# PX4FMUv2_4_5.net
KiCad netlist of a schematic drawn in EAGLE
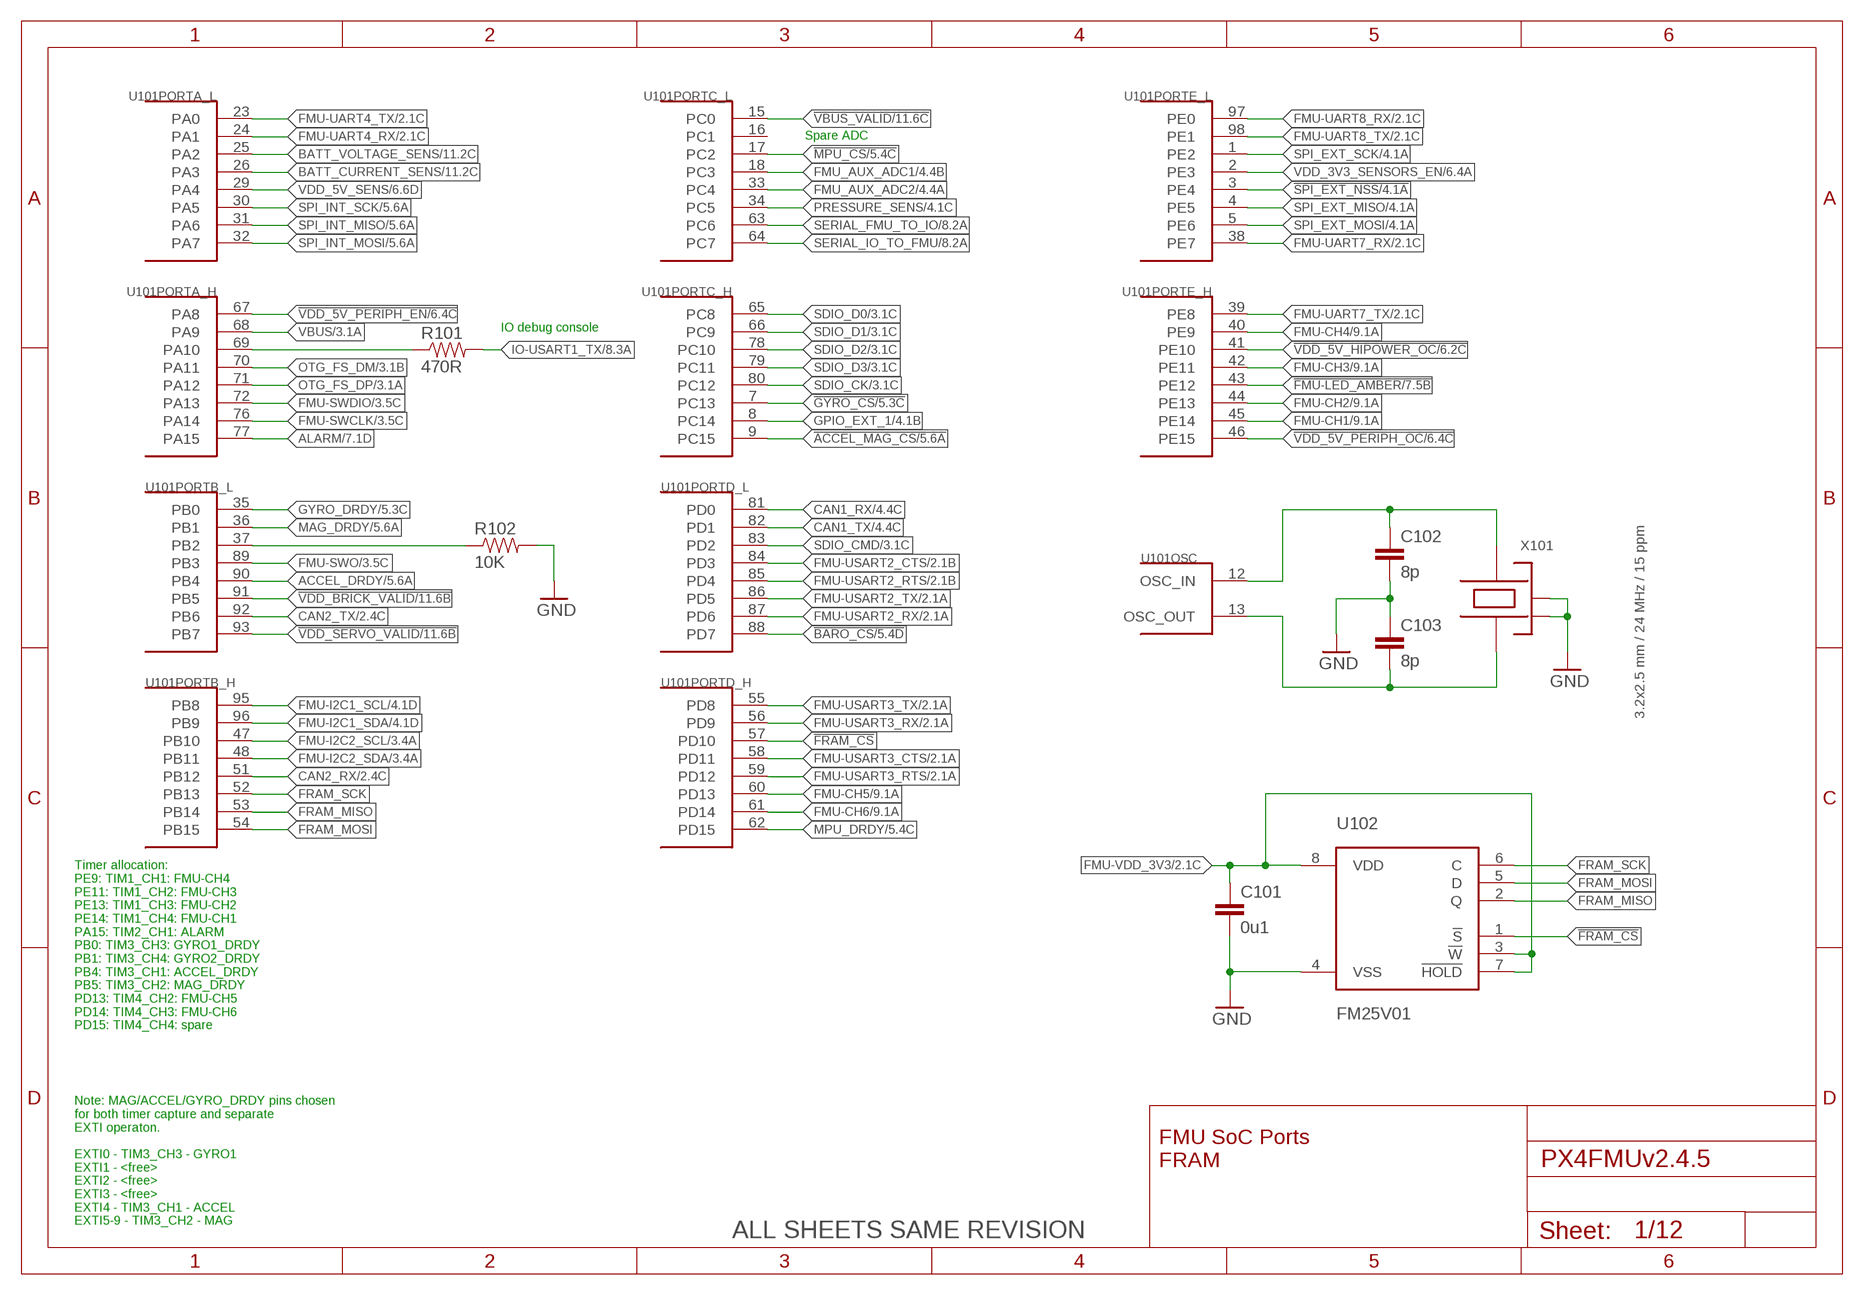
[diagram p0: schematic, sheet 1]
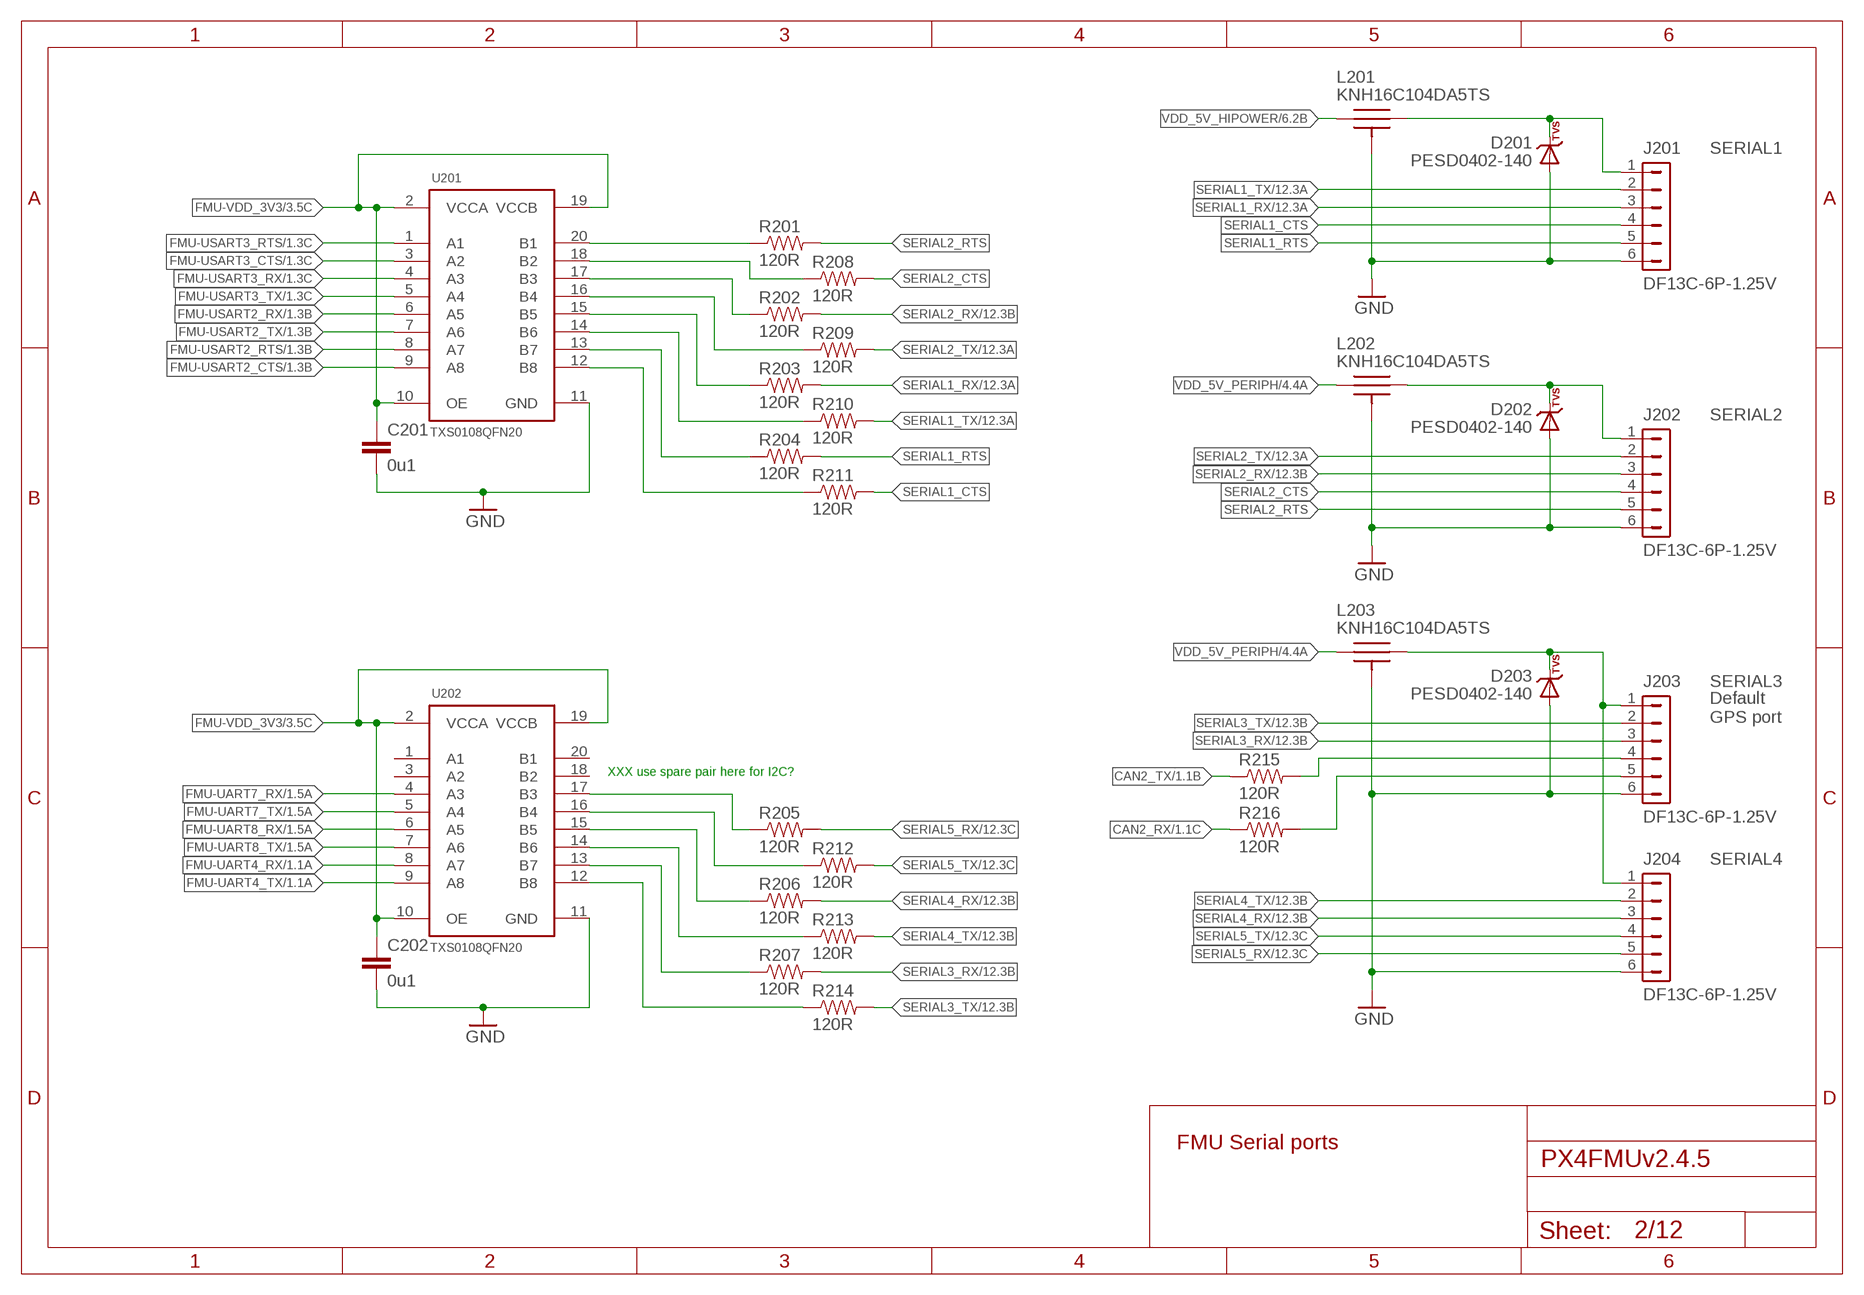
[diagram p1: schematic, sheet 2]
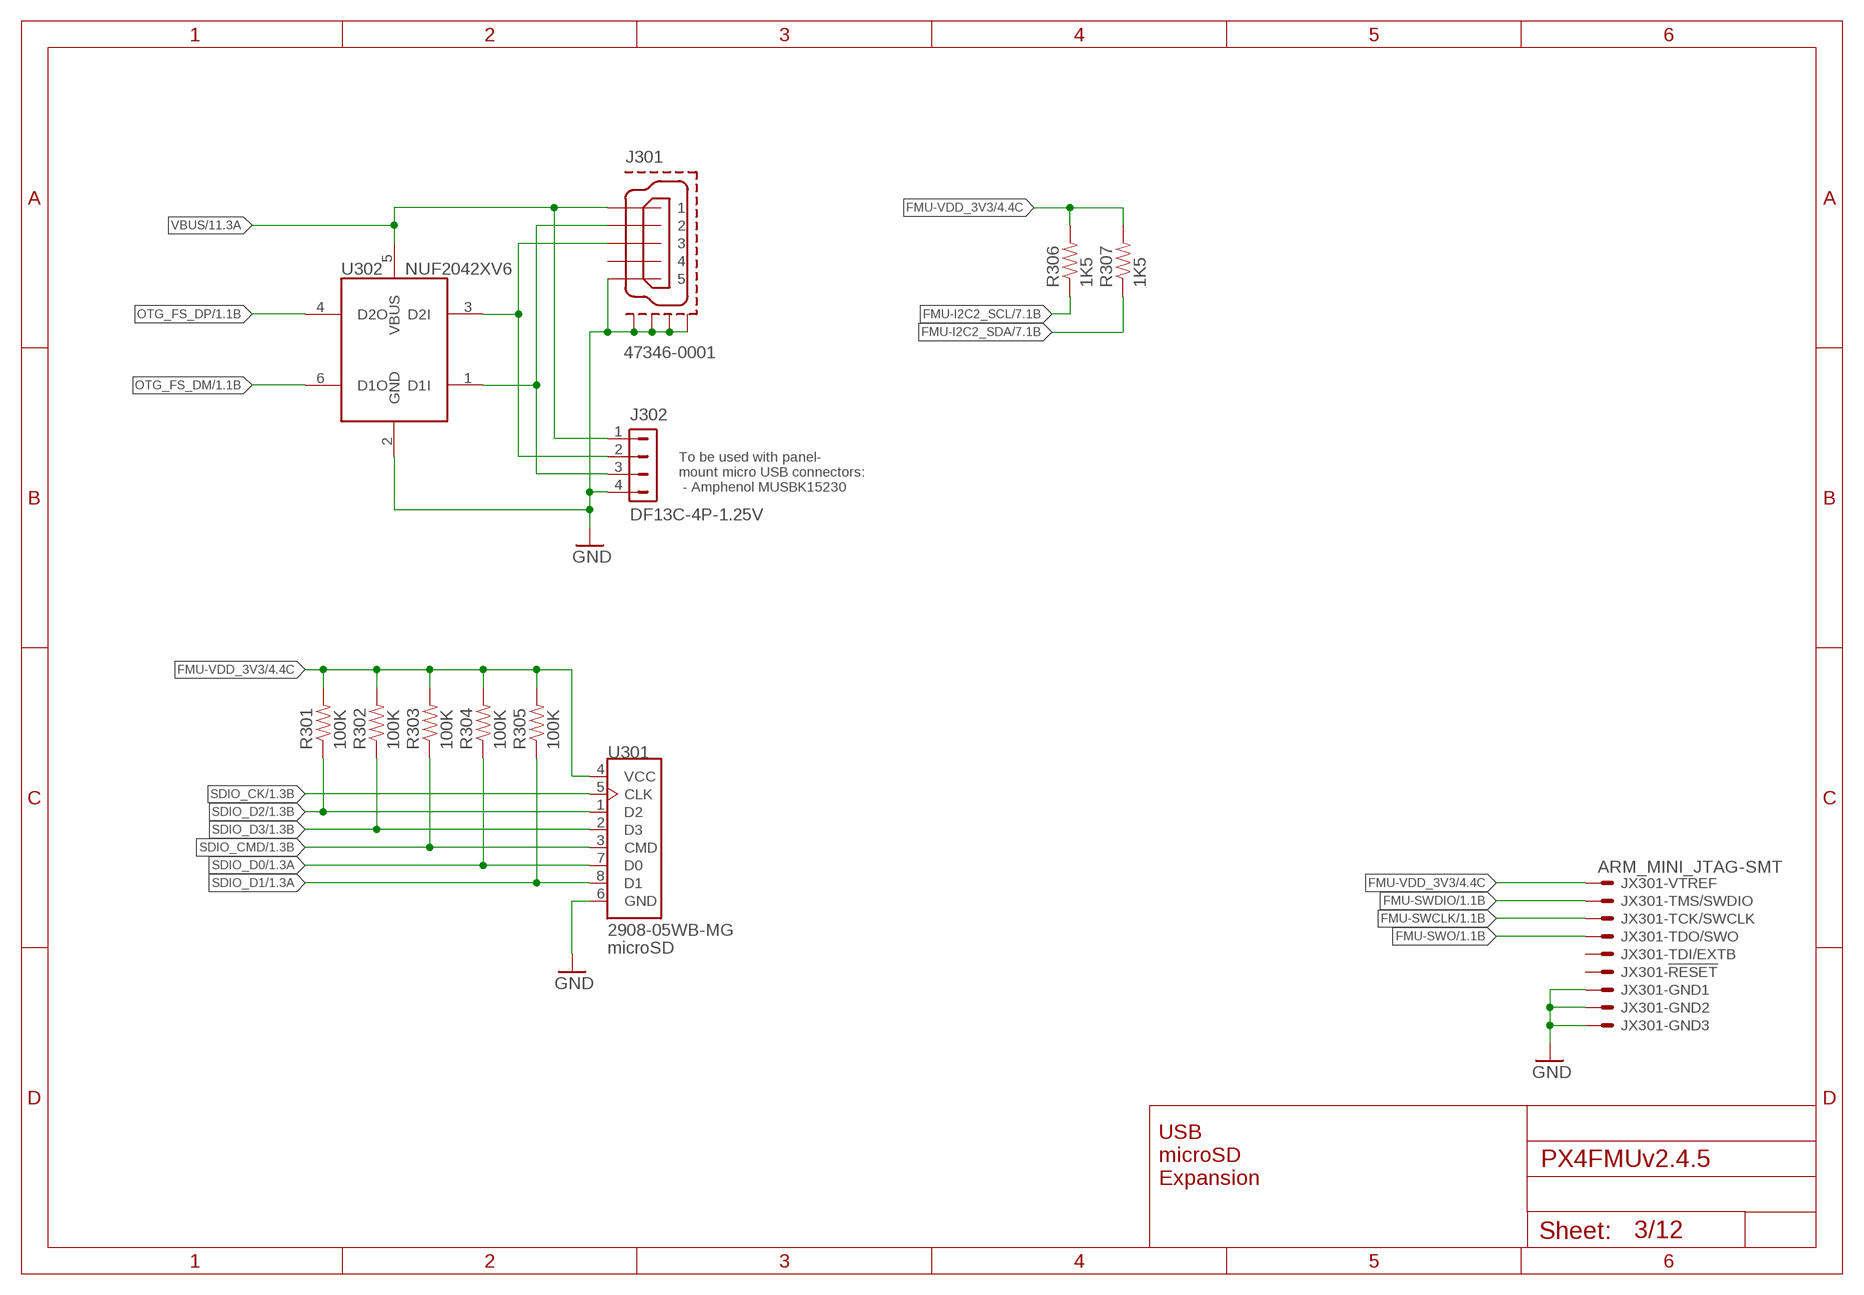
[diagram p2: schematic, sheet 3]
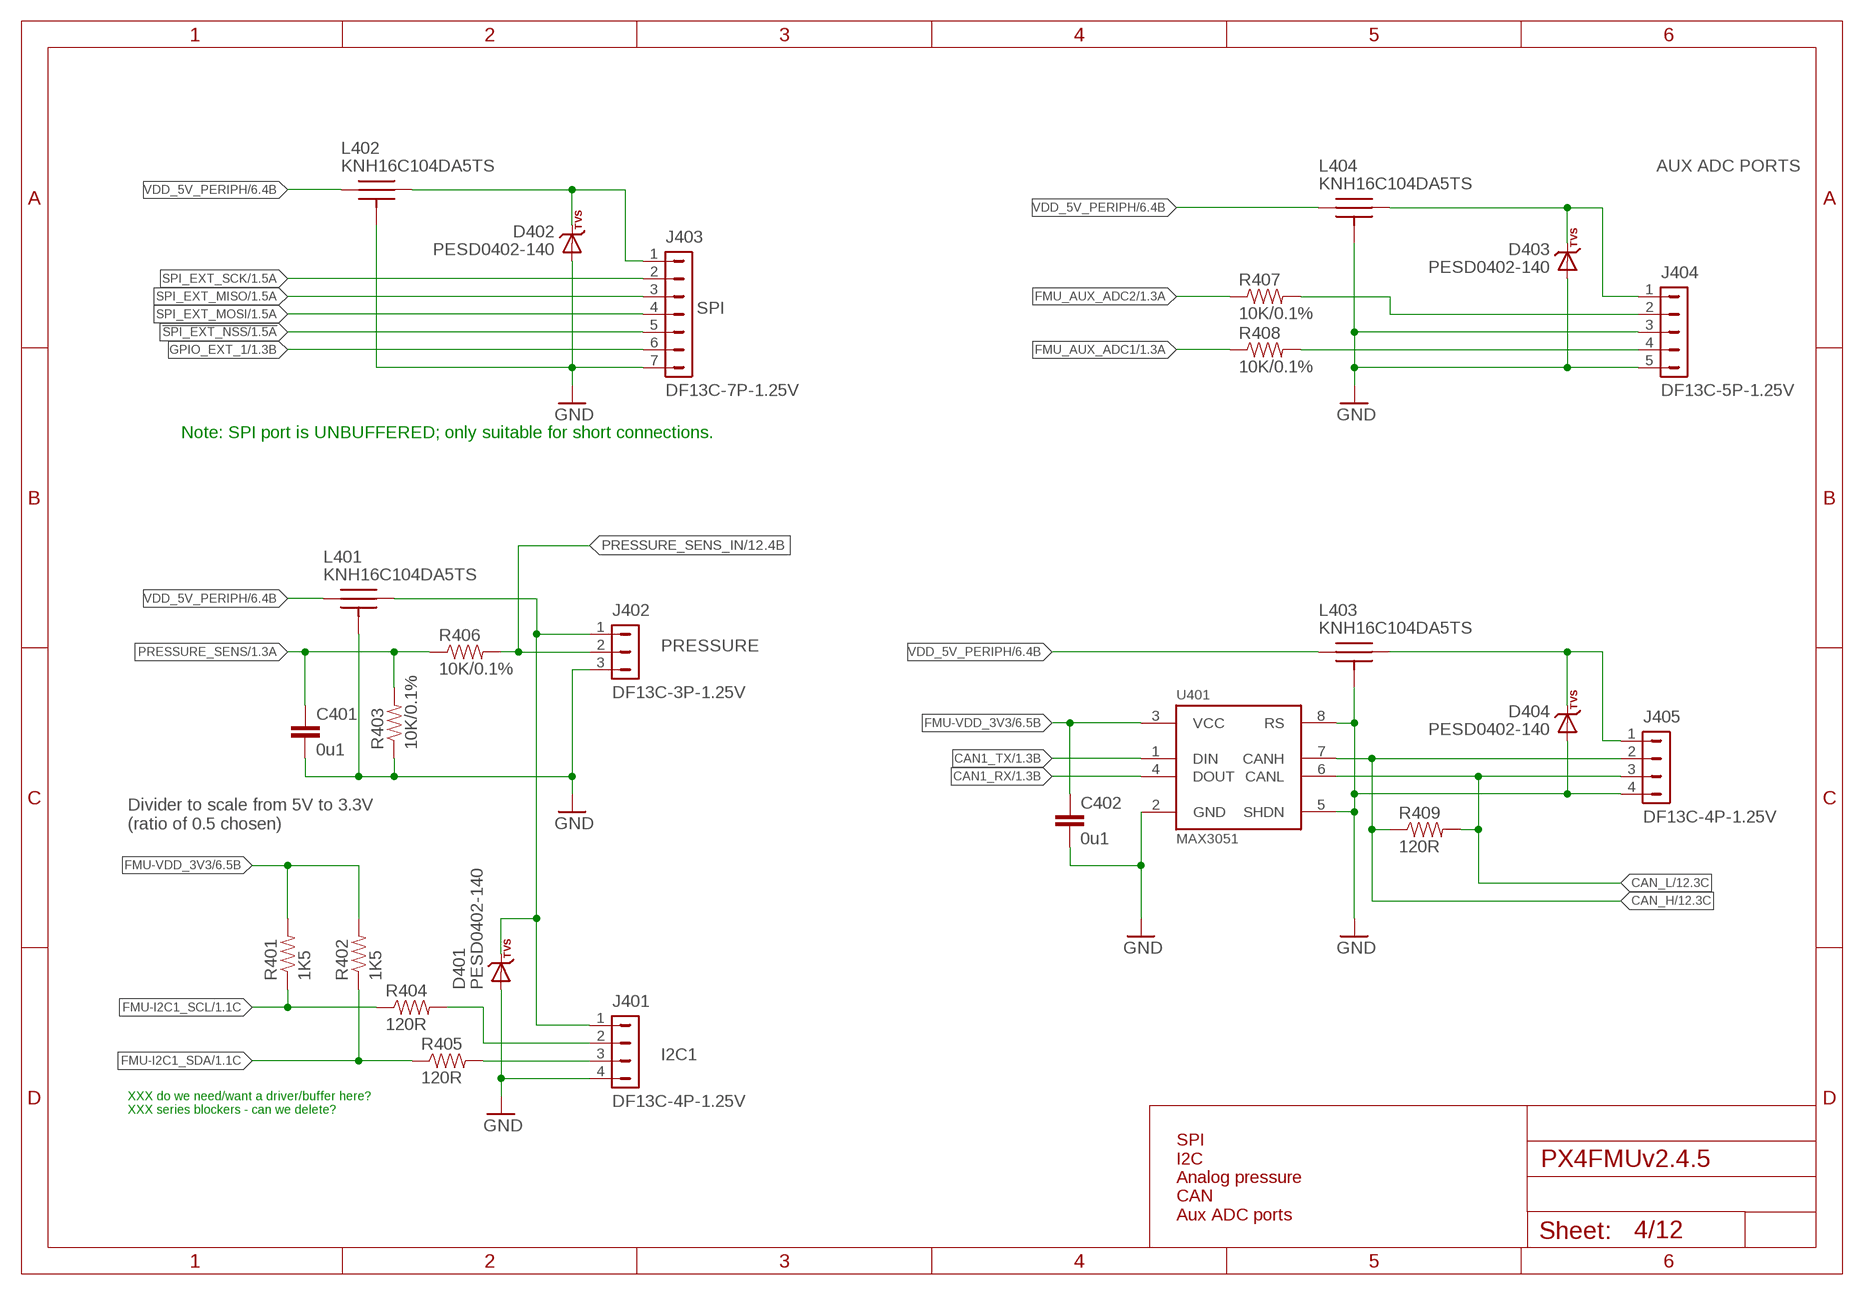
[diagram p3: schematic, sheet 4]
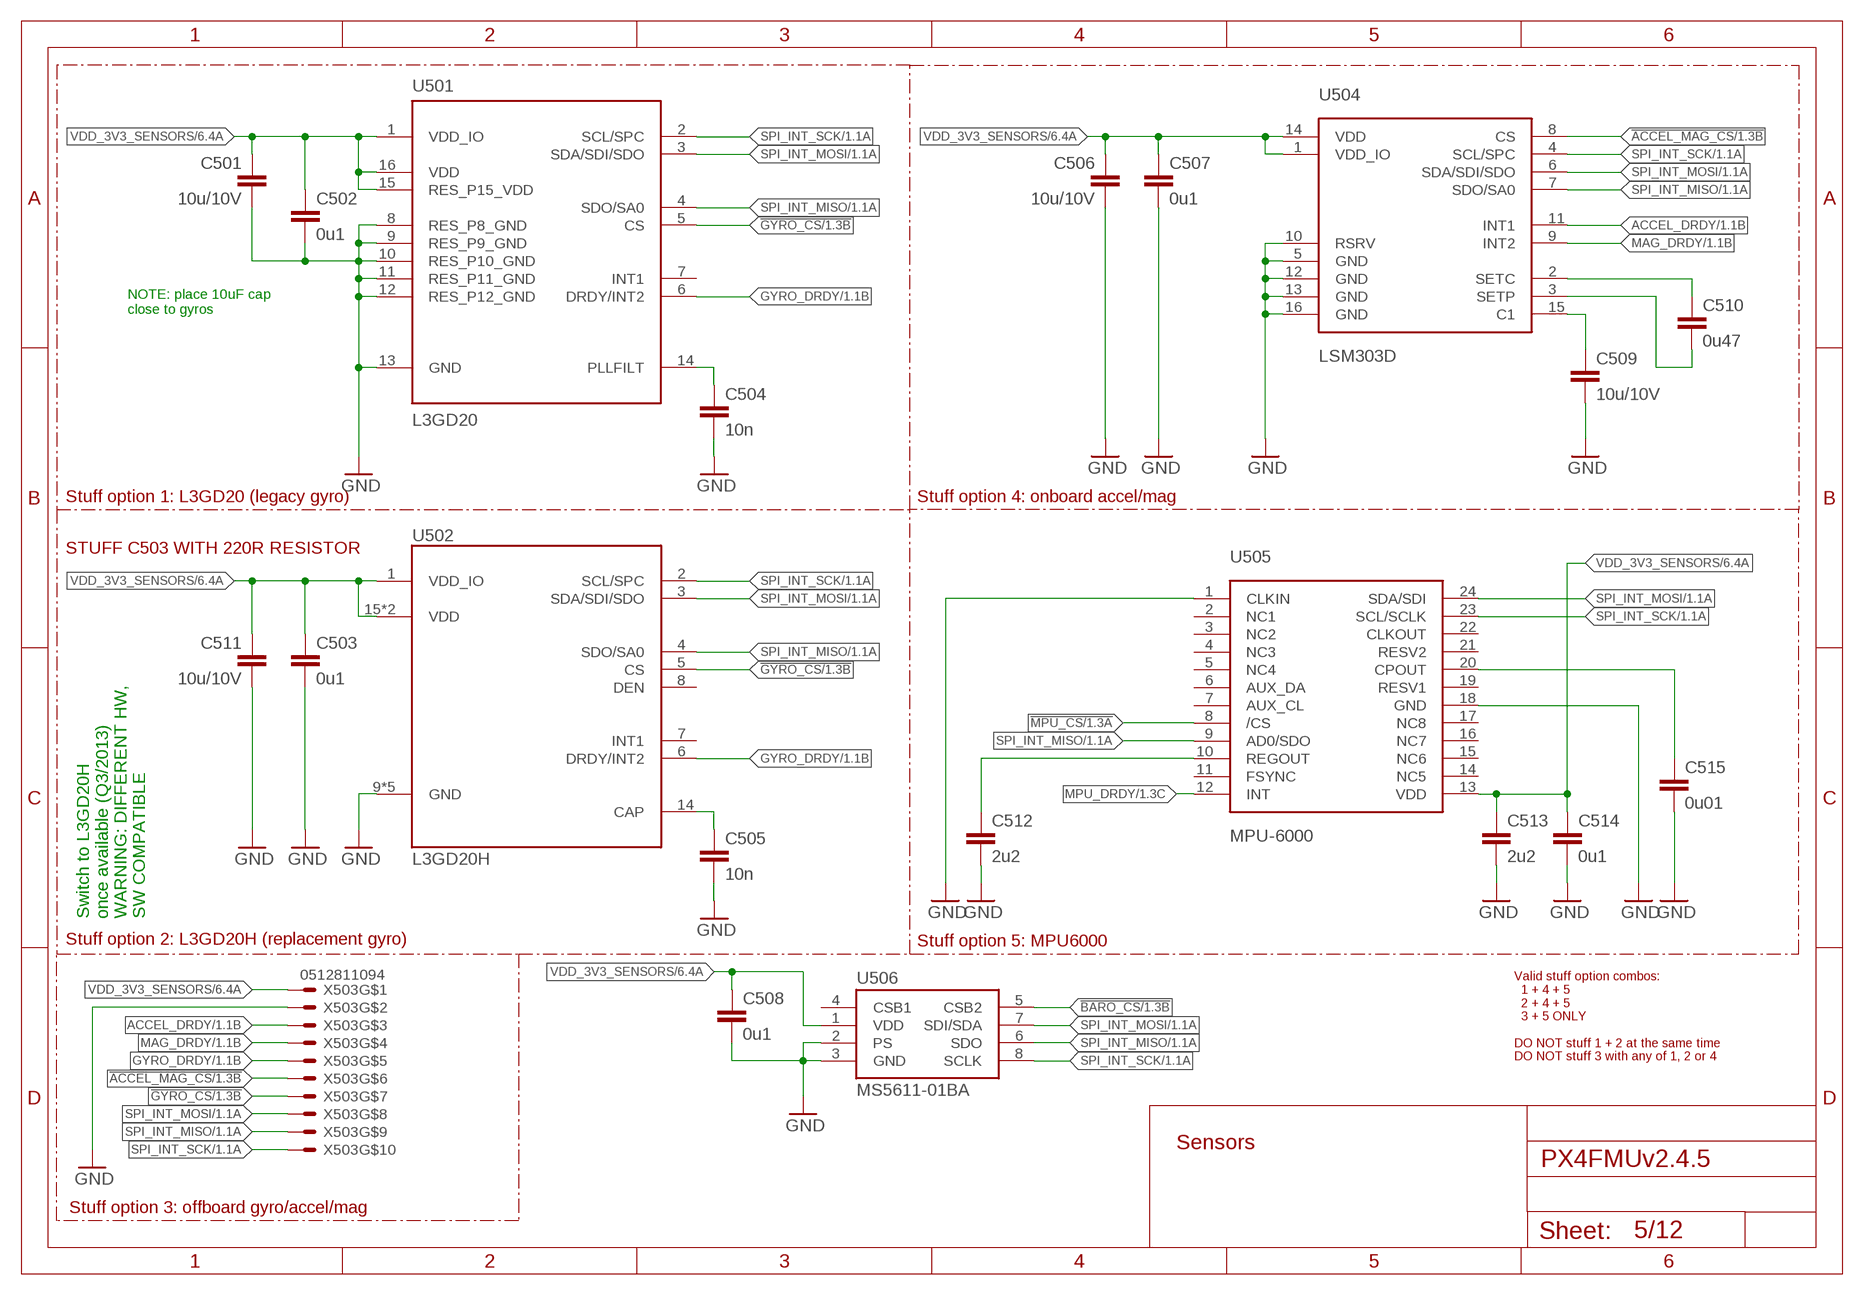
[diagram p4: schematic, sheet 5]
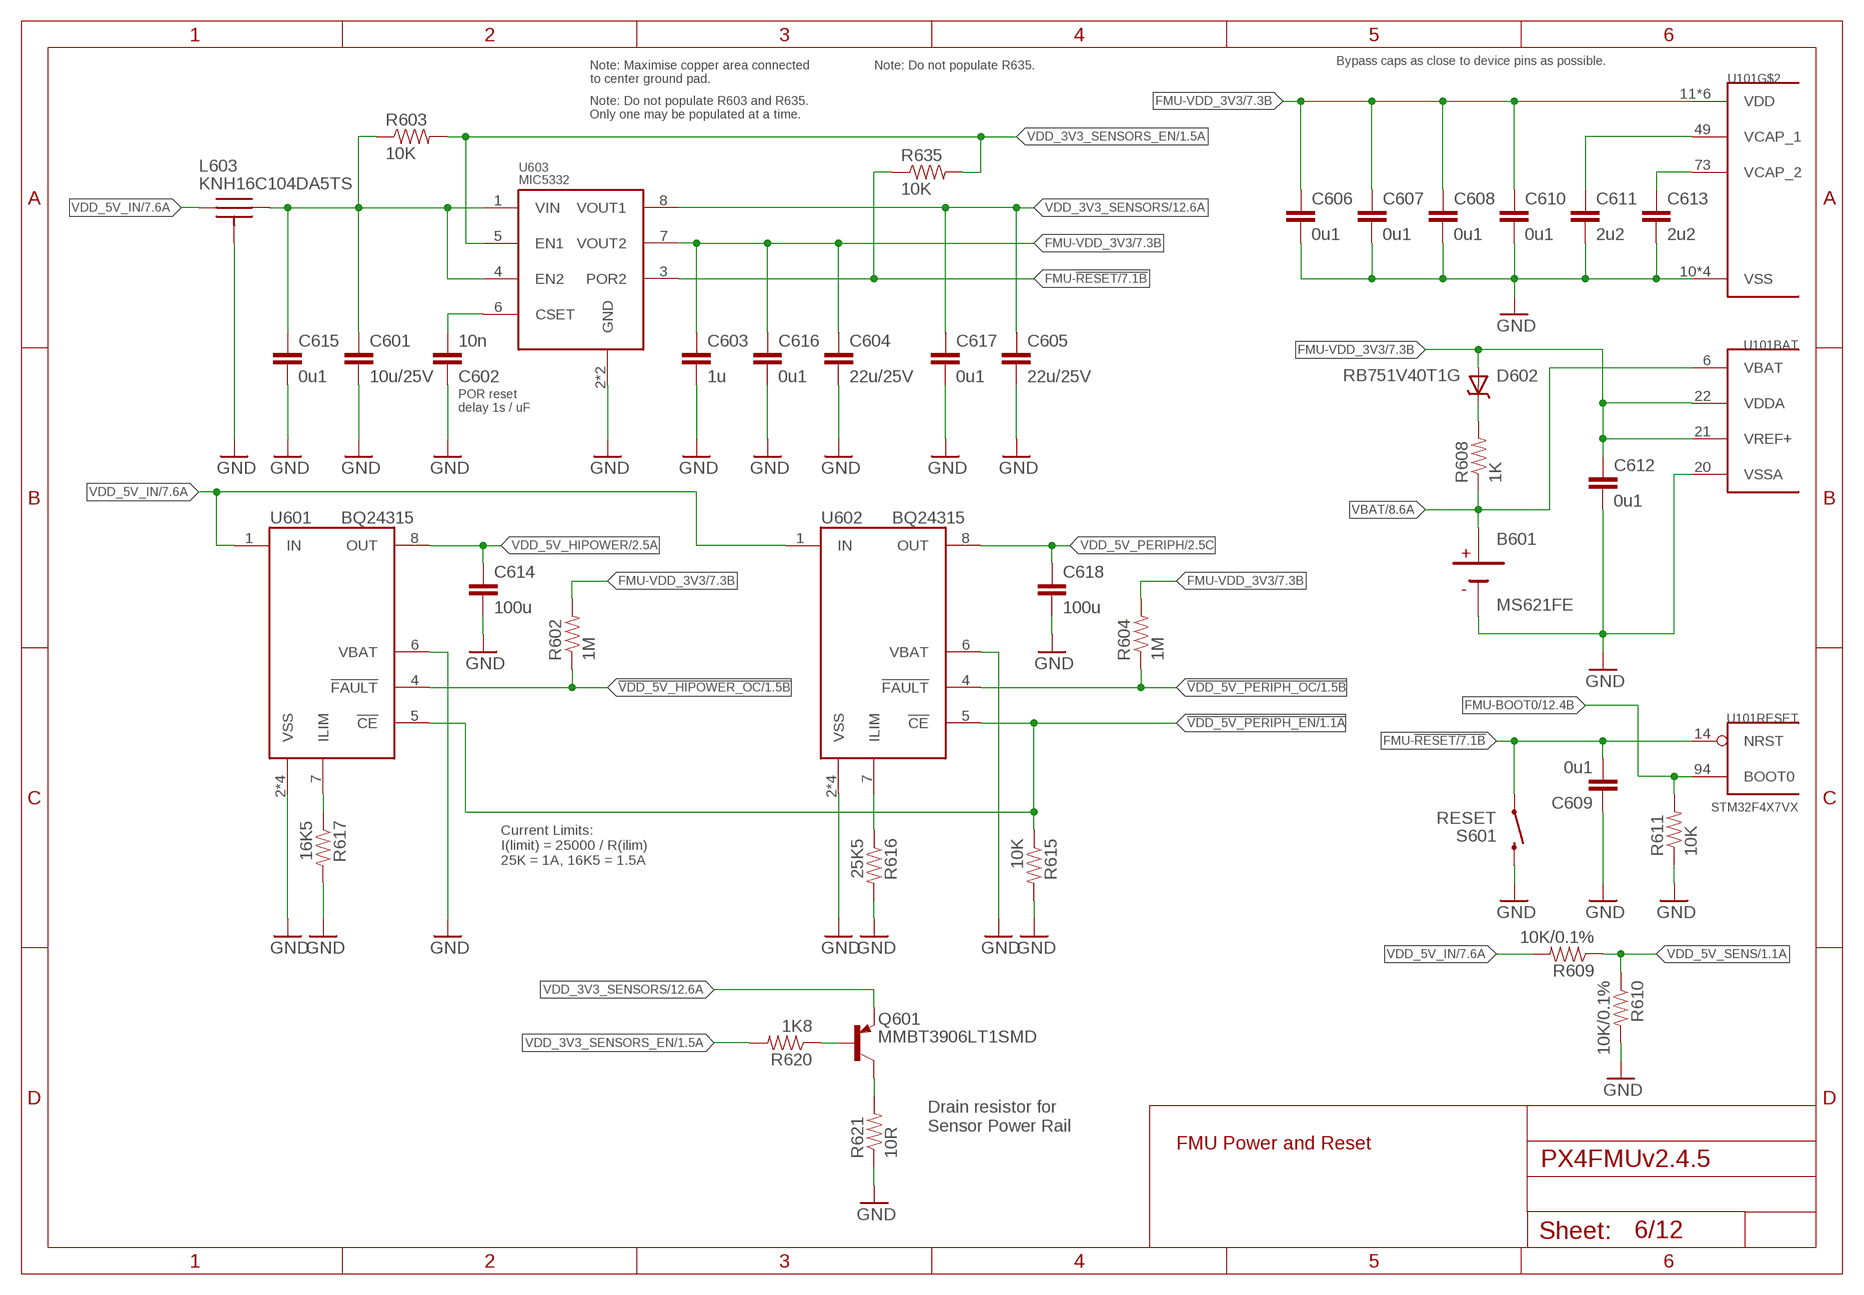
[diagram p5: schematic, sheet 6]
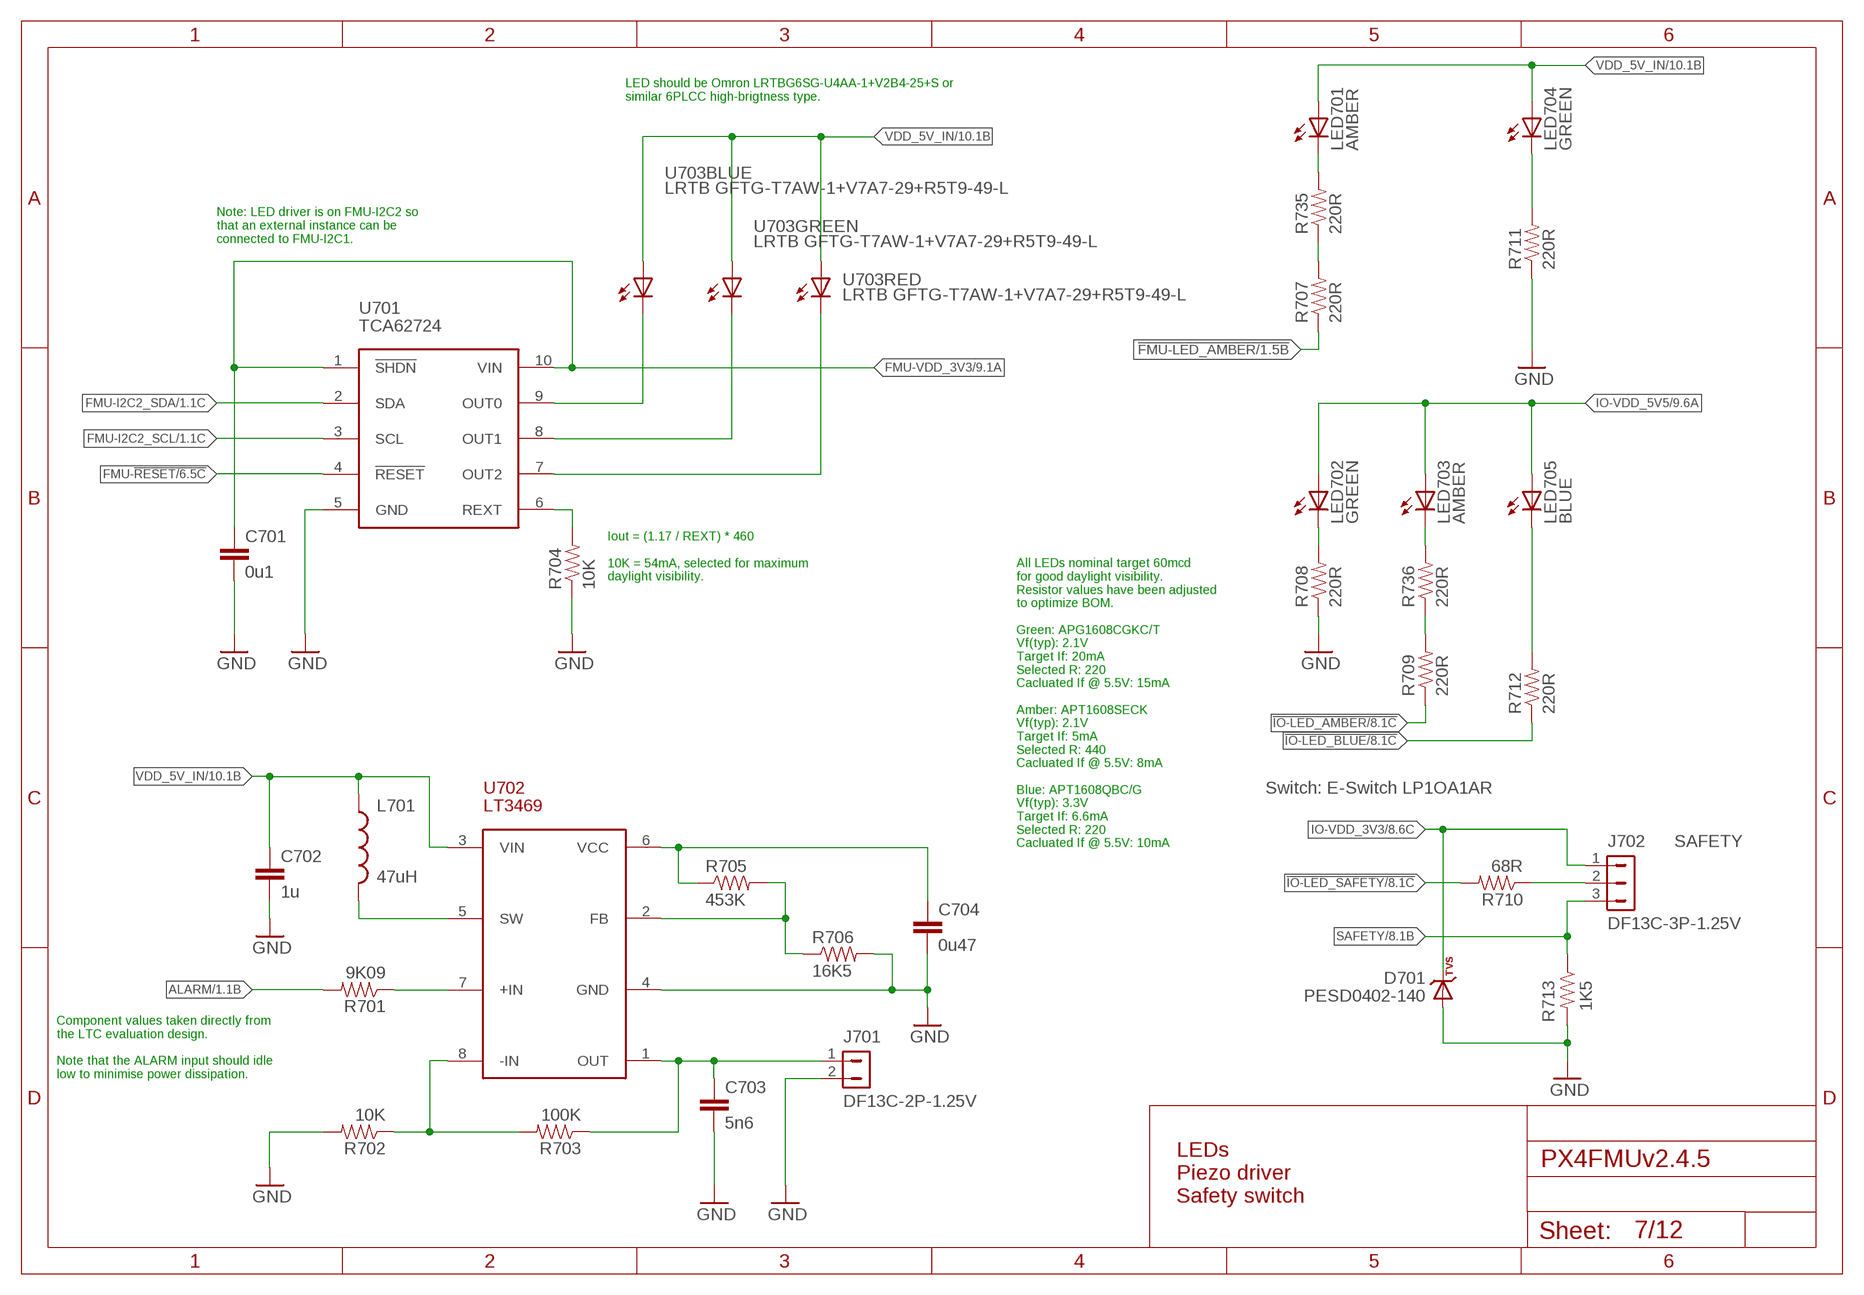
[diagram p6: schematic, sheet 7]
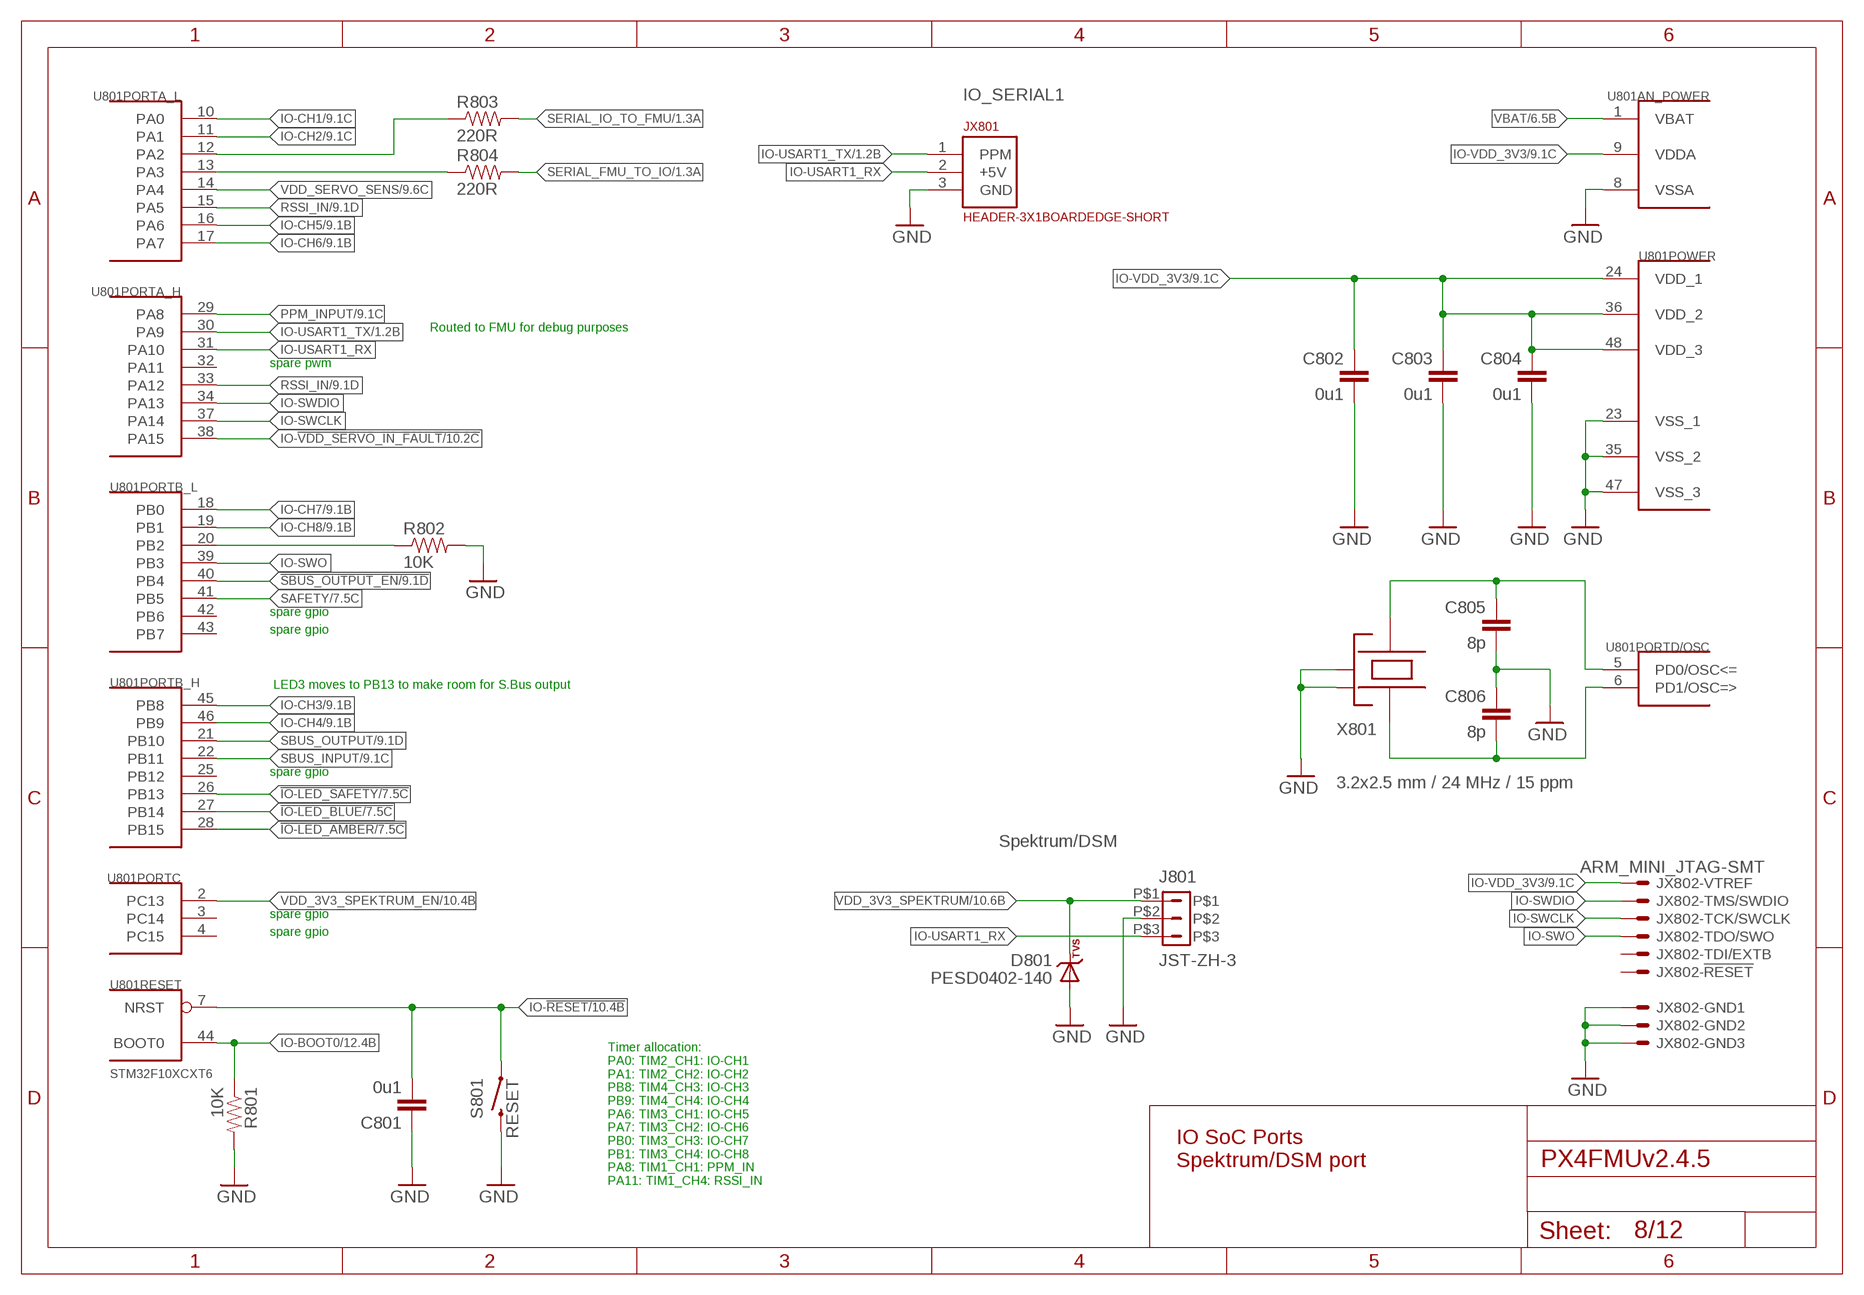
[diagram p7: schematic, sheet 8]
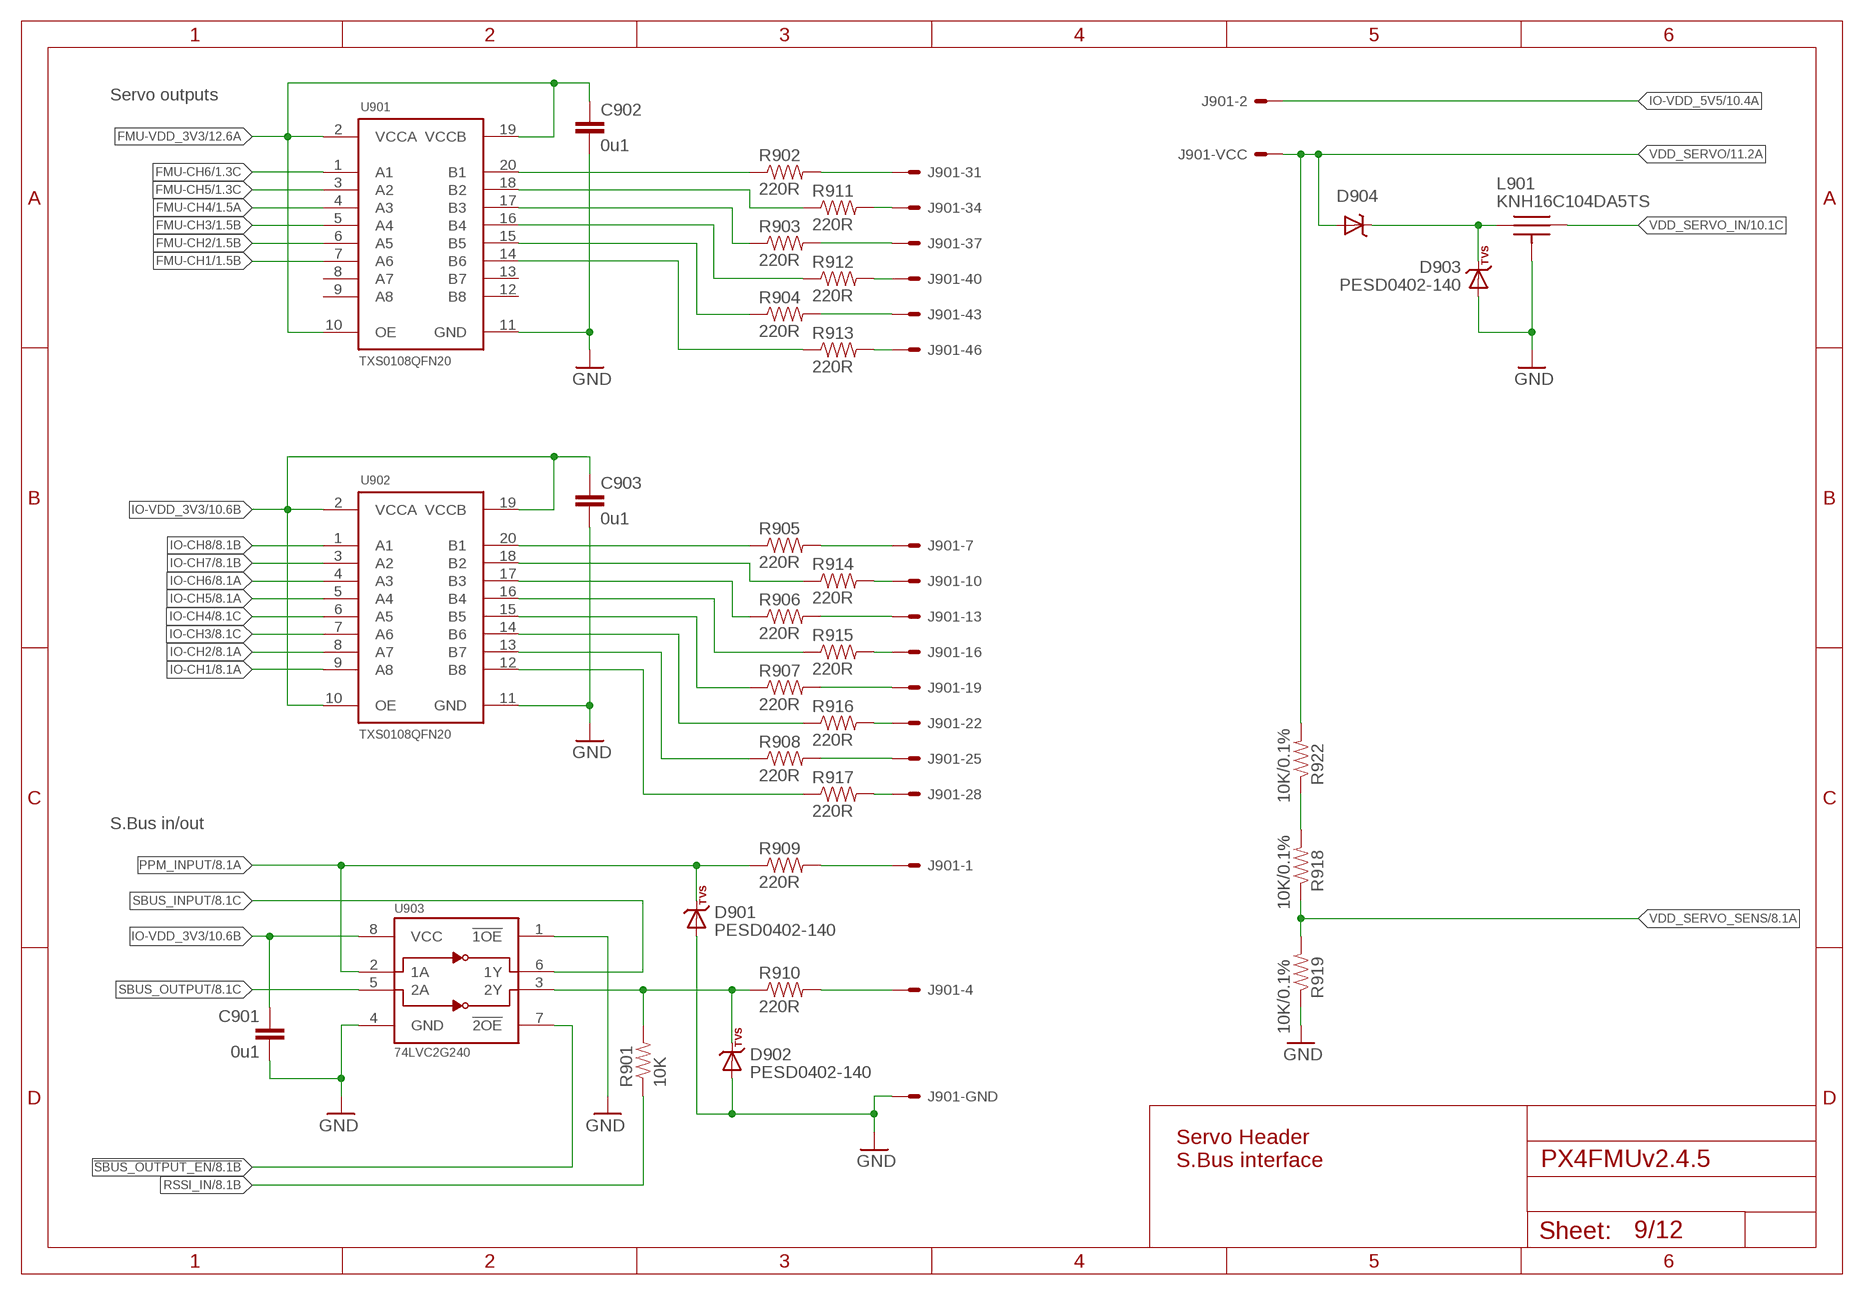
[diagram p8: schematic, sheet 9]
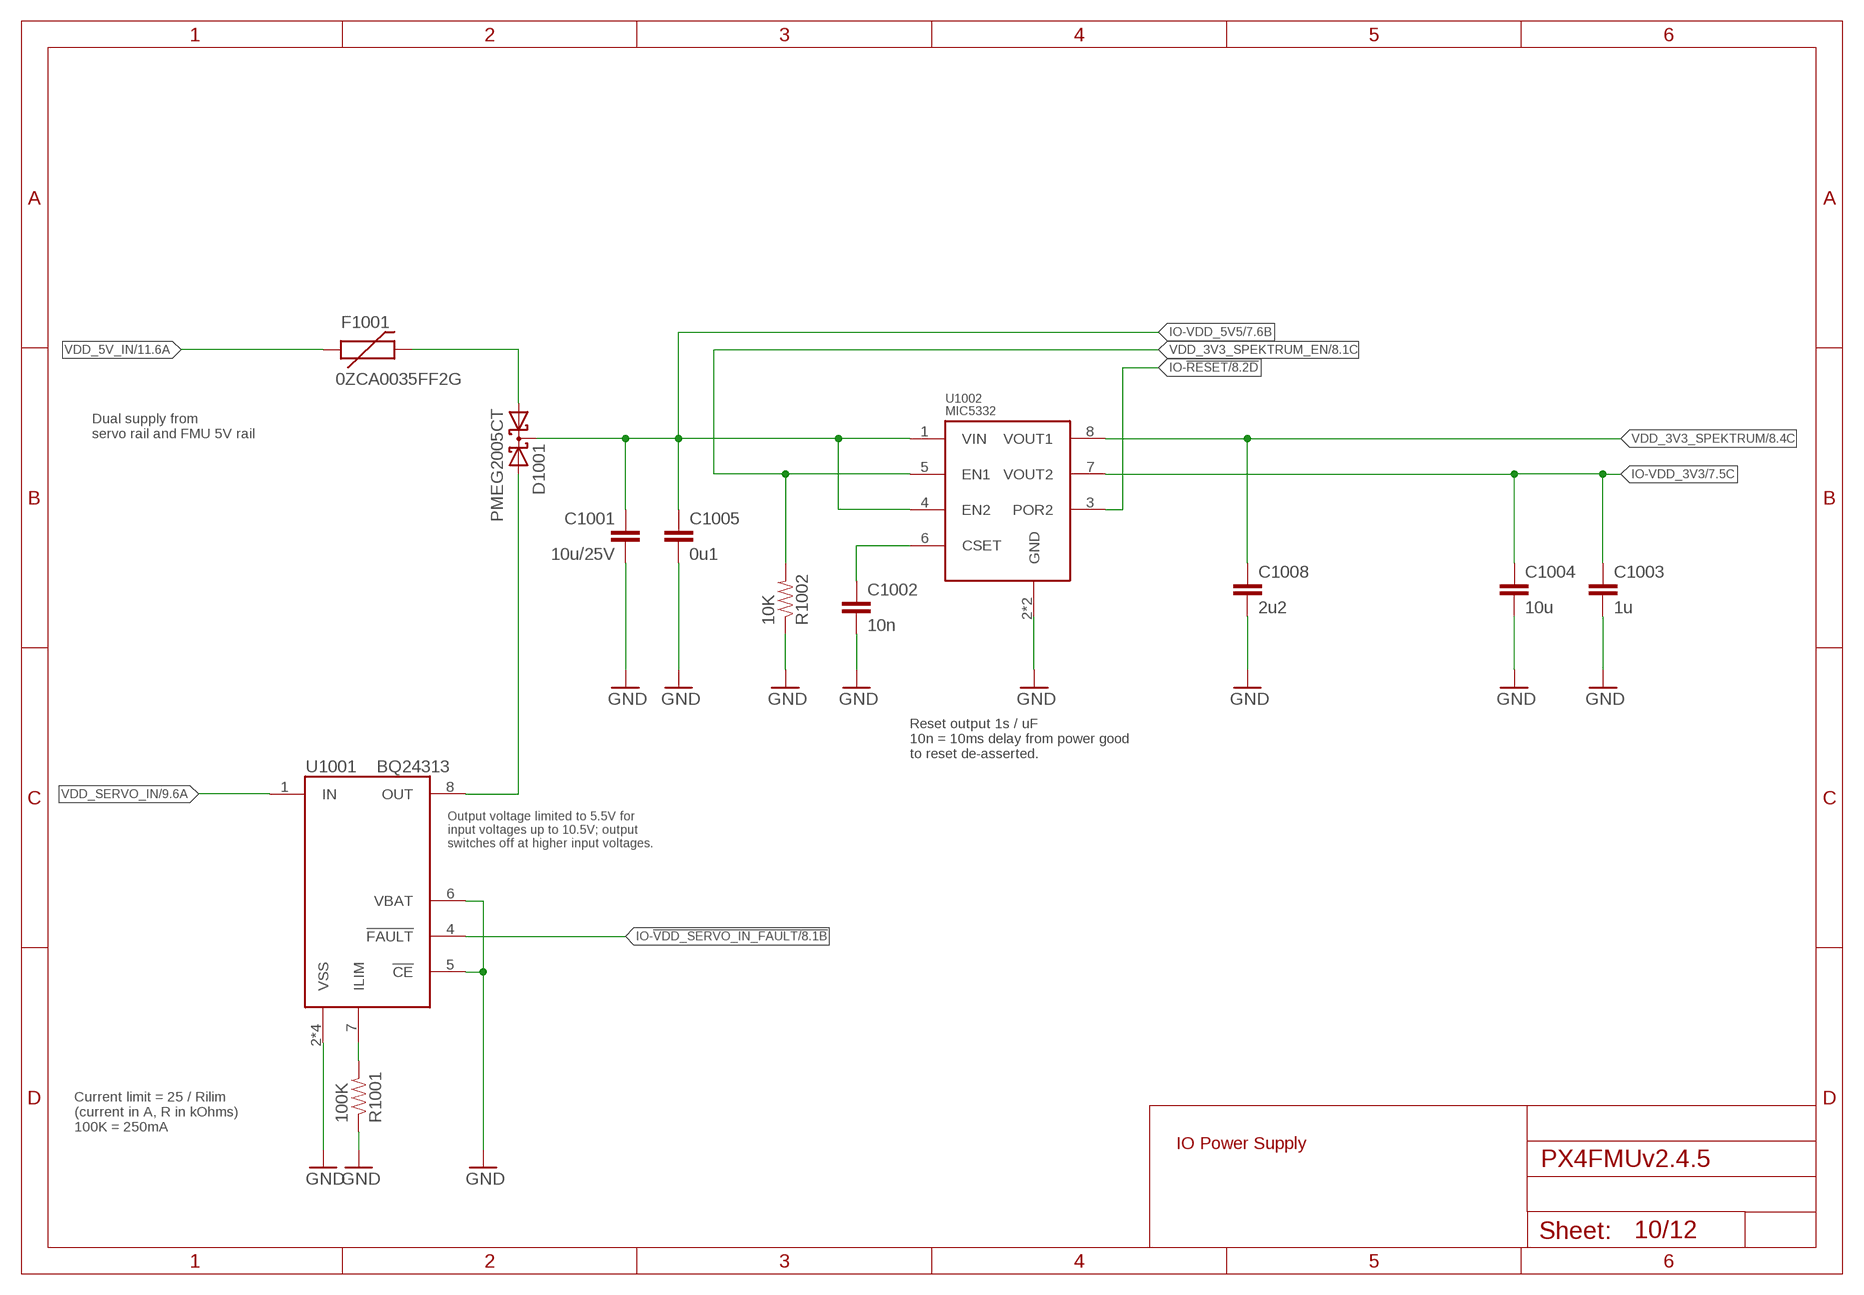
[diagram p9: schematic, sheet 10]
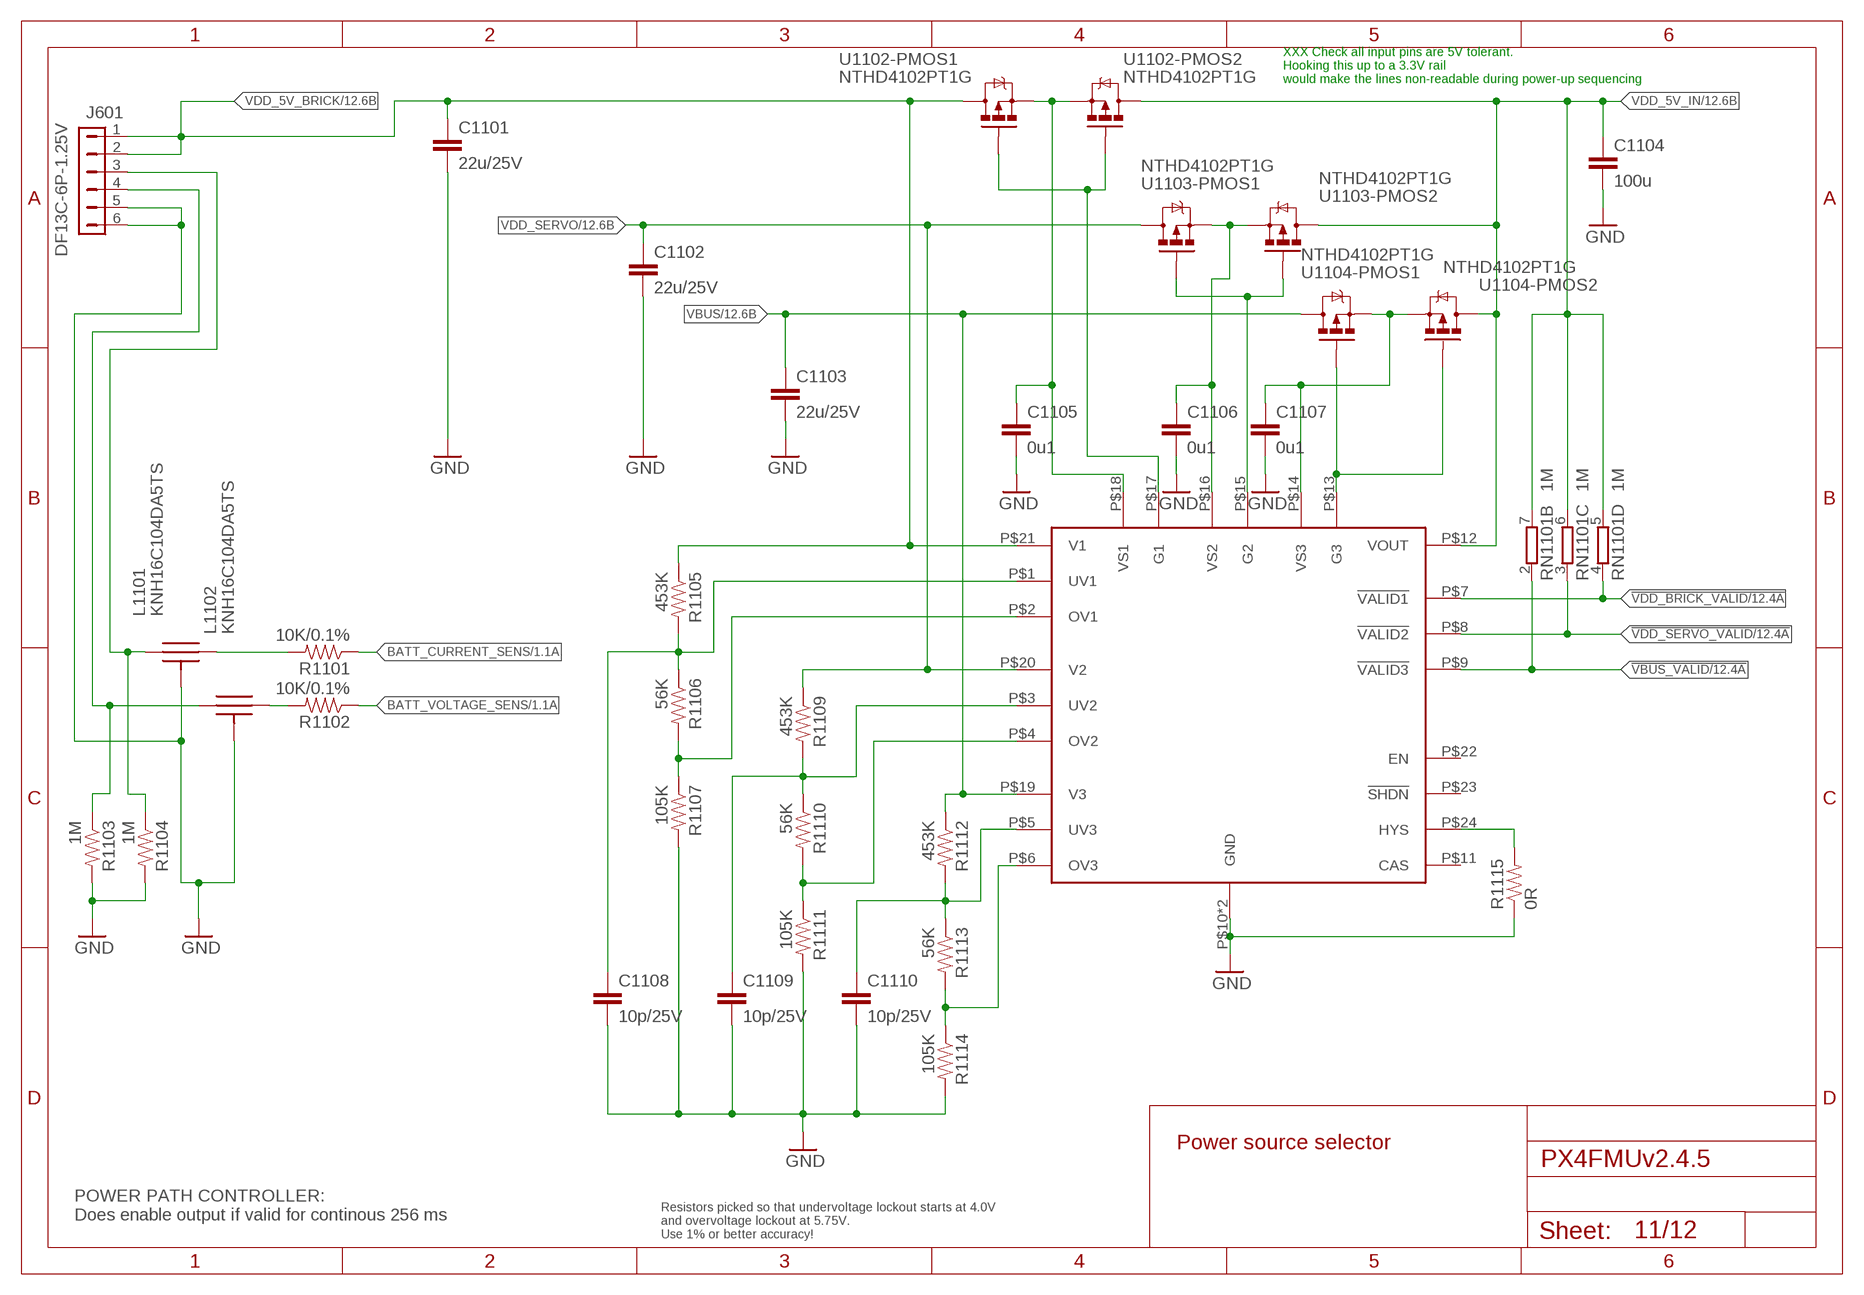
[diagram p10: schematic, sheet 11]
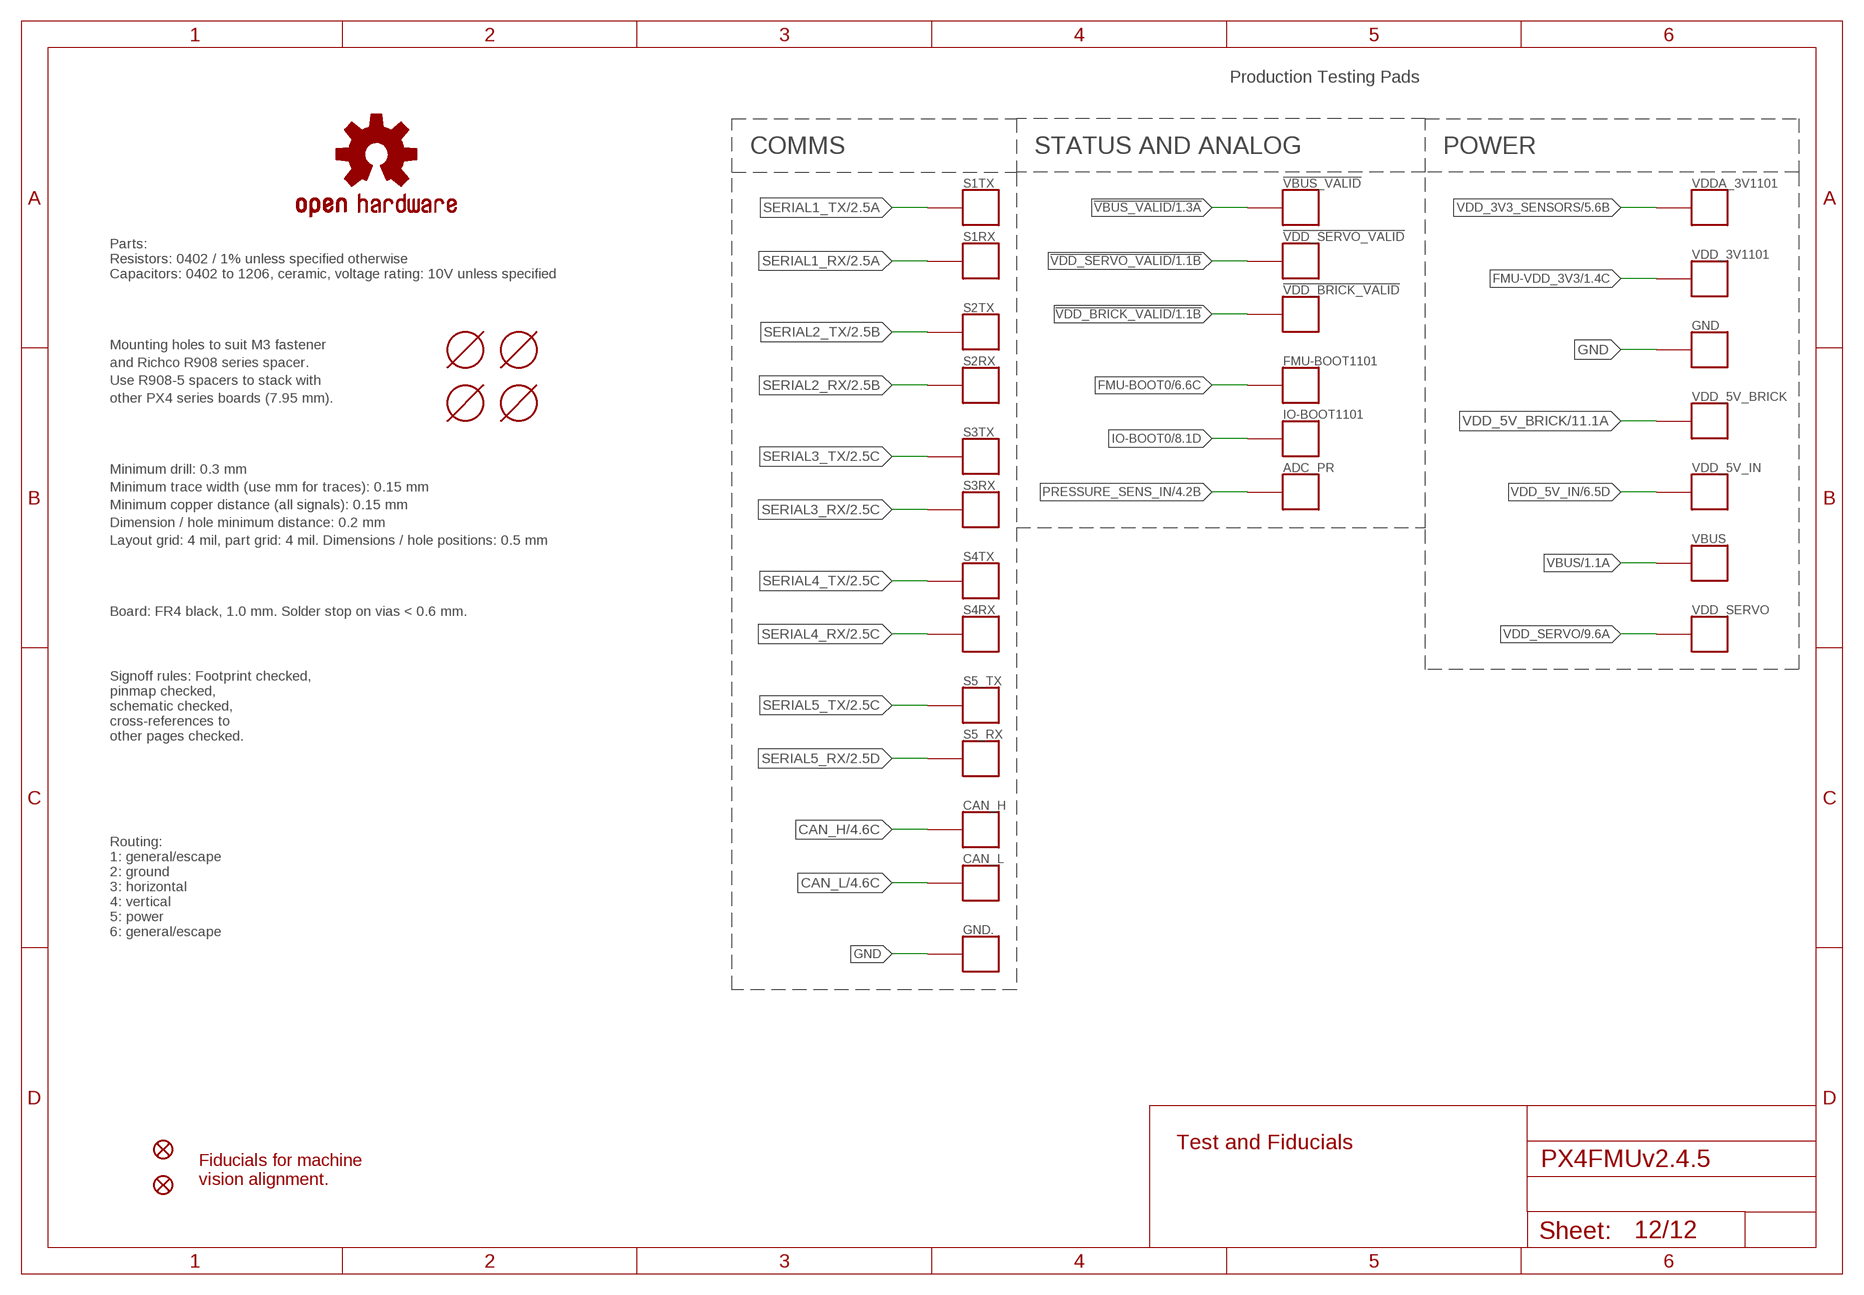
[diagram p11: schematic, sheet 12]

(export (version "E")
  (design (tool "Eeschema 10.0.6"))
  (components
    (comp (ref "C801")
      (value "0u1")
      (footprint "eagle-import:0402-CAP")
      (fields (field (name "PARTNO") "CC0402ZRY5V7BB104"))
      (libsource (lib "eagle-import") (part "CAP0402"))
    )
    (comp (ref "C802")
      (value "0u1")
      (footprint "eagle-import:0402-CAP")
      (fields (field (name "PARTNO") "CC0402ZRY5V7BB104"))
      (libsource (lib "eagle-import") (part "CAP0402"))
    )
    (comp (ref "C803")
      (value "0u1")
      (footprint "eagle-import:0402-CAP")
      (fields (field (name "PARTNO") "CC0402ZRY5V7BB104"))
      (libsource (lib "eagle-import") (part "CAP0402"))
    )
    (comp (ref "C804")
      (value "0u1")
      (footprint "eagle-import:0402-CAP")
      (fields (field (name "PARTNO") "CC0402ZRY5V7BB104"))
      (libsource (lib "eagle-import") (part "CAP0402"))
    )
    (comp (ref "C805")
      (value "8p")
      (footprint "eagle-import:0402-CAP")
      (fields (field (name "PARTNO") "C1005C0G1H080C"))
      (libsource (lib "eagle-import") (part "CAP0402"))
    )
    (comp (ref "C806")
      (value "8p")
      (footprint "eagle-import:0402-CAP")
      (fields (field (name "PARTNO") "C1005C0G1H080C"))
      (libsource (lib "eagle-import") (part "CAP0402"))
    )
    (comp (ref "D801")
      (value "PESD0402-140")
      (footprint "eagle-import:0402-TVS")
      (libsource (lib "eagle-import") (part "DIODE-TVS"))
    )
    (comp (ref "J801")
      (value "JST-ZH-3")
      (footprint "eagle-import:JST-ZH-SMT-VERTICAL")
      (fields (field (name "PARTNO") "B3B-ZR-SM4-TF (LF)(SN)(P)"))
      (libsource (lib "eagle-import") (part "JST-ZH-3"))
    )
    (comp (ref "JX801")
      (value "HEADER-3X1BOARDEDGE-SHORT")
      (footprint "eagle-import:HEADER_3X01_SMD_H_BOARD_EDGE_SHORT")
      (libsource (lib "eagle-import") (part "HEADER-3X1BOARDEDGE-SHORT"))
    )
    (comp (ref "JX802")
      (value "ARM_MINI_JTAG-SMT")
      (footprint "eagle-import:FTSH-105-01-XXX-DV-K")
      (fields (field (name "BOM") "EXCLUDE") (field (name "PARTNO") "M50-3900542"))
      (libsource (lib "eagle-import") (part "ARM_MINI_JTAG-SMT"))
    )
    (comp (ref "R801")
      (value "10K")
      (footprint "eagle-import:0402-RES")
      (fields (field (name "PARTNO") "RC0402FR-0710KL"))
      (libsource (lib "eagle-import") (part "RESISTOR0402-RES"))
    )
    (comp (ref "R802")
      (value "10K")
      (footprint "eagle-import:0402-RES")
      (fields (field (name "PARTNO") "RC0402FR-0710KL"))
      (libsource (lib "eagle-import") (part "RESISTOR0402-RES"))
    )
    (comp (ref "R803")
      (value "220R")
      (footprint "eagle-import:0402-RES")
      (fields (field (name "PARTNO") "RC0402FR-07220RL"))
      (libsource (lib "eagle-import") (part "RESISTOR0402-RES"))
    )
    (comp (ref "R804")
      (value "220R")
      (footprint "eagle-import:0402-RES")
      (fields (field (name "PARTNO") "RC0402FR-07220RL"))
      (libsource (lib "eagle-import") (part "RESISTOR0402-RES"))
    )
    (comp (ref "S801")
      (value "RESET")
      (footprint "eagle-import:EVQP7J01K")
      (fields (field (name "PARTNO") "EVQ-P7J01P"))
      (libsource (lib "eagle-import") (part "SWITCH-MOMENTARY-2"))
    )
    (comp (ref "U801")
      (value "STM32F10XCXT6")
      (footprint "eagle-import:TQFP48")
      (fields (field (name "PARTNO") "STM32F100C8T6B"))
      (libsource (lib "eagle-import") (part "STM32F10XCXT6"))
    )
    (comp (ref "X801")
      (value "3.2x2.5 mm / 24 MHz / 15 ppm")
      (footprint "eagle-import:OSCILLATOR-3.2X2.5")
      (fields (field (name "PARTNO") "NX3225SA-24.000000MHZ"))
      (libsource (lib "eagle-import") (part "OSCILLATOR-3.2X2.5"))
    )
    (comp (ref "C101")
      (value "0u1")
      (footprint "eagle-import:0402-CAP")
      (fields (field (name "PARTNO") "CC0402ZRY5V7BB104"))
      (libsource (lib "eagle-import") (part "CAP0402"))
    )
    (comp (ref "C102")
      (value "8p")
      (footprint "eagle-import:0402-CAP")
      (fields (field (name "PARTNO") "C1005C0G1H080C"))
      (libsource (lib "eagle-import") (part "CAP0402"))
    )
    (comp (ref "C103")
      (value "8p")
      (footprint "eagle-import:0402-CAP")
      (fields (field (name "PARTNO") "C1005C0G1H080C"))
      (libsource (lib "eagle-import") (part "CAP0402"))
    )
    (comp (ref "R101")
      (value "470R")
      (footprint "eagle-import:0402-RES")
      (fields (field (name "PARTNO") "RC0402FR-07470RL"))
      (libsource (lib "eagle-import") (part "RESISTOR0402-RES"))
    )
    (comp (ref "R102")
      (value "10K")
      (footprint "eagle-import:0402-RES")
      (fields (field (name "PARTNO") "RC0402FR-0710KL"))
      (libsource (lib "eagle-import") (part "RESISTOR0402-RES"))
    )
    (comp (ref "U101")
      (value "STM32F4X7VX")
      (footprint "eagle-import:TQFP100")
      (fields (field (name "PARTNO") "STM32F427VI"))
      (libsource (lib "eagle-import") (part "STM32F4X7VX"))
    )
    (comp (ref "U102")
      (value "FM25V01")
      (footprint "eagle-import:SO08")
      (fields (field (name "PARTNO") "FM25V01-G"))
      (libsource (lib "eagle-import") (part "FM25V01"))
    )
    (comp (ref "X101")
      (value "3.2x2.5 mm / 24 MHz / 15 ppm")
      (footprint "eagle-import:OSCILLATOR-3.2X2.5")
      (fields (field (name "PARTNO") "NX3225SA-24.000000MHZ"))
      (libsource (lib "eagle-import") (part "OSCILLATOR-3.2X2.5"))
    )
    (comp (ref "C1001")
      (value "10u/25V")
      (footprint "eagle-import:0805-CAP")
      (fields (field (name "PARTNO") "CL21A106KAYNNNE"))
      (libsource (lib "eagle-import") (part "CAP0805"))
    )
    (comp (ref "C1002")
      (value "10n")
      (footprint "eagle-import:0402-CAP")
      (fields (field (name "PARTNO") "CC0402KRX7R7BB103"))
      (libsource (lib "eagle-import") (part "CAP0402"))
    )
    (comp (ref "C1003")
      (value "1u")
      (footprint "eagle-import:0603-CAP")
      (fields (field (name "PARTNO") "CC0603ZRY5V7BB105"))
      (libsource (lib "eagle-import") (part "CAP0603"))
    )
    (comp (ref "C1004")
      (value "10u")
      (footprint "eagle-import:0603-CAP")
      (fields (field (name "PARTNO") "C1608X5R1A106K080AC"))
      (libsource (lib "eagle-import") (part "CAP0603"))
    )
    (comp (ref "C1005")
      (value "0u1")
      (footprint "eagle-import:0402-CAP")
      (fields (field (name "PARTNO") "CC0402ZRY5V7BB104"))
      (libsource (lib "eagle-import") (part "CAP0402"))
    )
    (comp (ref "C1008")
      (value "2u2")
      (footprint "eagle-import:0402-CAP")
      (fields (field (name "PARTNO") "C1005X6S1C225K050BC"))
      (libsource (lib "eagle-import") (part "CAP0402"))
    )
    (comp (ref "D1001")
      (value "PMEG2005CT")
      (footprint "eagle-import:SOT23-3")
      (libsource (lib "eagle-import") (part "PMEG2005CT"))
    )
    (comp (ref "F1001")
      (value "0ZCA0035FF2G")
      (footprint "eagle-import:PTC-1206")
      (libsource (lib "eagle-import") (part "PTCSMD"))
    )
    (comp (ref "R1001")
      (value "100K")
      (footprint "eagle-import:0402-RES")
      (fields (field (name "PARTNO") "RC0402FR-07100KL"))
      (libsource (lib "eagle-import") (part "RESISTOR0402-RES"))
    )
    (comp (ref "R1002")
      (value "10K")
      (footprint "eagle-import:0402-RES")
      (fields (field (name "PARTNO") "RC0402FR-0710KL"))
      (libsource (lib "eagle-import") (part "RESISTOR0402-RES"))
    )
    (comp (ref "U1001")
      (value "BQ24313")
      (footprint "eagle-import:QFN8-DSG")
      (fields (field (name "PARTNO") "BQ24313DSGT"))
      (libsource (lib "eagle-import") (part "BQ24313"))
    )
    (comp (ref "U1002")
      (value "MIC5332")
      (footprint "eagle-import:MLF-8-EPAD")
      (fields (field (name "PARTNO") "MIC5332-SSYMT"))
      (libsource (lib "eagle-import") (part "MIC5332"))
    )
    (comp (ref "!VBUS_VALID")
      (value "PAD.04")
      (footprint "eagle-import:PAD.04X.04")
      (libsource (lib "eagle-import") (part "PAD.04"))
    )
    (comp (ref "!VDD_BRICK_VALID")
      (value "PAD.04")
      (footprint "eagle-import:PAD.04X.04")
      (libsource (lib "eagle-import") (part "PAD.04"))
    )
    (comp (ref "!VDD_SERVO_VALID")
      (value "PAD.04")
      (footprint "eagle-import:PAD.04X.04")
      (libsource (lib "eagle-import") (part "PAD.04"))
    )
    (comp (ref "ADC_PR")
      (value "PAD.04")
      (footprint "eagle-import:PAD.04X.04")
      (libsource (lib "eagle-import") (part "PAD.04"))
    )
    (comp (ref "CAN_H")
      (value "PAD.04")
      (footprint "eagle-import:PAD.04X.04")
      (libsource (lib "eagle-import") (part "PAD.04"))
    )
    (comp (ref "CAN_L")
      (value "PAD.04")
      (footprint "eagle-import:PAD.04X.04")
      (libsource (lib "eagle-import") (part "PAD.04"))
    )
    (comp (ref "FMU-BOOT1101")
      (value "PAD.04")
      (footprint "eagle-import:PAD.04X.04")
      (libsource (lib "eagle-import") (part "PAD.04"))
    )
    (comp (ref "GND")
      (value "PAD.04")
      (footprint "eagle-import:PAD.04X.04")
      (libsource (lib "eagle-import") (part "PAD.04"))
    )
    (comp (ref "GND.")
      (value "PAD.04")
      (footprint "eagle-import:PAD.04X.04")
      (libsource (lib "eagle-import") (part "PAD.04"))
    )
    (comp (ref "IO-BOOT1101")
      (value "PAD.04")
      (footprint "eagle-import:PAD.04X.04")
      (libsource (lib "eagle-import") (part "PAD.04"))
    )
    (comp (ref "JP1")
      (value "FIDUCIAL1.5X3")
      (footprint "eagle-import:FIDUCIAL-1.5X3")
      (libsource (lib "eagle-import") (part "FIDUCIAL1.5X3"))
    )
    (comp (ref "JP2")
      (value "FIDUCIAL1.5X3")
      (footprint "eagle-import:FIDUCIAL-1.5X3")
      (libsource (lib "eagle-import") (part "FIDUCIAL1.5X3"))
    )
    (comp (ref "M3_MOUNT1101")
      (value "MOUNT-HOLE3.1MM")
      (footprint "eagle-import:MOUNT-HOLE3.1")
      (libsource (lib "eagle-import") (part "MOUNT-HOLE3.1MM"))
    )
    (comp (ref "M3_MOUNT1102")
      (value "MOUNT-HOLE3.1MM")
      (footprint "eagle-import:MOUNT-HOLE3.1")
      (libsource (lib "eagle-import") (part "MOUNT-HOLE3.1MM"))
    )
    (comp (ref "M3_MOUNT1103")
      (value "MOUNT-HOLE3.1MM")
      (footprint "eagle-import:MOUNT-HOLE3.1")
      (libsource (lib "eagle-import") (part "MOUNT-HOLE3.1MM"))
    )
    (comp (ref "M3_MOUNT1104")
      (value "MOUNT-HOLE3.1MM")
      (footprint "eagle-import:MOUNT-HOLE3.1")
      (libsource (lib "eagle-import") (part "MOUNT-HOLE3.1MM"))
    )
    (comp (ref "OSHW_LOGO")
      (value "OSHW-LOGOS")
      (footprint "eagle-import:OSHW-LOGO-S")
      (libsource (lib "eagle-import") (part "OSHW-LOGOS"))
    )
    (comp (ref "S1RX")
      (value "PAD.04")
      (footprint "eagle-import:PAD.04X.04")
      (libsource (lib "eagle-import") (part "PAD.04"))
    )
    (comp (ref "S1TX")
      (value "PAD.04")
      (footprint "eagle-import:PAD.04X.04")
      (libsource (lib "eagle-import") (part "PAD.04"))
    )
    (comp (ref "S2RX")
      (value "PAD.04")
      (footprint "eagle-import:PAD.04X.04")
      (libsource (lib "eagle-import") (part "PAD.04"))
    )
    (comp (ref "S2TX")
      (value "PAD.04")
      (footprint "eagle-import:PAD.04X.04")
      (libsource (lib "eagle-import") (part "PAD.04"))
    )
    (comp (ref "S3RX")
      (value "PAD.04")
      (footprint "eagle-import:PAD.04X.04")
      (libsource (lib "eagle-import") (part "PAD.04"))
    )
    (comp (ref "S3TX")
      (value "PAD.04")
      (footprint "eagle-import:PAD.04X.04")
      (libsource (lib "eagle-import") (part "PAD.04"))
    )
    (comp (ref "S4RX")
      (value "PAD.04")
      (footprint "eagle-import:PAD.04X.04")
      (libsource (lib "eagle-import") (part "PAD.04"))
    )
    (comp (ref "S4TX")
      (value "PAD.04")
      (footprint "eagle-import:PAD.04X.04")
      (libsource (lib "eagle-import") (part "PAD.04"))
    )
    (comp (ref "S5_RX")
      (value "PAD.04")
      (footprint "eagle-import:PAD.04X.04")
      (libsource (lib "eagle-import") (part "PAD.04"))
    )
    (comp (ref "S5_TX")
      (value "PAD.04")
      (footprint "eagle-import:PAD.04X.04")
      (libsource (lib "eagle-import") (part "PAD.04"))
    )
    (comp (ref "VBUS")
      (value "PAD.04")
      (footprint "eagle-import:PAD.04X.04")
      (libsource (lib "eagle-import") (part "PAD.04"))
    )
    (comp (ref "VDDA_3V1101")
      (value "PAD.04")
      (footprint "eagle-import:PAD.04X.04")
      (libsource (lib "eagle-import") (part "PAD.04"))
    )
    (comp (ref "VDD_3V1101")
      (value "PAD.04")
      (footprint "eagle-import:PAD.04X.04")
      (libsource (lib "eagle-import") (part "PAD.04"))
    )
    (comp (ref "VDD_5V_BRICK")
      (value "PAD.04")
      (footprint "eagle-import:PAD.04X.04")
      (libsource (lib "eagle-import") (part "PAD.04"))
    )
    (comp (ref "VDD_5V_IN")
      (value "PAD.04")
      (footprint "eagle-import:PAD.04X.04")
      (libsource (lib "eagle-import") (part "PAD.04"))
    )
    (comp (ref "VDD_SERVO")
      (value "PAD.04")
      (footprint "eagle-import:PAD.04X.04")
      (libsource (lib "eagle-import") (part "PAD.04"))
    )
    (comp (ref "C1101")
      (value "22u/25V")
      (footprint "eagle-import:0805-CAP")
      (fields (field (name "PARTNO") "CL21A226MAQNNNE"))
      (libsource (lib "eagle-import") (part "CAP0805"))
    )
    (comp (ref "C1102")
      (value "22u/25V")
      (footprint "eagle-import:0805-CAP")
      (fields (field (name "PARTNO") "CL21A226MAQNNNE"))
      (libsource (lib "eagle-import") (part "CAP0805"))
    )
    (comp (ref "C1103")
      (value "22u/25V")
      (footprint "eagle-import:0805-CAP")
      (fields (field (name "PARTNO") "CL21A226MAQNNNE"))
      (libsource (lib "eagle-import") (part "CAP0805"))
    )
    (comp (ref "C1104")
      (value "100u")
      (footprint "eagle-import:1206-CAP")
      (fields (field (name "PARTNO") "C3216X5R1A107M160AC"))
      (libsource (lib "eagle-import") (part "CAP1206"))
    )
    (comp (ref "C1105")
      (value "0u1")
      (footprint "eagle-import:0402-CAP")
      (fields (field (name "PARTNO") "C1005X7R1E104K050BB"))
      (libsource (lib "eagle-import") (part "CAP0402"))
    )
    (comp (ref "C1106")
      (value "0u1")
      (footprint "eagle-import:0402-CAP")
      (fields (field (name "PARTNO") "C1005X7R1E104K050BB"))
      (libsource (lib "eagle-import") (part "CAP0402"))
    )
    (comp (ref "C1107")
      (value "0u1")
      (footprint "eagle-import:0402-CAP")
      (fields (field (name "PARTNO") "C1005X7R1E104K050BB"))
      (libsource (lib "eagle-import") (part "CAP0402"))
    )
    (comp (ref "C1108")
      (value "10p/25V")
      (footprint "eagle-import:0402-CAP")
      (fields (field (name "PARTNO") "C0402C100J3GACTU"))
      (libsource (lib "eagle-import") (part "CAP0402"))
    )
    (comp (ref "C1109")
      (value "10p/25V")
      (footprint "eagle-import:0402-CAP")
      (fields (field (name "PARTNO") "C0402C100J3GACTU"))
      (libsource (lib "eagle-import") (part "CAP0402"))
    )
    (comp (ref "C1110")
      (value "10p/25V")
      (footprint "eagle-import:0402-CAP")
      (fields (field (name "PARTNO") "C0402C100J3GACTU"))
      (libsource (lib "eagle-import") (part "CAP0402"))
    )
    (comp (ref "J601")
      (value "DF13C-6P-1.25V")
      (footprint "eagle-import:DF13C-6P-1.25V")
      (fields (field (name "PARTNO") "DF13C-6P-1.25V(20)"))
      (libsource (lib "eagle-import") (part "DF13-6P-1.25V"))
    )
    (comp (ref "L1101")
      (value "KNH16C104DA5TS")
      (footprint "eagle-import:KYOCERA-KNH16-DA")
      (libsource (lib "eagle-import") (part "KNH16C104DA5TS"))
    )
    (comp (ref "L1102")
      (value "KNH16C104DA5TS")
      (footprint "eagle-import:KYOCERA-KNH16-DA")
      (libsource (lib "eagle-import") (part "KNH16C104DA5TS"))
    )
    (comp (ref "R1101")
      (value "10K/0.1%")
      (footprint "eagle-import:0402-RES")
      (fields (field (name "PARTNO") "ERA-2AEB103X"))
      (libsource (lib "eagle-import") (part "RESISTOR0402-RES"))
    )
    (comp (ref "R1102")
      (value "10K/0.1%")
      (footprint "eagle-import:0402-RES")
      (fields (field (name "PARTNO") "ERA-2AEB103X"))
      (libsource (lib "eagle-import") (part "RESISTOR0402-RES"))
    )
    (comp (ref "R1103")
      (value "1M")
      (footprint "eagle-import:0402-RES")
      (fields (field (name "PARTNO") "RC0402FR-071ML"))
      (libsource (lib "eagle-import") (part "RESISTOR0402-RES"))
    )
    (comp (ref "R1104")
      (value "1M")
      (footprint "eagle-import:0402-RES")
      (fields (field (name "PARTNO") "RC0402FR-071ML"))
      (libsource (lib "eagle-import") (part "RESISTOR0402-RES"))
    )
    (comp (ref "R1105")
      (value "453K")
      (footprint "eagle-import:0402-RES")
      (fields (field (name "PARTNO") "RMCF0402FT453K"))
      (libsource (lib "eagle-import") (part "RESISTOR0402-RES"))
    )
    (comp (ref "R1106")
      (value "56K")
      (footprint "eagle-import:0402-RES")
      (fields (field (name "PARTNO") "ERA-2AEB563X"))
      (libsource (lib "eagle-import") (part "RESISTOR0402-RES"))
    )
    (comp (ref "R1107")
      (value "105K")
      (footprint "eagle-import:0402-RES")
      (fields (field (name "PARTNO") "ERJ-2RKF1053X"))
      (libsource (lib "eagle-import") (part "RESISTOR0402-RES"))
    )
    (comp (ref "R1109")
      (value "453K")
      (footprint "eagle-import:0402-RES")
      (fields (field (name "PARTNO") "RMCF0402FT453K"))
      (libsource (lib "eagle-import") (part "RESISTOR0402-RES"))
    )
    (comp (ref "R1110")
      (value "56K")
      (footprint "eagle-import:0402-RES")
      (fields (field (name "PARTNO") "ERA-2AEB563X"))
      (libsource (lib "eagle-import") (part "RESISTOR0402-RES"))
    )
    (comp (ref "R1111")
      (value "105K")
      (footprint "eagle-import:0402-RES")
      (fields (field (name "PARTNO") "ERJ-2RKF1053X"))
      (libsource (lib "eagle-import") (part "RESISTOR0402-RES"))
    )
    (comp (ref "R1112")
      (value "453K")
      (footprint "eagle-import:0402-RES")
      (fields (field (name "PARTNO") "RMCF0402FT453K"))
      (libsource (lib "eagle-import") (part "RESISTOR0402-RES"))
    )
    (comp (ref "R1113")
      (value "56K")
      (footprint "eagle-import:0402-RES")
      (fields (field (name "PARTNO") "ERA-2AEB563X"))
      (libsource (lib "eagle-import") (part "RESISTOR0402-RES"))
    )
    (comp (ref "R1114")
      (value "105K")
      (footprint "eagle-import:0402-RES")
      (fields (field (name "PARTNO") "ERJ-2RKF1053X"))
      (libsource (lib "eagle-import") (part "RESISTOR0402-RES"))
    )
    (comp (ref "R1115")
      (value "0R")
      (footprint "eagle-import:0402-RES")
      (fields (field (name "PARTNO") "ERJ-2GE0R00X"))
      (libsource (lib "eagle-import") (part "RESISTOR0402-RES"))
    )
    (comp (ref "RN1101")
      (value "1M")
      (footprint "eagle-import:EXB28V")
      (fields (field (name "PARTNO") "EXB-28V105JX"))
      (libsource (lib "eagle-import") (part "4R-NEXB28V"))
    )
    (comp (ref "U1101")
      (value "LTC4417")
      (footprint "eagle-import:MO-220")
      (fields (field (name "PARTNO") "LTC4417IUF#PBF"))
      (libsource (lib "eagle-import") (part "LTC4117"))
    )
    (comp (ref "U1102")
      (value "NTHD4102PT1G")
      (footprint "eagle-import:1206-8")
      (fields (field (name "PARTNO") "NTHD4102PT1G"))
      (libsource (lib "eagle-import") (part "MOSFET-DUAL-PCHANNEL-CHIPFET"))
    )
    (comp (ref "U1103")
      (value "NTHD4102PT1G")
      (footprint "eagle-import:1206-8")
      (fields (field (name "PARTNO") "NTHD4102PT1G"))
      (libsource (lib "eagle-import") (part "MOSFET-DUAL-PCHANNEL-CHIPFET"))
    )
    (comp (ref "U1104")
      (value "NTHD4102PT1G")
      (footprint "eagle-import:1206-8")
      (fields (field (name "PARTNO") "NTHD4102PT1G"))
      (libsource (lib "eagle-import") (part "MOSFET-DUAL-PCHANNEL-CHIPFET"))
    )
    (comp (ref "C501")
      (value "10u/10V")
      (footprint "eagle-import:0805-CAP")
      (fields (field (name "PARTNO") "CC0805ZKY5V6BB106"))
      (libsource (lib "eagle-import") (part "CAP0805"))
    )
    (comp (ref "C502")
      (value "0u1")
      (footprint "eagle-import:0402-CAP")
      (fields (field (name "PARTNO") "CC0402ZRY5V7BB104"))
      (libsource (lib "eagle-import") (part "CAP0402"))
    )
    (comp (ref "C503")
      (value "0u1")
      (footprint "eagle-import:0402-CAP")
      (fields (field (name "PARTNO") "CC0402ZRY5V7BB104"))
      (libsource (lib "eagle-import") (part "CAP0402"))
    )
    (comp (ref "C504")
      (value "10n")
      (footprint "eagle-import:0402-CAP")
      (fields (field (name "PARTNO") "CC0402KRX7R7BB103"))
      (libsource (lib "eagle-import") (part "CAP0402"))
    )
    (comp (ref "C505")
      (value "10n")
      (footprint "eagle-import:0402-CAP")
      (fields (field (name "PARTNO") "CC0402KRX7R7BB103"))
      (libsource (lib "eagle-import") (part "CAP0402"))
    )
    (comp (ref "C506")
      (value "10u/10V")
      (footprint "eagle-import:0805-CAP")
      (fields (field (name "PARTNO") "CC0805ZKY5V6BB106"))
      (libsource (lib "eagle-import") (part "CAP0805"))
    )
    (comp (ref "C507")
      (value "0u1")
      (footprint "eagle-import:0402-CAP")
      (fields (field (name "PARTNO") "CC0402ZRY5V7BB104"))
      (libsource (lib "eagle-import") (part "CAP0402"))
    )
    (comp (ref "C508")
      (value "0u1")
      (footprint "eagle-import:0402-CAP")
      (fields (field (name "PARTNO") "CC0402ZRY5V7BB104"))
      (libsource (lib "eagle-import") (part "CAP0402"))
    )
    (comp (ref "C509")
      (value "10u/10V")
      (footprint "eagle-import:0805-CAP")
      (fields (field (name "PARTNO") "CC0805ZKY5V6BB106"))
      (libsource (lib "eagle-import") (part "CAP0805"))
    )
    (comp (ref "C510")
      (value "0u47")
      (footprint "eagle-import:0402-CAP")
      (fields (field (name "PARTNO") "C1005X5R1C474K050BC"))
      (libsource (lib "eagle-import") (part "CAP0402"))
    )
    (comp (ref "C511")
      (value "10u/10V")
      (footprint "eagle-import:0805-CAP")
      (fields (field (name "PARTNO") "CC0805ZKY5V6BB106"))
      (libsource (lib "eagle-import") (part "CAP0805"))
    )
    (comp (ref "C512")
      (value "2u2")
      (footprint "eagle-import:0603-CAP")
      (fields (field (name "PARTNO") "C1608X6S1C225K080AC"))
      (libsource (lib "eagle-import") (part "CAP0603"))
    )
    (comp (ref "C513")
      (value "2u2")
      (footprint "eagle-import:0603-CAP")
      (fields (field (name "PARTNO") "C1608X6S1C225K080AC"))
      (libsource (lib "eagle-import") (part "CAP0603"))
    )
    (comp (ref "C514")
      (value "0u1")
      (footprint "eagle-import:0402-CAP")
      (fields (field (name "PARTNO") "CC0402ZRY5V7BB104"))
      (libsource (lib "eagle-import") (part "CAP0402"))
    )
    (comp (ref "C515")
      (value "0u01")
      (footprint "eagle-import:0603-CAP")
      (fields (field (name "PARTNO") "06033C103JAT2A"))
      (libsource (lib "eagle-import") (part "CAP0603"))
    )
    (comp (ref "U501")
      (value "L3GD20")
      (footprint "eagle-import:L3G4200DH-MAN")
      (libsource (lib "eagle-import") (part "L3G4200DH-LL"))
    )
    (comp (ref "U502")
      (value "L3GD20H")
      (footprint "eagle-import:LGA-16L")
      (libsource (lib "eagle-import") (part "L3GD20H"))
    )
    (comp (ref "U504")
      (value "LSM303D")
      (footprint "eagle-import:LGA-16L")
      (libsource (lib "eagle-import") (part "LSM303D"))
    )
    (comp (ref "U505")
      (value "MPU-6000")
      (footprint "eagle-import:QFN-24")
      (libsource (lib "eagle-import") (part "MPU-6000"))
    )
    (comp (ref "U506")
      (value "MS5611-01BA")
      (footprint "eagle-import:MS5611-01BA")
      (libsource (lib "eagle-import") (part "MS5611-01BA"))
    )
    (comp (ref "X503")
      (value "0512811094")
      (footprint "eagle-import:51281-1094")
      (fields (field (name "PARTNO") "0781191109") (field (name "BOM") "EXCLUDE"))
      (libsource (lib "eagle-import") (part "CONN_FPC_10RA"))
    )
    (comp (ref "C201")
      (value "0u1")
      (footprint "eagle-import:0402-CAP")
      (fields (field (name "PARTNO") "CC0402ZRY5V7BB104"))
      (libsource (lib "eagle-import") (part "CAP0402"))
    )
    (comp (ref "C202")
      (value "0u1")
      (footprint "eagle-import:0402-CAP")
      (fields (field (name "PARTNO") "CC0402ZRY5V7BB104"))
      (libsource (lib "eagle-import") (part "CAP0402"))
    )
    (comp (ref "D201")
      (value "PESD0402-140")
      (footprint "eagle-import:0402-TVS")
      (libsource (lib "eagle-import") (part "DIODE-TVS"))
    )
    (comp (ref "D202")
      (value "PESD0402-140")
      (footprint "eagle-import:0402-TVS")
      (libsource (lib "eagle-import") (part "DIODE-TVS"))
    )
    (comp (ref "D203")
      (value "PESD0402-140")
      (footprint "eagle-import:0402-TVS")
      (libsource (lib "eagle-import") (part "DIODE-TVS"))
    )
    (comp (ref "J201")
      (value "DF13C-6P-1.25V")
      (footprint "eagle-import:DF13C-6P-1.25V")
      (fields (field (name "PARTNO") "DF13C-6P-1.25V(20)"))
      (libsource (lib "eagle-import") (part "DF13-6P-1.25V"))
    )
    (comp (ref "J202")
      (value "DF13C-6P-1.25V")
      (footprint "eagle-import:DF13C-6P-1.25V")
      (fields (field (name "PARTNO") "DF13C-6P-1.25V(20)"))
      (libsource (lib "eagle-import") (part "DF13-6P-1.25V"))
    )
    (comp (ref "J203")
      (value "DF13C-6P-1.25V")
      (footprint "eagle-import:DF13C-6P-1.25V")
      (fields (field (name "PARTNO") "DF13C-6P-1.25V(20)"))
      (libsource (lib "eagle-import") (part "DF13-6P-1.25V"))
    )
    (comp (ref "J204")
      (value "DF13C-6P-1.25V")
      (footprint "eagle-import:DF13C-6P-1.25V")
      (fields (field (name "PARTNO") "DF13C-6P-1.25V(20)"))
      (libsource (lib "eagle-import") (part "DF13-6P-1.25V"))
    )
    (comp (ref "L201")
      (value "KNH16C104DA5TS")
      (footprint "eagle-import:KYOCERA-KNH16-DA")
      (libsource (lib "eagle-import") (part "KNH16C104DA5TS"))
    )
    (comp (ref "L202")
      (value "KNH16C104DA5TS")
      (footprint "eagle-import:KYOCERA-KNH16-DA")
      (libsource (lib "eagle-import") (part "KNH16C104DA5TS"))
    )
    (comp (ref "L203")
      (value "KNH16C104DA5TS")
      (footprint "eagle-import:KYOCERA-KNH16-DA")
      (libsource (lib "eagle-import") (part "KNH16C104DA5TS"))
    )
    (comp (ref "R201")
      (value "120R")
      (footprint "eagle-import:0402-RES")
      (fields (field (name "PARTNO") "RC0402FR-07120RL"))
      (libsource (lib "eagle-import") (part "RESISTOR0402-RES"))
    )
    (comp (ref "R202")
      (value "120R")
      (footprint "eagle-import:0402-RES")
      (fields (field (name "PARTNO") "RC0402FR-07120RL"))
      (libsource (lib "eagle-import") (part "RESISTOR0402-RES"))
    )
    (comp (ref "R203")
      (value "120R")
      (footprint "eagle-import:0402-RES")
      (fields (field (name "PARTNO") "RC0402FR-07120RL"))
      (libsource (lib "eagle-import") (part "RESISTOR0402-RES"))
    )
    (comp (ref "R204")
      (value "120R")
      (footprint "eagle-import:0402-RES")
      (fields (field (name "PARTNO") "RC0402FR-07120RL"))
      (libsource (lib "eagle-import") (part "RESISTOR0402-RES"))
    )
    (comp (ref "R205")
      (value "120R")
      (footprint "eagle-import:0402-RES")
      (fields (field (name "PARTNO") "RC0402FR-07120RL"))
      (libsource (lib "eagle-import") (part "RESISTOR0402-RES"))
    )
    (comp (ref "R206")
      (value "120R")
      (footprint "eagle-import:0402-RES")
      (fields (field (name "PARTNO") "RC0402FR-07120RL"))
      (libsource (lib "eagle-import") (part "RESISTOR0402-RES"))
    )
    (comp (ref "R207")
      (value "120R")
      (footprint "eagle-import:0402-RES")
      (fields (field (name "PARTNO") "RC0402FR-07120RL"))
      (libsource (lib "eagle-import") (part "RESISTOR0402-RES"))
    )
    (comp (ref "R208")
      (value "120R")
      (footprint "eagle-import:0402-RES")
      (fields (field (name "PARTNO") "RC0402FR-07120RL"))
      (libsource (lib "eagle-import") (part "RESISTOR0402-RES"))
    )
    (comp (ref "R209")
      (value "120R")
      (footprint "eagle-import:0402-RES")
      (fields (field (name "PARTNO") "RC0402FR-07120RL"))
      (libsource (lib "eagle-import") (part "RESISTOR0402-RES"))
    )
    (comp (ref "R210")
      (value "120R")
      (footprint "eagle-import:0402-RES")
      (fields (field (name "PARTNO") "RC0402FR-07120RL"))
      (libsource (lib "eagle-import") (part "RESISTOR0402-RES"))
    )
    (comp (ref "R211")
      (value "120R")
      (footprint "eagle-import:0402-RES")
      (fields (field (name "PARTNO") "RC0402FR-07120RL"))
      (libsource (lib "eagle-import") (part "RESISTOR0402-RES"))
    )
    (comp (ref "R212")
      (value "120R")
      (footprint "eagle-import:0402-RES")
      (fields (field (name "PARTNO") "RC0402FR-07120RL"))
      (libsource (lib "eagle-import") (part "RESISTOR0402-RES"))
    )
    (comp (ref "R213")
      (value "120R")
      (footprint "eagle-import:0402-RES")
      (fields (field (name "PARTNO") "RC0402FR-07120RL"))
      (libsource (lib "eagle-import") (part "RESISTOR0402-RES"))
    )
    (comp (ref "R214")
      (value "120R")
      (footprint "eagle-import:0402-RES")
      (fields (field (name "PARTNO") "RC0402FR-07120RL"))
      (libsource (lib "eagle-import") (part "RESISTOR0402-RES"))
    )
    (comp (ref "R215")
      (value "120R")
      (footprint "eagle-import:0402-RES")
      (fields (field (name "PARTNO") "RC0402FR-07120RL"))
      (libsource (lib "eagle-import") (part "RESISTOR0402-RES"))
    )
    (comp (ref "R216")
      (value "120R")
      (footprint "eagle-import:0402-RES")
      (fields (field (name "PARTNO") "RC0402FR-07120RL"))
      (libsource (lib "eagle-import") (part "RESISTOR0402-RES"))
    )
    (comp (ref "U201")
      (value "TXS0108QFN20")
      (footprint "eagle-import:QFN20-RGY")
      (fields (field (name "PARTNO") "TXS0108ERGYR"))
      (libsource (lib "eagle-import") (part "TXS0108QFN20"))
    )
    (comp (ref "U202")
      (value "TXS0108QFN20")
      (footprint "eagle-import:QFN20-RGY")
      (fields (field (name "PARTNO") "TXS0108ERGYR"))
      (libsource (lib "eagle-import") (part "TXS0108QFN20"))
    )
    (comp (ref "C901")
      (value "0u1")
      (footprint "eagle-import:0402-CAP")
      (fields (field (name "PARTNO") "CC0402ZRY5V7BB104"))
      (libsource (lib "eagle-import") (part "CAP0402"))
    )
    (comp (ref "C902")
      (value "0u1")
      (footprint "eagle-import:0402-CAP")
      (fields (field (name "PARTNO") "CC0402ZRY5V7BB104"))
      (libsource (lib "eagle-import") (part "CAP0402"))
    )
    (comp (ref "C903")
      (value "0u1")
      (footprint "eagle-import:0402-CAP")
      (fields (field (name "PARTNO") "CC0402ZRY5V7BB104"))
      (libsource (lib "eagle-import") (part "CAP0402"))
    )
    (comp (ref "D901")
      (value "PESD0402-140")
      (footprint "eagle-import:0402-TVS")
      (libsource (lib "eagle-import") (part "DIODE-TVS"))
    )
    (comp (ref "D902")
      (value "PESD0402-140")
      (footprint "eagle-import:0402-TVS")
      (libsource (lib "eagle-import") (part "DIODE-TVS"))
    )
    (comp (ref "D903")
      (value "PESD0402-140")
      (footprint "eagle-import:0402-TVS")
      (libsource (lib "eagle-import") (part "DIODE-TVS"))
    )
    (comp (ref "D904")
      (value "MSS1P4-M3")
      (footprint "eagle-import:MICROSMP")
      (fields (field (name "PARTNO") "MSS1P4-M3/89A"))
      (libsource (lib "eagle-import") (part "DIODE-SCHOTTKY_MSMP"))
    )
    (comp (ref "J901")
      (value "HEADER-3X163X16RA")
      (footprint "eagle-import:3X16RA")
      (fields (field (name "BOM") "EXCLUDE"))
      (libsource (lib "eagle-import") (part "HEADER-3X163X16RA"))
    )
    (comp (ref "L901")
      (value "KNH16C104DA5TS")
      (footprint "eagle-import:KYOCERA-KNH16-DA")
      (libsource (lib "eagle-import") (part "KNH16C104DA5TS"))
    )
    (comp (ref "R901")
      (value "10K")
      (footprint "eagle-import:0402-RES")
      (fields (field (name "PARTNO") "RC0402FR-0710KL"))
      (libsource (lib "eagle-import") (part "RESISTOR0402-RES"))
    )
    (comp (ref "R902")
      (value "220R")
      (footprint "eagle-import:0402-RES")
      (fields (field (name "PARTNO") "RC0402FR-07220RL"))
      (libsource (lib "eagle-import") (part "RESISTOR0402-RES"))
    )
    (comp (ref "R903")
      (value "220R")
      (footprint "eagle-import:0402-RES")
      (fields (field (name "PARTNO") "RC0402FR-07220RL"))
      (libsource (lib "eagle-import") (part "RESISTOR0402-RES"))
    )
    (comp (ref "R904")
      (value "220R")
      (footprint "eagle-import:0402-RES")
      (fields (field (name "PARTNO") "RC0402FR-07220RL"))
      (libsource (lib "eagle-import") (part "RESISTOR0402-RES"))
    )
    (comp (ref "R905")
      (value "220R")
      (footprint "eagle-import:0402-RES")
      (fields (field (name "PARTNO") "RC0402FR-07220RL"))
      (libsource (lib "eagle-import") (part "RESISTOR0402-RES"))
    )
    (comp (ref "R906")
      (value "220R")
      (footprint "eagle-import:0402-RES")
      (fields (field (name "PARTNO") "RC0402FR-07220RL"))
      (libsource (lib "eagle-import") (part "RESISTOR0402-RES"))
    )
    (comp (ref "R907")
      (value "220R")
      (footprint "eagle-import:0402-RES")
      (fields (field (name "PARTNO") "RC0402FR-07220RL"))
      (libsource (lib "eagle-import") (part "RESISTOR0402-RES"))
    )
    (comp (ref "R908")
      (value "220R")
      (footprint "eagle-import:0402-RES")
      (fields (field (name "PARTNO") "RC0402FR-07220RL"))
      (libsource (lib "eagle-import") (part "RESISTOR0402-RES"))
    )
    (comp (ref "R909")
      (value "220R")
      (footprint "eagle-import:0402-RES")
      (fields (field (name "PARTNO") "RC0402FR-07220RL"))
      (libsource (lib "eagle-import") (part "RESISTOR0402-RES"))
    )
    (comp (ref "R910")
      (value "220R")
      (footprint "eagle-import:0402-RES")
      (fields (field (name "PARTNO") "RC0402FR-07220RL"))
      (libsource (lib "eagle-import") (part "RESISTOR0402-RES"))
    )
    (comp (ref "R911")
      (value "220R")
      (footprint "eagle-import:0402-RES")
      (fields (field (name "PARTNO") "RC0402FR-07220RL"))
      (libsource (lib "eagle-import") (part "RESISTOR0402-RES"))
    )
    (comp (ref "R912")
      (value "220R")
      (footprint "eagle-import:0402-RES")
      (fields (field (name "PARTNO") "RC0402FR-07220RL"))
      (libsource (lib "eagle-import") (part "RESISTOR0402-RES"))
    )
    (comp (ref "R913")
      (value "220R")
      (footprint "eagle-import:0402-RES")
      (fields (field (name "PARTNO") "RC0402FR-07220RL"))
      (libsource (lib "eagle-import") (part "RESISTOR0402-RES"))
    )
    (comp (ref "R914")
      (value "220R")
      (footprint "eagle-import:0402-RES")
      (fields (field (name "PARTNO") "RC0402FR-07220RL"))
      (libsource (lib "eagle-import") (part "RESISTOR0402-RES"))
    )
    (comp (ref "R915")
      (value "220R")
      (footprint "eagle-import:0402-RES")
      (fields (field (name "PARTNO") "RC0402FR-07220RL"))
      (libsource (lib "eagle-import") (part "RESISTOR0402-RES"))
    )
    (comp (ref "R916")
      (value "220R")
      (footprint "eagle-import:0402-RES")
      (fields (field (name "PARTNO") "RC0402FR-07220RL"))
      (libsource (lib "eagle-import") (part "RESISTOR0402-RES"))
    )
    (comp (ref "R917")
      (value "220R")
      (footprint "eagle-import:0402-RES")
      (fields (field (name "PARTNO") "RC0402FR-07220RL"))
      (libsource (lib "eagle-import") (part "RESISTOR0402-RES"))
    )
    (comp (ref "R918")
      (value "10K/0.1%")
      (footprint "eagle-import:0402-RES")
      (fields (field (name "PARTNO") "ERA-2AEB103X"))
      (libsource (lib "eagle-import") (part "RESISTOR0402-RES"))
    )
    (comp (ref "R919")
      (value "10K/0.1%")
      (footprint "eagle-import:0402-RES")
      (fields (field (name "PARTNO") "ERA-2AEB103X"))
      (libsource (lib "eagle-import") (part "RESISTOR0402-RES"))
    )
    (comp (ref "R922")
      (value "10K/0.1%")
      (footprint "eagle-import:0402-RES")
      (fields (field (name "PARTNO") "ERA-2AEB103X"))
      (libsource (lib "eagle-import") (part "RESISTOR0402-RES"))
    )
    (comp (ref "U901")
      (value "TXS0108QFN20")
      (footprint "eagle-import:QFN20-RGY")
      (fields (field (name "PARTNO") "TXS0108ERGYR"))
      (libsource (lib "eagle-import") (part "TXS0108QFN20"))
    )
    (comp (ref "U902")
      (value "TXS0108QFN20")
      (footprint "eagle-import:QFN20-RGY")
      (fields (field (name "PARTNO") "TXS0108ERGYR"))
      (libsource (lib "eagle-import") (part "TXS0108QFN20"))
    )
    (comp (ref "U903")
      (value "74LVC2G240")
      (footprint "eagle-import:TSSOP8_SOT505-2")
      (fields (field (name "PARTNO") "74LVC2G240DP,125"))
      (libsource (lib "eagle-import") (part "74LVC2G240-TSSOP-8"))
    )
    (comp (ref "J301")
      (value "47346-0001")
      (footprint "eagle-import:MOLEX-47346-0001")
      (libsource (lib "eagle-import") (part "MOLEX-47346-0001"))
    )
    (comp (ref "J302")
      (value "DF13C-4P-1.25V")
      (footprint "eagle-import:DF13C-4P-1.25V")
      (fields (field (name "PARTNO") "DF13C-4P-1.25V(20)"))
      (libsource (lib "eagle-import") (part "DF13-4P-1.25V"))
    )
    (comp (ref "JX301")
      (value "ARM_MINI_JTAG-SMT")
      (footprint "eagle-import:FTSH-105-01-XXX-DV-K")
      (fields (field (name "BOM") "EXCLUDE") (field (name "PARTNO") "M50-3900542"))
      (libsource (lib "eagle-import") (part "ARM_MINI_JTAG-SMT"))
    )
    (comp (ref "R301")
      (value "100K")
      (footprint "eagle-import:0402-RES")
      (fields (field (name "PARTNO") "RC0402FR-07100KL"))
      (libsource (lib "eagle-import") (part "RESISTOR0402-RES"))
    )
    (comp (ref "R302")
      (value "100K")
      (footprint "eagle-import:0402-RES")
      (fields (field (name "PARTNO") "RC0402FR-07100KL"))
      (libsource (lib "eagle-import") (part "RESISTOR0402-RES"))
    )
    (comp (ref "R303")
      (value "100K")
      (footprint "eagle-import:0402-RES")
      (fields (field (name "PARTNO") "RC0402FR-07100KL"))
      (libsource (lib "eagle-import") (part "RESISTOR0402-RES"))
    )
    (comp (ref "R304")
      (value "100K")
      (footprint "eagle-import:0402-RES")
      (fields (field (name "PARTNO") "RC0402FR-07100KL"))
      (libsource (lib "eagle-import") (part "RESISTOR0402-RES"))
    )
    (comp (ref "R305")
      (value "100K")
      (footprint "eagle-import:0402-RES")
      (fields (field (name "PARTNO") "RC0402FR-07100KL"))
      (libsource (lib "eagle-import") (part "RESISTOR0402-RES"))
    )
    (comp (ref "R306")
      (value "1K5")
      (footprint "eagle-import:0402-RES")
      (fields (field (name "PARTNO") "RC0402FR-071K5L"))
      (libsource (lib "eagle-import") (part "RESISTOR0402-RES"))
    )
    (comp (ref "R307")
      (value "1K5")
      (footprint "eagle-import:0402-RES")
      (fields (field (name "PARTNO") "RC0402FR-071K5L"))
      (libsource (lib "eagle-import") (part "RESISTOR0402-RES"))
    )
    (comp (ref "U301")
      (value "2908-05WB-MG")
      (footprint "eagle-import:MICROSD")
      (libsource (lib "eagle-import") (part "MICROSDSDI"))
    )
    (comp (ref "U302")
      (value "NUF2042XV6")
      (footprint "eagle-import:SOT563-6")
      (fields (field (name "PARTNO") "NUF2042XV6T1G"))
      (libsource (lib "eagle-import") (part "NUF2042XV6"))
    )
    (comp (ref "C701")
      (value "0u1")
      (footprint "eagle-import:0402-CAP")
      (fields (field (name "PARTNO") "CC0402ZRY5V7BB104"))
      (libsource (lib "eagle-import") (part "CAP0402"))
    )
    (comp (ref "C702")
      (value "1u")
      (footprint "eagle-import:0603-CAP")
      (fields (field (name "PARTNO") "CC0603ZRY5V7BB105"))
      (libsource (lib "eagle-import") (part "CAP0603"))
    )
    (comp (ref "C703")
      (value "5n6")
      (footprint "eagle-import:0402-CAP")
      (fields (field (name "PARTNO") "C0402C562K5RACTU"))
      (libsource (lib "eagle-import") (part "CAP0402"))
    )
    (comp (ref "C704")
      (value "0u47")
      (footprint "eagle-import:0402-CAP")
      (fields (field (name "PARTNO") "C1005X5R1C474K050BC"))
      (libsource (lib "eagle-import") (part "CAP0402"))
    )
    (comp (ref "D701")
      (value "PESD0402-140")
      (footprint "eagle-import:0402-TVS")
      (libsource (lib "eagle-import") (part "DIODE-TVS"))
    )
    (comp (ref "J701")
      (value "DF13C-2P-1.25V")
      (footprint "eagle-import:DF13C-2P-1.25V")
      (fields (field (name "PARTNO") "DF13C-2P-1.25V(20)"))
      (libsource (lib "eagle-import") (part "DF13-2P-1.25V"))
    )
    (comp (ref "J702")
      (value "DF13C-3P-1.25V")
      (footprint "eagle-import:DF13C-3P-1.25V")
      (fields (field (name "PARTNO") "DF13C-3P-1.25V(20)"))
      (libsource (lib "eagle-import") (part "DF13-3P-1.25V"))
    )
    (comp (ref "L701")
      (value "47uH")
      (footprint "eagle-import:0805-IND")
      (fields (field (name "PARTNO") "MLZ2012M470W"))
      (libsource (lib "eagle-import") (part "INDUCTOR0805"))
    )
    (comp (ref "LED701")
      (value "AMBER")
      (footprint "eagle-import:0603-LED")
      (fields (field (name "PARTNO") "APTD1608SECK"))
      (libsource (lib "eagle-import") (part "LED0603"))
    )
    (comp (ref "LED702")
      (value "GREEN")
      (footprint "eagle-import:0603-LED")
      (fields (field (name "PARTNO") "APTD1608CGCK"))
      (libsource (lib "eagle-import") (part "LED0603"))
    )
    (comp (ref "LED703")
      (value "AMBER")
      (footprint "eagle-import:0603-LED")
      (fields (field (name "PARTNO") "APTD1608SECK"))
      (libsource (lib "eagle-import") (part "LED0603"))
    )
    (comp (ref "LED704")
      (value "GREEN")
      (footprint "eagle-import:0603-LED")
      (fields (field (name "PARTNO") "APTD1608CGCK"))
      (libsource (lib "eagle-import") (part "LED0603"))
    )
    (comp (ref "LED705")
      (value "BLUE")
      (footprint "eagle-import:0603-LED")
      (fields (field (name "PARTNO") "APTD1608QBC/D"))
      (libsource (lib "eagle-import") (part "LED0603"))
    )
    (comp (ref "R701")
      (value "9K09")
      (footprint "eagle-import:0402-RES")
      (fields (field (name "PARTNO") "RMCF0402FT9K09"))
      (libsource (lib "eagle-import") (part "RESISTOR0402-RES"))
    )
    (comp (ref "R702")
      (value "10K")
      (footprint "eagle-import:0402-RES")
      (fields (field (name "PARTNO") "RC0402FR-0710KL"))
      (libsource (lib "eagle-import") (part "RESISTOR0402-RES"))
    )
    (comp (ref "R703")
      (value "100K")
      (footprint "eagle-import:0402-RES")
      (fields (field (name "PARTNO") "RC0402FR-07100KL"))
      (libsource (lib "eagle-import") (part "RESISTOR0402-RES"))
    )
    (comp (ref "R704")
      (value "10K")
      (footprint "eagle-import:0402-RES")
      (fields (field (name "PARTNO") "RC0402FR-0710KL"))
      (libsource (lib "eagle-import") (part "RESISTOR0402-RES"))
    )
    (comp (ref "R705")
      (value "453K")
      (footprint "eagle-import:0402-RES")
      (fields (field (name "PARTNO") "RMCF0402FT453K"))
      (libsource (lib "eagle-import") (part "RESISTOR0402-RES"))
    )
    (comp (ref "R706")
      (value "16K5")
      (footprint "eagle-import:0402-RES")
      (fields (field (name "PARTNO") "RMCF0402FT16K5"))
      (libsource (lib "eagle-import") (part "RESISTOR0402-RES"))
    )
    (comp (ref "R707")
      (value "220R")
      (footprint "eagle-import:0402-RES")
      (fields (field (name "PARTNO") "RC0402FR-07220RL"))
      (libsource (lib "eagle-import") (part "RESISTOR0402-RES"))
    )
    (comp (ref "R708")
      (value "220R")
      (footprint "eagle-import:0402-RES")
      (fields (field (name "PARTNO") "RC0402FR-07220RL"))
      (libsource (lib "eagle-import") (part "RESISTOR0402-RES"))
    )
    (comp (ref "R709")
      (value "220R")
      (footprint "eagle-import:0402-RES")
      (fields (field (name "PARTNO") "RC0402FR-07220RL"))
      (libsource (lib "eagle-import") (part "RESISTOR0402-RES"))
    )
    (comp (ref "R710")
      (value "68R")
      (footprint "eagle-import:0402-RES")
      (fields (field (name "PARTNO") "ERJ-2GEJ680X"))
      (libsource (lib "eagle-import") (part "RESISTOR0402-RES"))
    )
    (comp (ref "R711")
      (value "220R")
      (footprint "eagle-import:0402-RES")
      (fields (field (name "PARTNO") "RC0402FR-07220RL"))
      (libsource (lib "eagle-import") (part "RESISTOR0402-RES"))
    )
    (comp (ref "R712")
      (value "220R")
      (footprint "eagle-import:0402-RES")
      (fields (field (name "PARTNO") "RC0402FR-07220RL"))
      (libsource (lib "eagle-import") (part "RESISTOR0402-RES"))
    )
    (comp (ref "R713")
      (value "1K5")
      (footprint "eagle-import:0402-RES")
      (fields (field (name "PARTNO") "RC0402FR-071K5L"))
      (libsource (lib "eagle-import") (part "RESISTOR0402-RES"))
    )
    (comp (ref "R735")
      (value "220R")
      (footprint "eagle-import:0402-RES")
      (fields (field (name "PARTNO") "RC0402FR-07220RL"))
      (libsource (lib "eagle-import") (part "RESISTOR0402-RES"))
    )
    (comp (ref "R736")
      (value "220R")
      (footprint "eagle-import:0402-RES")
      (fields (field (name "PARTNO") "RC0402FR-07220RL"))
      (libsource (lib "eagle-import") (part "RESISTOR0402-RES"))
    )
    (comp (ref "U701")
      (value "TCA62724FMG")
      (footprint "eagle-import:SON10")
      (libsource (lib "eagle-import") (part "TCA62724FMG"))
    )
    (comp (ref "U702")
      (value "LT3469")
      (footprint "eagle-import:SOT23-8")
      (fields (field (name "PARTNO") "LT3469ETS8"))
      (libsource (lib "eagle-import") (part "LT3469"))
    )
    (comp (ref "U703")
      (value "LRTB GFTG-T7AW-1+V7A7-29+R5T9-49-L")
      (footprint "eagle-import:6-PLCC")
      (fields (field (name "PARTNO") "LRTB GFTG-T7AW-1+V7A7-29+R5T9-49-L"))
      (libsource (lib "eagle-import") (part "RGB-LED6-PLCC"))
    )
    (comp (ref "C401")
      (value "0u1")
      (footprint "eagle-import:0402-CAP")
      (fields (field (name "PARTNO") "CC0402ZRY5V7BB104"))
      (libsource (lib "eagle-import") (part "CAP0402"))
    )
    (comp (ref "C402")
      (value "0u1")
      (footprint "eagle-import:0402-CAP")
      (fields (field (name "PARTNO") "CC0402ZRY5V7BB104"))
      (libsource (lib "eagle-import") (part "CAP0402"))
    )
    (comp (ref "D401")
      (value "PESD0402-140")
      (footprint "eagle-import:0402-TVS")
      (libsource (lib "eagle-import") (part "DIODE-TVS"))
    )
    (comp (ref "D402")
      (value "PESD0402-140")
      (footprint "eagle-import:0402-TVS")
      (libsource (lib "eagle-import") (part "DIODE-TVS"))
    )
    (comp (ref "D403")
      (value "PESD0402-140")
      (footprint "eagle-import:0402-TVS")
      (libsource (lib "eagle-import") (part "DIODE-TVS"))
    )
    (comp (ref "D404")
      (value "PESD0402-140")
      (footprint "eagle-import:0402-TVS")
      (libsource (lib "eagle-import") (part "DIODE-TVS"))
    )
    (comp (ref "J401")
      (value "DF13C-4P-1.25V")
      (footprint "eagle-import:DF13C-4P-1.25V")
      (fields (field (name "PARTNO") "DF13C-4P-1.25V(20)"))
      (libsource (lib "eagle-import") (part "DF13-4P-1.25V"))
    )
    (comp (ref "J402")
      (value "DF13C-3P-1.25V")
      (footprint "eagle-import:DF13C-3P-1.25V")
      (fields (field (name "PARTNO") "DF13C-3P-1.25V(20)"))
      (libsource (lib "eagle-import") (part "DF13-3P-1.25V"))
    )
    (comp (ref "J403")
      (value "DF13C-7P-1.25V")
      (footprint "eagle-import:DF13C-7P-1.25V")
      (fields (field (name "PARTNO") "DF13C-7P-1.25V(20)"))
      (libsource (lib "eagle-import") (part "DF13-7P-1.25V"))
    )
    (comp (ref "J404")
      (value "DF13C-5P-1.25V")
      (footprint "eagle-import:DF13C-5P-1.25V")
      (fields (field (name "PARTNO") "DF13C-5P-1.25V(20)"))
      (libsource (lib "eagle-import") (part "DF13-5P-1.25V"))
    )
    (comp (ref "J405")
      (value "DF13C-4P-1.25V")
      (footprint "eagle-import:DF13C-4P-1.25V")
      (fields (field (name "PARTNO") "DF13C-4P-1.25V(20)"))
      (libsource (lib "eagle-import") (part "DF13-4P-1.25V"))
    )
    (comp (ref "L401")
      (value "KNH16C104DA5TS")
      (footprint "eagle-import:KYOCERA-KNH16-DA")
      (libsource (lib "eagle-import") (part "KNH16C104DA5TS"))
    )
    (comp (ref "L402")
      (value "KNH16C104DA5TS")
      (footprint "eagle-import:KYOCERA-KNH16-DA")
      (libsource (lib "eagle-import") (part "KNH16C104DA5TS"))
    )
    (comp (ref "L403")
      (value "KNH16C104DA5TS")
      (footprint "eagle-import:KYOCERA-KNH16-DA")
      (libsource (lib "eagle-import") (part "KNH16C104DA5TS"))
    )
    (comp (ref "L404")
      (value "KNH16C104DA5TS")
      (footprint "eagle-import:KYOCERA-KNH16-DA")
      (libsource (lib "eagle-import") (part "KNH16C104DA5TS"))
    )
    (comp (ref "R401")
      (value "1K5")
      (footprint "eagle-import:0402-RES")
      (fields (field (name "PARTNO") "RC0402FR-071K5L"))
      (libsource (lib "eagle-import") (part "RESISTOR0402-RES"))
    )
    (comp (ref "R402")
      (value "1K5")
      (footprint "eagle-import:0402-RES")
      (fields (field (name "PARTNO") "RC0402FR-071K5L"))
      (libsource (lib "eagle-import") (part "RESISTOR0402-RES"))
    )
    (comp (ref "R403")
      (value "10K/0.1%")
      (footprint "eagle-import:0402-RES")
      (fields (field (name "PARTNO") "ERA-2AEB103X"))
      (libsource (lib "eagle-import") (part "RESISTOR0402-RES"))
    )
    (comp (ref "R404")
      (value "120R")
      (footprint "eagle-import:0402-RES")
      (fields (field (name "PARTNO") "RC0402FR-07120RL"))
      (libsource (lib "eagle-import") (part "RESISTOR0402-RES"))
    )
    (comp (ref "R405")
      (value "120R")
      (footprint "eagle-import:0402-RES")
      (fields (field (name "PARTNO") "RC0402FR-07120RL"))
      (libsource (lib "eagle-import") (part "RESISTOR0402-RES"))
    )
    (comp (ref "R406")
      (value "10K/0.1%")
      (footprint "eagle-import:0402-RES")
      (fields (field (name "PARTNO") "ERA-2AEB103X"))
      (libsource (lib "eagle-import") (part "RESISTOR0402-RES"))
    )
    (comp (ref "R407")
      (value "10K/0.1%")
      (footprint "eagle-import:0402-RES")
      (fields (field (name "PARTNO") "ERA-2AEB103X"))
      (libsource (lib "eagle-import") (part "RESISTOR0402-RES"))
    )
    (comp (ref "R408")
      (value "10K/0.1%")
      (footprint "eagle-import:0402-RES")
      (fields (field (name "PARTNO") "ERA-2AEB103X"))
      (libsource (lib "eagle-import") (part "RESISTOR0402-RES"))
    )
    (comp (ref "R409")
      (value "120R")
      (footprint "eagle-import:0402-RES")
      (fields (field (name "PARTNO") "RC0402FR-07120RL"))
      (libsource (lib "eagle-import") (part "RESISTOR0402-RES"))
    )
    (comp (ref "U401")
      (value "MAX3051")
      (footprint "eagle-import:SOT23-8")
      (fields (field (name "PARTNO") "MAX3051EKA"))
      (libsource (lib "eagle-import") (part "MAX3051MAX3051EKA"))
    )
    (comp (ref "B601")
      (value "MS621FE")
      (footprint "eagle-import:MS621FE")
      (fields (field (name "PARTNO") "MS621FE-FL11E"))
      (libsource (lib "eagle-import") (part "MS621FE"))
    )
    (comp (ref "C601")
      (value "10u/25V")
      (footprint "eagle-import:0805-CAP")
      (fields (field (name "PARTNO") "CL21A106KAYNNNE"))
      (libsource (lib "eagle-import") (part "CAP0805"))
    )
    (comp (ref "C602")
      (value "10n")
      (footprint "eagle-import:0402-CAP")
      (fields (field (name "PARTNO") "CC0402KRX7R7BB103"))
      (libsource (lib "eagle-import") (part "CAP0402"))
    )
    (comp (ref "C603")
      (value "1u")
      (footprint "eagle-import:0603-CAP")
      (fields (field (name "PARTNO") "CC0603ZRY5V7BB105"))
      (libsource (lib "eagle-import") (part "CAP0603"))
    )
    (comp (ref "C604")
      (value "22u/25V")
      (footprint "eagle-import:0805-CAP")
      (fields (field (name "PARTNO") "CL21A226MAQNNNE"))
      (libsource (lib "eagle-import") (part "CAP0805"))
    )
    (comp (ref "C605")
      (value "22u/25V")
      (footprint "eagle-import:0805-CAP")
      (fields (field (name "PARTNO") "CL21A226MAQNNNE"))
      (libsource (lib "eagle-import") (part "CAP0805"))
    )
    (comp (ref "C606")
      (value "0u1")
      (footprint "eagle-import:0402-CAP")
      (fields (field (name "PARTNO") "CC0402ZRY5V7BB104"))
      (libsource (lib "eagle-import") (part "CAP0402"))
    )
    (comp (ref "C607")
      (value "0u1")
      (footprint "eagle-import:0402-CAP")
      (fields (field (name "PARTNO") "CC0402ZRY5V7BB104"))
      (libsource (lib "eagle-import") (part "CAP0402"))
    )
    (comp (ref "C608")
      (value "0u1")
      (footprint "eagle-import:0402-CAP")
      (fields (field (name "PARTNO") "CC0402ZRY5V7BB104"))
      (libsource (lib "eagle-import") (part "CAP0402"))
    )
    (comp (ref "C609")
      (value "0u1")
      (footprint "eagle-import:0402-CAP")
      (fields (field (name "PARTNO") "CC0402ZRY5V7BB104"))
      (libsource (lib "eagle-import") (part "CAP0402"))
    )
    (comp (ref "C610")
      (value "0u1")
      (footprint "eagle-import:0402-CAP")
      (fields (field (name "PARTNO") "CC0402ZRY5V7BB104"))
      (libsource (lib "eagle-import") (part "CAP0402"))
    )
    (comp (ref "C611")
      (value "2u2")
      (footprint "eagle-import:0603-CAP")
      (fields (field (name "PARTNO") "C1608X6S1C225K080AC"))
      (libsource (lib "eagle-import") (part "CAP0603"))
    )
    (comp (ref "C612")
      (value "0u1")
      (footprint "eagle-import:0402-CAP")
      (fields (field (name "PARTNO") "CC0402ZRY5V7BB104"))
      (libsource (lib "eagle-import") (part "CAP0402"))
    )
    (comp (ref "C613")
      (value "2u2")
      (footprint "eagle-import:0603-CAP")
      (fields (field (name "PARTNO") "C1608X6S1C225K080AC"))
      (libsource (lib "eagle-import") (part "CAP0603"))
    )
    (comp (ref "C614")
      (value "100u")
      (footprint "eagle-import:1206-CAP")
      (fields (field (name "PARTNO") "C3216X5R1A107M160AC"))
      (libsource (lib "eagle-import") (part "CAP1206"))
    )
    (comp (ref "C615")
      (value "0u1")
      (footprint "eagle-import:0402-CAP")
      (fields (field (name "PARTNO") "CC0402ZRY5V7BB104"))
      (libsource (lib "eagle-import") (part "CAP0402"))
    )
    (comp (ref "C616")
      (value "0u1")
      (footprint "eagle-import:0402-CAP")
      (fields (field (name "PARTNO") "CC0402ZRY5V7BB104"))
      (libsource (lib "eagle-import") (part "CAP0402"))
    )
    (comp (ref "C617")
      (value "0u1")
      (footprint "eagle-import:0402-CAP")
      (fields (field (name "PARTNO") "CC0402ZRY5V7BB104"))
      (libsource (lib "eagle-import") (part "CAP0402"))
    )
    (comp (ref "C618")
      (value "100u")
      (footprint "eagle-import:1206-CAP")
      (fields (field (name "PARTNO") "C3216X5R1A107M160AC"))
      (libsource (lib "eagle-import") (part "CAP1206"))
    )
    (comp (ref "D602")
      (value "RB751V40T1G")
      (footprint "eagle-import:SOD323")
      (libsource (lib "eagle-import") (part "DIODE-SCHOTTKY_SOD323"))
    )
    (comp (ref "L603")
      (value "KNH16C104DA5TS")
      (footprint "eagle-import:KYOCERA-KNH16-DA")
      (libsource (lib "eagle-import") (part "KNH16C104DA5TS"))
    )
    (comp (ref "Q601")
      (value "MMBT3906LT1SMD")
      (footprint "eagle-import:SOT23-BEC")
      (fields (field (name "PARTNO") "MMBT 3906 LT1"))
      (libsource (lib "eagle-import") (part "MMBT3906SMDLT1"))
    )
    (comp (ref "R602")
      (value "1M")
      (footprint "eagle-import:0402-RES")
      (fields (field (name "PARTNO") "RC0402FR-071ML"))
      (libsource (lib "eagle-import") (part "RESISTOR0402-RES"))
    )
    (comp (ref "R603")
      (value "10K")
      (footprint "eagle-import:0402-RES")
      (fields (field (name "PARTNO") "RC0402FR-0710KL"))
      (libsource (lib "eagle-import") (part "RESISTOR0402-RES"))
    )
    (comp (ref "R604")
      (value "1M")
      (footprint "eagle-import:0402-RES")
      (fields (field (name "PARTNO") "RC0402FR-071ML"))
      (libsource (lib "eagle-import") (part "RESISTOR0402-RES"))
    )
    (comp (ref "R608")
      (value "1K")
      (footprint "eagle-import:0402-RES")
      (fields (field (name "PARTNO") "RC0402FR-071KL"))
      (libsource (lib "eagle-import") (part "RESISTOR0402-RES"))
    )
    (comp (ref "R609")
      (value "10K/0.1%")
      (footprint "eagle-import:0402-RES")
      (fields (field (name "PARTNO") "ERA-2AEB103X"))
      (libsource (lib "eagle-import") (part "RESISTOR0402-RES"))
    )
    (comp (ref "R610")
      (value "10K/0.1%")
      (footprint "eagle-import:0402-RES")
      (fields (field (name "PARTNO") "ERA-2AEB103X"))
      (libsource (lib "eagle-import") (part "RESISTOR0402-RES"))
    )
    (comp (ref "R611")
      (value "10K")
      (footprint "eagle-import:0402-RES")
      (fields (field (name "PARTNO") "RC0402FR-0710KL"))
      (libsource (lib "eagle-import") (part "RESISTOR0402-RES"))
    )
    (comp (ref "R615")
      (value "10K")
      (footprint "eagle-import:0402-RES")
      (fields (field (name "PARTNO") "RC0402FR-0710KL"))
      (libsource (lib "eagle-import") (part "RESISTOR0402-RES"))
    )
    (comp (ref "R616")
      (value "25K5")
      (footprint "eagle-import:0402-RES")
      (fields (field (name "PARTNO") "RMCF0402FT25K5"))
      (libsource (lib "eagle-import") (part "RESISTOR0402-RES"))
    )
    (comp (ref "R617")
      (value "16K5")
      (footprint "eagle-import:0402-RES")
      (fields (field (name "PARTNO") "RMCF0402FT16K5"))
      (libsource (lib "eagle-import") (part "RESISTOR0402-RES"))
    )
    (comp (ref "R620")
      (value "1K8")
      (footprint "eagle-import:0402-RES")
      (fields (field (name "PARTNO") "RC1005F182CS"))
      (libsource (lib "eagle-import") (part "RESISTOR0402-RES"))
    )
    (comp (ref "R621")
      (value "10R")
      (footprint "eagle-import:0603-RES")
      (fields (field (name "PARTNO") "RC1608J100CS"))
      (libsource (lib "eagle-import") (part "RESISTOR0603-RES"))
    )
    (comp (ref "R635")
      (value "10K")
      (footprint "eagle-import:0402-RES")
      (fields (field (name "PARTNO") "RC0402FR-0710KL"))
      (libsource (lib "eagle-import") (part "RESISTOR0402-RES"))
    )
    (comp (ref "S601")
      (value "RESET")
      (footprint "eagle-import:EVQP7J01K")
      (fields (field (name "PARTNO") "EVQ-P7J01P"))
      (libsource (lib "eagle-import") (part "SWITCH-MOMENTARY-2"))
    )
    (comp (ref "U601")
      (value "BQ24315")
      (footprint "eagle-import:QFN8-DSG")
      (fields (field (name "PARTNO") "BQ24315DSGR"))
      (libsource (lib "eagle-import") (part "BQ24315"))
    )
    (comp (ref "U602")
      (value "BQ24315")
      (footprint "eagle-import:QFN8-DSG")
      (fields (field (name "PARTNO") "BQ24315DSGR"))
      (libsource (lib "eagle-import") (part "BQ24315"))
    )
    (comp (ref "U603")
      (value "MIC5332")
      (footprint "eagle-import:MLF-8-EPAD")
      (fields (field (name "PARTNO") "MIC5332-SSYMT"))
      (libsource (lib "eagle-import") (part "MIC5332"))
    )
  )
  (nets
    (net (code "1") (name "ACCEL_DRDY") (class "Default")
      (node (ref "U101") (pin "90") (pinfunction "PB4_90") (pintype "bidirectional"))
      (node (ref "U504") (pin "11") (pinfunction "INT1_11") (pintype "bidirectional"))
      (node (ref "X503") (pin "3") (pinfunction "S_3") (pintype "passive"))
    )
    (net (code "2") (name "ALARM") (class "Default")
      (node (ref "R701") (pin "P$2") (pinfunction "2_P$2") (pintype "passive"))
      (node (ref "U101") (pin "77") (pinfunction "PA15_77") (pintype "bidirectional"))
    )
    (net (code "3") (name "BATT_CURRENT_SENS") (class "Default")
      (node (ref "R1101") (pin "P$1") (pinfunction "1_P$1") (pintype "passive"))
      (node (ref "U101") (pin "26") (pinfunction "PA3_26") (pintype "bidirectional"))
    )
    (net (code "4") (name "BATT_VOLTAGE_SENS") (class "Default")
      (node (ref "R1102") (pin "P$1") (pinfunction "1_P$1") (pintype "passive"))
      (node (ref "U101") (pin "25") (pinfunction "PA2_25") (pintype "bidirectional"))
    )
    (net (code "5") (name "CAN1_RX") (class "Default")
      (node (ref "U101") (pin "81") (pinfunction "PD0_81") (pintype "bidirectional"))
      (node (ref "U401") (pin "4") (pinfunction "DOUT_4") (pintype "output"))
    )
    (net (code "6") (name "CAN1_TX") (class "Default")
      (node (ref "U101") (pin "82") (pinfunction "PD1_82") (pintype "bidirectional"))
      (node (ref "U401") (pin "1") (pinfunction "DIN_1") (pintype "input"))
    )
    (net (code "7") (name "CAN2_RX") (class "Default")
      (node (ref "R216") (pin "P$1") (pinfunction "1_P$1") (pintype "passive"))
      (node (ref "U101") (pin "51") (pinfunction "PB12_51") (pintype "bidirectional"))
    )
    (net (code "8") (name "CAN2_TX") (class "Default")
      (node (ref "R215") (pin "P$1") (pinfunction "1_P$1") (pintype "passive"))
      (node (ref "U101") (pin "92") (pinfunction "PB6_92") (pintype "bidirectional"))
    )
    (net (code "9") (name "CAN_H") (class "Default")
      (node (ref "CAN_H") (pin "P$1") (pinfunction "P$1_P$1") (pintype "passive"))
      (node (ref "J405") (pin "2") (pinfunction "2_2") (pintype "passive"))
      (node (ref "R409") (pin "P$1") (pinfunction "1_P$1") (pintype "passive"))
      (node (ref "U401") (pin "7") (pinfunction "CANH_7") (pintype "bidirectional"))
    )
    (net (code "10") (name "CAN_L") (class "Default")
      (node (ref "CAN_L") (pin "P$1") (pinfunction "P$1_P$1") (pintype "passive"))
      (node (ref "J405") (pin "3") (pinfunction "3_3") (pintype "passive"))
      (node (ref "R409") (pin "P$2") (pinfunction "2_P$2") (pintype "passive"))
      (node (ref "U401") (pin "6") (pinfunction "CANL_6") (pintype "bidirectional"))
    )
    (net (code "11") (name "FMU-BOOT0") (class "Default")
      (node (ref "FMU-BOOT1101") (pin "P$1") (pinfunction "P$1_P$1") (pintype "passive"))
      (node (ref "R611") (pin "P$2") (pinfunction "2_P$2") (pintype "passive"))
      (node (ref "U101") (pin "94") (pinfunction "BOOT0_94") (pintype "input"))
    )
    (net (code "12") (name "FMU-CH1") (class "Default")
      (node (ref "U101") (pin "45") (pinfunction "PE14_45") (pintype "bidirectional"))
      (node (ref "U901") (pin "7") (pinfunction "A6_7") (pintype "bidirectional"))
    )
    (net (code "13") (name "FMU-CH2") (class "Default")
      (node (ref "U101") (pin "44") (pinfunction "PE13_44") (pintype "bidirectional"))
      (node (ref "U901") (pin "6") (pinfunction "A5_6") (pintype "bidirectional"))
    )
    (net (code "14") (name "FMU-CH3") (class "Default")
      (node (ref "U101") (pin "42") (pinfunction "PE11_42") (pintype "bidirectional"))
      (node (ref "U901") (pin "5") (pinfunction "A4_5") (pintype "bidirectional"))
    )
    (net (code "15") (name "FMU-CH4") (class "Default")
      (node (ref "U101") (pin "40") (pinfunction "PE9_40") (pintype "bidirectional"))
      (node (ref "U901") (pin "4") (pinfunction "A3_4") (pintype "bidirectional"))
    )
    (net (code "16") (name "FMU-CH5") (class "Default")
      (node (ref "U101") (pin "60") (pinfunction "PD13_60") (pintype "bidirectional"))
      (node (ref "U901") (pin "3") (pinfunction "A2_3") (pintype "bidirectional"))
    )
    (net (code "17") (name "FMU-CH6") (class "Default")
      (node (ref "U101") (pin "61") (pinfunction "PD14_61") (pintype "bidirectional"))
      (node (ref "U901") (pin "1") (pinfunction "A1_1") (pintype "bidirectional"))
    )
    (net (code "18") (name "FMU-I2C1_SCL") (class "Default")
      (node (ref "R401") (pin "P$1") (pinfunction "1_P$1") (pintype "passive"))
      (node (ref "R404") (pin "P$1") (pinfunction "1_P$1") (pintype "passive"))
      (node (ref "U101") (pin "95") (pinfunction "PB8_95") (pintype "bidirectional"))
    )
    (net (code "19") (name "FMU-I2C1_SDA") (class "Default")
      (node (ref "R402") (pin "P$1") (pinfunction "1_P$1") (pintype "passive"))
      (node (ref "R405") (pin "P$1") (pinfunction "1_P$1") (pintype "passive"))
      (node (ref "U101") (pin "96") (pinfunction "PB9_96") (pintype "bidirectional"))
    )
    (net (code "20") (name "FMU-I2C2_SCL") (class "Default")
      (node (ref "R306") (pin "P$1") (pinfunction "1_P$1") (pintype "passive"))
      (node (ref "U101") (pin "47") (pinfunction "PB10_47") (pintype "bidirectional"))
      (node (ref "U701") (pin "3") (pinfunction "SCL_3") (pintype "bidirectional"))
    )
    (net (code "21") (name "FMU-I2C2_SDA") (class "Default")
      (node (ref "R307") (pin "P$1") (pinfunction "1_P$1") (pintype "passive"))
      (node (ref "U101") (pin "48") (pinfunction "PB11_48") (pintype "bidirectional"))
      (node (ref "U701") (pin "2") (pinfunction "SDA_2") (pintype "bidirectional"))
    )
    (net (code "22") (name "FMU-SWCLK") (class "Default")
      (node (ref "JX301") (pin "4") (pinfunction "S_4") (pintype "passive"))
      (node (ref "U101") (pin "76") (pinfunction "PA14_76") (pintype "bidirectional"))
    )
    (net (code "23") (name "FMU-SWDIO") (class "Default")
      (node (ref "JX301") (pin "2") (pinfunction "S_2") (pintype "passive"))
      (node (ref "U101") (pin "72") (pinfunction "PA13_72") (pintype "bidirectional"))
    )
    (net (code "24") (name "FMU-SWO") (class "Default")
      (node (ref "JX301") (pin "6") (pinfunction "S_6") (pintype "passive"))
      (node (ref "U101") (pin "89") (pinfunction "PB3_89") (pintype "bidirectional"))
    )
    (net (code "25") (name "FMU-UART4_RX") (class "Default")
      (node (ref "U101") (pin "24") (pinfunction "PA1_24") (pintype "bidirectional"))
      (node (ref "U202") (pin "8") (pinfunction "A7_8") (pintype "bidirectional"))
    )
    (net (code "26") (name "FMU-UART4_TX") (class "Default")
      (node (ref "U101") (pin "23") (pinfunction "PA0_23") (pintype "bidirectional"))
      (node (ref "U202") (pin "9") (pinfunction "A8_9") (pintype "bidirectional"))
    )
    (net (code "27") (name "FMU-UART7_RX") (class "Default")
      (node (ref "U101") (pin "38") (pinfunction "PE7_38") (pintype "bidirectional"))
      (node (ref "U202") (pin "4") (pinfunction "A3_4") (pintype "bidirectional"))
    )
    (net (code "28") (name "FMU-UART7_TX") (class "Default")
      (node (ref "U101") (pin "39") (pinfunction "PE8_39") (pintype "bidirectional"))
      (node (ref "U202") (pin "5") (pinfunction "A4_5") (pintype "bidirectional"))
    )
    (net (code "29") (name "FMU-UART8_RX") (class "Default")
      (node (ref "U101") (pin "97") (pinfunction "PE0_97") (pintype "bidirectional"))
      (node (ref "U202") (pin "6") (pinfunction "A5_6") (pintype "bidirectional"))
    )
    (net (code "30") (name "FMU-UART8_TX") (class "Default")
      (node (ref "U101") (pin "98") (pinfunction "PE1_98") (pintype "bidirectional"))
      (node (ref "U202") (pin "7") (pinfunction "A6_7") (pintype "bidirectional"))
    )
    (net (code "31") (name "FMU-USART2_CTS") (class "Default")
      (node (ref "U101") (pin "84") (pinfunction "PD3_84") (pintype "bidirectional"))
      (node (ref "U201") (pin "9") (pinfunction "A8_9") (pintype "bidirectional"))
    )
    (net (code "32") (name "FMU-USART2_RTS") (class "Default")
      (node (ref "U101") (pin "85") (pinfunction "PD4_85") (pintype "bidirectional"))
      (node (ref "U201") (pin "8") (pinfunction "A7_8") (pintype "bidirectional"))
    )
    (net (code "33") (name "FMU-USART2_RX") (class "Default")
      (node (ref "U101") (pin "87") (pinfunction "PD6_87") (pintype "bidirectional"))
      (node (ref "U201") (pin "6") (pinfunction "A5_6") (pintype "bidirectional"))
    )
    (net (code "34") (name "FMU-USART2_TX") (class "Default")
      (node (ref "U101") (pin "86") (pinfunction "PD5_86") (pintype "bidirectional"))
      (node (ref "U201") (pin "7") (pinfunction "A6_7") (pintype "bidirectional"))
    )
    (net (code "35") (name "FMU-USART3_CTS") (class "Default")
      (node (ref "U101") (pin "58") (pinfunction "PD11_58") (pintype "bidirectional"))
      (node (ref "U201") (pin "3") (pinfunction "A2_3") (pintype "bidirectional"))
    )
    (net (code "36") (name "FMU-USART3_RTS") (class "Default")
      (node (ref "U101") (pin "59") (pinfunction "PD12_59") (pintype "bidirectional"))
      (node (ref "U201") (pin "1") (pinfunction "A1_1") (pintype "bidirectional"))
    )
    (net (code "37") (name "FMU-USART3_RX") (class "Default")
      (node (ref "U101") (pin "56") (pinfunction "PD9_56") (pintype "bidirectional"))
      (node (ref "U201") (pin "4") (pinfunction "A3_4") (pintype "bidirectional"))
    )
    (net (code "38") (name "FMU-USART3_TX") (class "Default")
      (node (ref "U101") (pin "55") (pinfunction "PD8_55") (pintype "bidirectional"))
      (node (ref "U201") (pin "5") (pinfunction "A4_5") (pintype "bidirectional"))
    )
    (net (code "39") (name "FMU-VDD_3V3") (class "Default")
      (node (ref "C101") (pin "P$1") (pinfunction "1_P$1") (pintype "passive"))
      (node (ref "C201") (pin "P$1") (pinfunction "1_P$1") (pintype "passive"))
      (node (ref "C202") (pin "P$1") (pinfunction "1_P$1") (pintype "passive"))
      (node (ref "C402") (pin "P$1") (pinfunction "1_P$1") (pintype "passive"))
      (node (ref "C603") (pin "P$1") (pinfunction "1_P$1") (pintype "passive"))
      (node (ref "C604") (pin "P$1") (pinfunction "1_P$1") (pintype "passive"))
      (node (ref "C606") (pin "P$1") (pinfunction "1_P$1") (pintype "passive"))
      (node (ref "C607") (pin "P$1") (pinfunction "1_P$1") (pintype "passive"))
      (node (ref "C608") (pin "P$1") (pinfunction "1_P$1") (pintype "passive"))
      (node (ref "C610") (pin "P$1") (pinfunction "1_P$1") (pintype "passive"))
      (node (ref "C612") (pin "P$1") (pinfunction "1_P$1") (pintype "passive"))
      (node (ref "C616") (pin "P$1") (pinfunction "1_P$1") (pintype "passive"))
      (node (ref "C701") (pin "P$1") (pinfunction "1_P$1") (pintype "passive"))
      (node (ref "C902") (pin "P$1") (pinfunction "1_P$1") (pintype "passive"))
      (node (ref "D602") (pin "A") (pinfunction "A_A") (pintype "passive"))
      (node (ref "JX301") (pin "1") (pinfunction "S_1") (pintype "passive"))
      (node (ref "R301") (pin "P$2") (pinfunction "2_P$2") (pintype "passive"))
      (node (ref "R302") (pin "P$2") (pinfunction "2_P$2") (pintype "passive"))
      (node (ref "R303") (pin "P$2") (pinfunction "2_P$2") (pintype "passive"))
      (node (ref "R304") (pin "P$2") (pinfunction "2_P$2") (pintype "passive"))
      (node (ref "R305") (pin "P$2") (pinfunction "2_P$2") (pintype "passive"))
      (node (ref "R306") (pin "P$2") (pinfunction "2_P$2") (pintype "passive"))
      (node (ref "R307") (pin "P$2") (pinfunction "2_P$2") (pintype "passive"))
      (node (ref "R401") (pin "P$2") (pinfunction "2_P$2") (pintype "passive"))
      (node (ref "R402") (pin "P$2") (pinfunction "2_P$2") (pintype "passive"))
      (node (ref "R602") (pin "P$2") (pinfunction "2_P$2") (pintype "passive"))
      (node (ref "R604") (pin "P$2") (pinfunction "2_P$2") (pintype "passive"))
      (node (ref "U101") (pin "100") (pinfunction "VDD_100") (pintype "power_in"))
      (node (ref "U101") (pin "11") (pinfunction "VDD_11") (pintype "power_in"))
      (node (ref "U101") (pin "19") (pinfunction "VDD_19") (pintype "power_in"))
      (node (ref "U101") (pin "21") (pinfunction "VREF+_21") (pintype "input"))
      (node (ref "U101") (pin "22") (pinfunction "VDDA_22") (pintype "power_in"))
      (node (ref "U101") (pin "28") (pinfunction "VDD_28") (pintype "power_in"))
      (node (ref "U101") (pin "50") (pinfunction "VDD_50") (pintype "power_in"))
      (node (ref "U101") (pin "75") (pinfunction "VDD_75") (pintype "power_in"))
      (node (ref "U102") (pin "3") (pinfunction "~{W}_3") (pintype "bidirectional"))
      (node (ref "U102") (pin "7") (pinfunction "~{HOLD}_7") (pintype "bidirectional"))
      (node (ref "U102") (pin "8") (pinfunction "VDD_8") (pintype "bidirectional"))
      (node (ref "U201") (pin "10") (pinfunction "OE_10") (pintype "input"))
      (node (ref "U201") (pin "19") (pinfunction "VCCB_19") (pintype "input"))
      (node (ref "U201") (pin "2") (pinfunction "VCCA_2") (pintype "input"))
      (node (ref "U202") (pin "10") (pinfunction "OE_10") (pintype "input"))
      (node (ref "U202") (pin "19") (pinfunction "VCCB_19") (pintype "input"))
      (node (ref "U202") (pin "2") (pinfunction "VCCA_2") (pintype "input"))
      (node (ref "U301") (pin "4") (pinfunction "VCC_4") (pintype "passive"))
      (node (ref "U401") (pin "3") (pinfunction "VCC_3") (pintype "input"))
      (node (ref "U603") (pin "7") (pinfunction "VOUT2_7") (pintype "bidirectional"))
      (node (ref "U701") (pin "1") (pinfunction "~{SHDN}_1") (pintype "input"))
      (node (ref "U701") (pin "10") (pinfunction "VIN_10") (pintype "power_in"))
      (node (ref "U901") (pin "10") (pinfunction "OE_10") (pintype "input"))
      (node (ref "U901") (pin "19") (pinfunction "VCCB_19") (pintype "input"))
      (node (ref "U901") (pin "2") (pinfunction "VCCA_2") (pintype "input"))
      (node (ref "VDD_3V1101") (pin "P$1") (pinfunction "P$1_P$1") (pintype "passive"))
    )
    (net (code "40") (name "FMU-~{RESET}") (class "Default")
      (node (ref "C609") (pin "P$2") (pinfunction "2_P$2") (pintype "passive"))
      (node (ref "R635") (pin "P$1") (pinfunction "1_P$1") (pintype "passive"))
      (node (ref "S601") (pin "A1") (pinfunction "1_A1") (pintype "passive"))
      (node (ref "U101") (pin "14") (pinfunction "NRST_14") (pintype "input"))
      (node (ref "U603") (pin "3") (pinfunction "POR2_3") (pintype "bidirectional"))
      (node (ref "U701") (pin "4") (pinfunction "~{RESET}_4") (pintype "input"))
    )
    (net (code "41") (name "FMU_AUX_ADC1") (class "Default")
      (node (ref "R408") (pin "P$1") (pinfunction "1_P$1") (pintype "passive"))
      (node (ref "U101") (pin "18") (pinfunction "PC3_18") (pintype "bidirectional"))
    )
    (net (code "42") (name "FMU_AUX_ADC2") (class "Default")
      (node (ref "R407") (pin "P$1") (pinfunction "1_P$1") (pintype "passive"))
      (node (ref "U101") (pin "33") (pinfunction "PC4_33") (pintype "bidirectional"))
    )
    (net (code "43") (name "FRAM_MISO") (class "Default")
      (node (ref "U101") (pin "53") (pinfunction "PB14_53") (pintype "bidirectional"))
      (node (ref "U102") (pin "2") (pinfunction "Q_2") (pintype "bidirectional"))
    )
    (net (code "44") (name "FRAM_MOSI") (class "Default")
      (node (ref "U101") (pin "54") (pinfunction "PB15_54") (pintype "bidirectional"))
      (node (ref "U102") (pin "5") (pinfunction "D_5") (pintype "bidirectional"))
    )
    (net (code "45") (name "FRAM_SCK") (class "Default")
      (node (ref "U101") (pin "52") (pinfunction "PB13_52") (pintype "bidirectional"))
      (node (ref "U102") (pin "6") (pinfunction "C_6") (pintype "bidirectional"))
    )
    (net (code "46") (name "GND") (class "Default")
      (node (ref "B601") (pin "2") (pinfunction "NEG_2") (pintype "bidirectional"))
      (node (ref "C1001") (pin "P$2") (pinfunction "2_P$2") (pintype "passive"))
      (node (ref "C1002") (pin "P$2") (pinfunction "2_P$2") (pintype "passive"))
      (node (ref "C1003") (pin "P$2") (pinfunction "2_P$2") (pintype "passive"))
      (node (ref "C1004") (pin "P$2") (pinfunction "2_P$2") (pintype "passive"))
      (node (ref "C1005") (pin "P$2") (pinfunction "2_P$2") (pintype "passive"))
      (node (ref "C1008") (pin "P$2") (pinfunction "2_P$2") (pintype "passive"))
      (node (ref "C101") (pin "P$2") (pinfunction "2_P$2") (pintype "passive"))
      (node (ref "C102") (pin "P$2") (pinfunction "2_P$2") (pintype "passive"))
      (node (ref "C103") (pin "P$1") (pinfunction "1_P$1") (pintype "passive"))
      (node (ref "C1101") (pin "P$2") (pinfunction "2_P$2") (pintype "passive"))
      (node (ref "C1102") (pin "P$2") (pinfunction "2_P$2") (pintype "passive"))
      (node (ref "C1103") (pin "P$2") (pinfunction "2_P$2") (pintype "passive"))
      (node (ref "C1104") (pin "P$2") (pinfunction "2_P$2") (pintype "passive"))
      (node (ref "C1105") (pin "P$2") (pinfunction "2_P$2") (pintype "passive"))
      (node (ref "C1106") (pin "P$2") (pinfunction "2_P$2") (pintype "passive"))
      (node (ref "C1107") (pin "P$2") (pinfunction "2_P$2") (pintype "passive"))
      (node (ref "C1108") (pin "P$2") (pinfunction "2_P$2") (pintype "passive"))
      (node (ref "C1109") (pin "P$2") (pinfunction "2_P$2") (pintype "passive"))
      (node (ref "C1110") (pin "P$2") (pinfunction "2_P$2") (pintype "passive"))
      (node (ref "C201") (pin "P$2") (pinfunction "2_P$2") (pintype "passive"))
      (node (ref "C202") (pin "P$2") (pinfunction "2_P$2") (pintype "passive"))
      (node (ref "C401") (pin "P$2") (pinfunction "2_P$2") (pintype "passive"))
      (node (ref "C402") (pin "P$2") (pinfunction "2_P$2") (pintype "passive"))
      (node (ref "C501") (pin "P$2") (pinfunction "2_P$2") (pintype "passive"))
      (node (ref "C502") (pin "P$2") (pinfunction "2_P$2") (pintype "passive"))
      (node (ref "C503") (pin "P$2") (pinfunction "2_P$2") (pintype "passive"))
      (node (ref "C504") (pin "P$2") (pinfunction "2_P$2") (pintype "passive"))
      (node (ref "C505") (pin "P$2") (pinfunction "2_P$2") (pintype "passive"))
      (node (ref "C506") (pin "P$2") (pinfunction "2_P$2") (pintype "passive"))
      (node (ref "C507") (pin "P$2") (pinfunction "2_P$2") (pintype "passive"))
      (node (ref "C508") (pin "P$2") (pinfunction "2_P$2") (pintype "passive"))
      (node (ref "C509") (pin "P$2") (pinfunction "2_P$2") (pintype "passive"))
      (node (ref "C511") (pin "P$2") (pinfunction "2_P$2") (pintype "passive"))
      (node (ref "C512") (pin "P$2") (pinfunction "2_P$2") (pintype "passive"))
      (node (ref "C513") (pin "P$2") (pinfunction "2_P$2") (pintype "passive"))
      (node (ref "C514") (pin "P$2") (pinfunction "2_P$2") (pintype "passive"))
      (node (ref "C515") (pin "P$2") (pinfunction "2_P$2") (pintype "passive"))
      (node (ref "C601") (pin "P$2") (pinfunction "2_P$2") (pintype "passive"))
      (node (ref "C602") (pin "P$1") (pinfunction "1_P$1") (pintype "passive"))
      (node (ref "C603") (pin "P$2") (pinfunction "2_P$2") (pintype "passive"))
      (node (ref "C604") (pin "P$2") (pinfunction "2_P$2") (pintype "passive"))
      (node (ref "C605") (pin "P$2") (pinfunction "2_P$2") (pintype "passive"))
      (node (ref "C606") (pin "P$2") (pinfunction "2_P$2") (pintype "passive"))
      (node (ref "C607") (pin "P$2") (pinfunction "2_P$2") (pintype "passive"))
      (node (ref "C608") (pin "P$2") (pinfunction "2_P$2") (pintype "passive"))
      (node (ref "C609") (pin "P$1") (pinfunction "1_P$1") (pintype "passive"))
      (node (ref "C610") (pin "P$2") (pinfunction "2_P$2") (pintype "passive"))
      (node (ref "C611") (pin "P$2") (pinfunction "2_P$2") (pintype "passive"))
      (node (ref "C612") (pin "P$2") (pinfunction "2_P$2") (pintype "passive"))
      (node (ref "C613") (pin "P$2") (pinfunction "2_P$2") (pintype "passive"))
      (node (ref "C614") (pin "P$2") (pinfunction "2_P$2") (pintype "passive"))
      (node (ref "C615") (pin "P$2") (pinfunction "2_P$2") (pintype "passive"))
      (node (ref "C616") (pin "P$2") (pinfunction "2_P$2") (pintype "passive"))
      (node (ref "C617") (pin "P$2") (pinfunction "2_P$2") (pintype "passive"))
      (node (ref "C618") (pin "P$2") (pinfunction "2_P$2") (pintype "passive"))
      (node (ref "C701") (pin "P$2") (pinfunction "2_P$2") (pintype "passive"))
      (node (ref "C702") (pin "P$2") (pinfunction "2_P$2") (pintype "passive"))
      (node (ref "C703") (pin "P$2") (pinfunction "2_P$2") (pintype "passive"))
      (node (ref "C704") (pin "P$2") (pinfunction "2_P$2") (pintype "passive"))
      (node (ref "C801") (pin "P$1") (pinfunction "1_P$1") (pintype "passive"))
      (node (ref "C802") (pin "P$2") (pinfunction "2_P$2") (pintype "passive"))
      (node (ref "C803") (pin "P$2") (pinfunction "2_P$2") (pintype "passive"))
      (node (ref "C804") (pin "P$2") (pinfunction "2_P$2") (pintype "passive"))
      (node (ref "C805") (pin "P$2") (pinfunction "2_P$2") (pintype "passive"))
      (node (ref "C806") (pin "P$1") (pinfunction "1_P$1") (pintype "passive"))
      (node (ref "C901") (pin "P$2") (pinfunction "2_P$2") (pintype "passive"))
      (node (ref "C902") (pin "P$2") (pinfunction "2_P$2") (pintype "passive"))
      (node (ref "C903") (pin "P$2") (pinfunction "2_P$2") (pintype "passive"))
      (node (ref "D201") (pin "A") (pinfunction "A_A") (pintype "passive"))
      (node (ref "D202") (pin "A") (pinfunction "A_A") (pintype "passive"))
      (node (ref "D203") (pin "A") (pinfunction "A_A") (pintype "passive"))
      (node (ref "D401") (pin "A") (pinfunction "A_A") (pintype "passive"))
      (node (ref "D402") (pin "A") (pinfunction "A_A") (pintype "passive"))
      (node (ref "D403") (pin "A") (pinfunction "A_A") (pintype "passive"))
      (node (ref "D404") (pin "A") (pinfunction "A_A") (pintype "passive"))
      (node (ref "D701") (pin "A") (pinfunction "A_A") (pintype "passive"))
      (node (ref "D801") (pin "A") (pinfunction "A_A") (pintype "passive"))
      (node (ref "D901") (pin "A") (pinfunction "A_A") (pintype "passive"))
      (node (ref "D902") (pin "A") (pinfunction "A_A") (pintype "passive"))
      (node (ref "D903") (pin "A") (pinfunction "A_A") (pintype "passive"))
      (node (ref "GND") (pin "P$1") (pinfunction "P$1_P$1") (pintype "passive"))
      (node (ref "GND.") (pin "P$1") (pinfunction "P$1_P$1") (pintype "passive"))
      (node (ref "J201") (pin "6") (pinfunction "6_6") (pintype "passive"))
      (node (ref "J202") (pin "6") (pinfunction "6_6") (pintype "passive"))
      (node (ref "J203") (pin "6") (pinfunction "6_6") (pintype "passive"))
      (node (ref "J204") (pin "6") (pinfunction "6_6") (pintype "passive"))
      (node (ref "J301") (pin "GND") (pinfunction "5_GND") (pintype "power_in"))
      (node (ref "J301") (pin "GND1") (pinfunction "GND1_GND1") (pintype "bidirectional"))
      (node (ref "J301") (pin "GND2") (pinfunction "GND2_GND2") (pintype "bidirectional"))
      (node (ref "J301") (pin "GND3") (pinfunction "GND3_GND3") (pintype "bidirectional"))
      (node (ref "J301") (pin "GND4") (pinfunction "GND4_GND4") (pintype "bidirectional"))
      (node (ref "J302") (pin "4") (pinfunction "4_4") (pintype "passive"))
      (node (ref "J401") (pin "4") (pinfunction "4_4") (pintype "passive"))
      (node (ref "J402") (pin "3") (pinfunction "3_3") (pintype "passive"))
      (node (ref "J403") (pin "7") (pinfunction "7_7") (pintype "passive"))
      (node (ref "J404") (pin "3") (pinfunction "3_3") (pintype "passive"))
      (node (ref "J404") (pin "5") (pinfunction "5_5") (pintype "passive"))
      (node (ref "J405") (pin "4") (pinfunction "4_4") (pintype "passive"))
      (node (ref "J601") (pin "5") (pinfunction "5_5") (pintype "passive"))
      (node (ref "J601") (pin "6") (pinfunction "6_6") (pintype "passive"))
      (node (ref "J701") (pin "2") (pinfunction "2_2") (pintype "passive"))
      (node (ref "J801") (pin "P$2") (pinfunction "P$2_P$2") (pintype "bidirectional"))
      (node (ref "J901") (pin "12") (pinfunction "S_12") (pintype "passive"))
      (node (ref "J901") (pin "15") (pinfunction "S_15") (pintype "passive"))
      (node (ref "J901") (pin "18") (pinfunction "S_18") (pintype "passive"))
      (node (ref "J901") (pin "21") (pinfunction "S_21") (pintype "passive"))
      (node (ref "J901") (pin "24") (pinfunction "S_24") (pintype "passive"))
      (node (ref "J901") (pin "27") (pinfunction "S_27") (pintype "passive"))
      (node (ref "J901") (pin "3") (pinfunction "S_3") (pintype "passive"))
      (node (ref "J901") (pin "30") (pinfunction "S_30") (pintype "passive"))
      (node (ref "J901") (pin "33") (pinfunction "S_33") (pintype "passive"))
      (node (ref "J901") (pin "36") (pinfunction "S_36") (pintype "passive"))
      (node (ref "J901") (pin "39") (pinfunction "S_39") (pintype "passive"))
      (node (ref "J901") (pin "42") (pinfunction "S_42") (pintype "passive"))
      (node (ref "J901") (pin "45") (pinfunction "S_45") (pintype "passive"))
      (node (ref "J901") (pin "48") (pinfunction "S_48") (pintype "passive"))
      (node (ref "J901") (pin "6") (pinfunction "S_6") (pintype "passive"))
      (node (ref "J901") (pin "9") (pinfunction "S_9") (pintype "passive"))
      (node (ref "JX301") (pin "3") (pinfunction "S_3") (pintype "passive"))
      (node (ref "JX301") (pin "5") (pinfunction "S_5") (pintype "passive"))
      (node (ref "JX301") (pin "9") (pinfunction "S_9") (pintype "passive"))
      (node (ref "JX801") (pin "3") (pinfunction "GND_3") (pintype "bidirectional"))
      (node (ref "JX802") (pin "3") (pinfunction "S_3") (pintype "passive"))
      (node (ref "JX802") (pin "5") (pinfunction "S_5") (pintype "passive"))
      (node (ref "JX802") (pin "9") (pinfunction "S_9") (pintype "passive"))
      (node (ref "L1101") (pin "P$3") (pinfunction "P$3_P$3") (pintype "bidirectional"))
      (node (ref "L1101") (pin "P$4") (pinfunction "P$3_P$4") (pintype "bidirectional"))
      (node (ref "L1101") (pin "P$5") (pinfunction "P$3_P$5") (pintype "bidirectional"))
      (node (ref "L1102") (pin "P$3") (pinfunction "P$3_P$3") (pintype "bidirectional"))
      (node (ref "L1102") (pin "P$4") (pinfunction "P$3_P$4") (pintype "bidirectional"))
      (node (ref "L1102") (pin "P$5") (pinfunction "P$3_P$5") (pintype "bidirectional"))
      (node (ref "L201") (pin "P$3") (pinfunction "P$3_P$3") (pintype "bidirectional"))
      (node (ref "L201") (pin "P$4") (pinfunction "P$3_P$4") (pintype "bidirectional"))
      (node (ref "L201") (pin "P$5") (pinfunction "P$3_P$5") (pintype "bidirectional"))
      (node (ref "L202") (pin "P$3") (pinfunction "P$3_P$3") (pintype "bidirectional"))
      (node (ref "L202") (pin "P$4") (pinfunction "P$3_P$4") (pintype "bidirectional"))
      (node (ref "L202") (pin "P$5") (pinfunction "P$3_P$5") (pintype "bidirectional"))
      (node (ref "L203") (pin "P$3") (pinfunction "P$3_P$3") (pintype "bidirectional"))
      (node (ref "L203") (pin "P$4") (pinfunction "P$3_P$4") (pintype "bidirectional"))
      (node (ref "L203") (pin "P$5") (pinfunction "P$3_P$5") (pintype "bidirectional"))
      (node (ref "L401") (pin "P$3") (pinfunction "P$3_P$3") (pintype "bidirectional"))
      (node (ref "L401") (pin "P$4") (pinfunction "P$3_P$4") (pintype "bidirectional"))
      (node (ref "L401") (pin "P$5") (pinfunction "P$3_P$5") (pintype "bidirectional"))
      (node (ref "L402") (pin "P$3") (pinfunction "P$3_P$3") (pintype "bidirectional"))
      (node (ref "L402") (pin "P$4") (pinfunction "P$3_P$4") (pintype "bidirectional"))
      (node (ref "L402") (pin "P$5") (pinfunction "P$3_P$5") (pintype "bidirectional"))
      (node (ref "L403") (pin "P$3") (pinfunction "P$3_P$3") (pintype "bidirectional"))
      (node (ref "L403") (pin "P$4") (pinfunction "P$3_P$4") (pintype "bidirectional"))
      (node (ref "L403") (pin "P$5") (pinfunction "P$3_P$5") (pintype "bidirectional"))
      (node (ref "L404") (pin "P$3") (pinfunction "P$3_P$3") (pintype "bidirectional"))
      (node (ref "L404") (pin "P$4") (pinfunction "P$3_P$4") (pintype "bidirectional"))
      (node (ref "L404") (pin "P$5") (pinfunction "P$3_P$5") (pintype "bidirectional"))
      (node (ref "L603") (pin "P$3") (pinfunction "P$3_P$3") (pintype "bidirectional"))
      (node (ref "L603") (pin "P$4") (pinfunction "P$3_P$4") (pintype "bidirectional"))
      (node (ref "L603") (pin "P$5") (pinfunction "P$3_P$5") (pintype "bidirectional"))
      (node (ref "L901") (pin "P$3") (pinfunction "P$3_P$3") (pintype "bidirectional"))
      (node (ref "L901") (pin "P$4") (pinfunction "P$3_P$4") (pintype "bidirectional"))
      (node (ref "L901") (pin "P$5") (pinfunction "P$3_P$5") (pintype "bidirectional"))
      (node (ref "R1001") (pin "P$1") (pinfunction "1_P$1") (pintype "passive"))
      (node (ref "R1002") (pin "P$1") (pinfunction "1_P$1") (pintype "passive"))
      (node (ref "R102") (pin "P$2") (pinfunction "2_P$2") (pintype "passive"))
      (node (ref "R1103") (pin "P$2") (pinfunction "2_P$2") (pintype "passive"))
      (node (ref "R1104") (pin "P$2") (pinfunction "2_P$2") (pintype "passive"))
      (node (ref "R1107") (pin "P$2") (pinfunction "2_P$2") (pintype "passive"))
      (node (ref "R1111") (pin "P$2") (pinfunction "2_P$2") (pintype "passive"))
      (node (ref "R1114") (pin "P$2") (pinfunction "2_P$2") (pintype "passive"))
      (node (ref "R1115") (pin "P$1") (pinfunction "1_P$1") (pintype "passive"))
      (node (ref "R403") (pin "P$1") (pinfunction "1_P$1") (pintype "passive"))
      (node (ref "R610") (pin "P$2") (pinfunction "2_P$2") (pintype "passive"))
      (node (ref "R611") (pin "P$1") (pinfunction "1_P$1") (pintype "passive"))
      (node (ref "R615") (pin "P$2") (pinfunction "2_P$2") (pintype "passive"))
      (node (ref "R616") (pin "P$2") (pinfunction "2_P$2") (pintype "passive"))
      (node (ref "R617") (pin "P$2") (pinfunction "2_P$2") (pintype "passive"))
      (node (ref "R621") (pin "1") (pinfunction "1_1") (pintype "passive"))
      (node (ref "R702") (pin "P$2") (pinfunction "2_P$2") (pintype "passive"))
      (node (ref "R704") (pin "P$1") (pinfunction "1_P$1") (pintype "passive"))
      (node (ref "R706") (pin "P$2") (pinfunction "2_P$2") (pintype "passive"))
      (node (ref "R708") (pin "P$1") (pinfunction "1_P$1") (pintype "passive"))
      (node (ref "R711") (pin "P$1") (pinfunction "1_P$1") (pintype "passive"))
      (node (ref "R713") (pin "P$2") (pinfunction "2_P$2") (pintype "passive"))
      (node (ref "R801") (pin "P$2") (pinfunction "2_P$2") (pintype "passive"))
      (node (ref "R802") (pin "P$2") (pinfunction "2_P$2") (pintype "passive"))
      (node (ref "R919") (pin "P$1") (pinfunction "1_P$1") (pintype "passive"))
      (node (ref "S601") (pin "B3") (pinfunction "2_B3") (pintype "passive"))
      (node (ref "S801") (pin "B3") (pinfunction "2_B3") (pintype "passive"))
      (node (ref "U1001") (pin "2") (pinfunction "VSS_2") (pintype "bidirectional"))
      (node (ref "U1001") (pin "5") (pinfunction "~{CE}_5") (pintype "bidirectional"))
      (node (ref "U1001") (pin "6") (pinfunction "VBAT_6") (pintype "bidirectional"))
      (node (ref "U1001") (pin "GND") (pinfunction "VSS_GND") (pintype "bidirectional"))
      (node (ref "U1001") (pin "P$2") (pinfunction "VSS_P$2") (pintype "bidirectional"))
      (node (ref "U1001") (pin "P$3") (pinfunction "VSS_P$3") (pintype "bidirectional"))
      (node (ref "U1002") (pin "2") (pinfunction "GND_2") (pintype "bidirectional"))
      (node (ref "U1002") (pin "GND") (pinfunction "GND_GND") (pintype "bidirectional"))
      (node (ref "U101") (pin "10") (pinfunction "VSS_10") (pintype "power_in"))
      (node (ref "U101") (pin "20") (pinfunction "VSSA_20") (pintype "power_in"))
      (node (ref "U101") (pin "27") (pinfunction "VSS_27") (pintype "power_in"))
      (node (ref "U101") (pin "74") (pinfunction "VSS_74") (pintype "power_in"))
      (node (ref "U101") (pin "99") (pinfunction "VSS_99") (pintype "power_in"))
      (node (ref "U102") (pin "4") (pinfunction "VSS_4") (pintype "bidirectional"))
      (node (ref "U1101") (pin "P$10") (pinfunction "GND_P$10") (pintype "bidirectional"))
      (node (ref "U1101") (pin "P$25") (pinfunction "GND_P$25") (pintype "bidirectional"))
      (node (ref "U201") (pin "11") (pinfunction "GND_11") (pintype "power_in"))
      (node (ref "U202") (pin "11") (pinfunction "GND_11") (pintype "power_in"))
      (node (ref "U301") (pin "6") (pinfunction "GND_6") (pintype "power_in"))
      (node (ref "U302") (pin "2") (pinfunction "GND_2") (pintype "bidirectional"))
      (node (ref "U401") (pin "2") (pinfunction "GND_2") (pintype "power_in"))
      (node (ref "U401") (pin "5") (pinfunction "SHDN_5") (pintype "input"))
      (node (ref "U401") (pin "8") (pinfunction "RS_8") (pintype "input"))
      (node (ref "U501") (pin "10") (pinfunction "RES_P10_GND_10") (pintype "bidirectional"))
      (node (ref "U501") (pin "11") (pinfunction "RES_P11_GND_11") (pintype "bidirectional"))
      (node (ref "U501") (pin "12") (pinfunction "RES_P12_GND_12") (pintype "bidirectional"))
      (node (ref "U501") (pin "13") (pinfunction "GND_13") (pintype "bidirectional"))
      (node (ref "U501") (pin "8") (pinfunction "RES_P8_GND_8") (pintype "bidirectional"))
      (node (ref "U501") (pin "9") (pinfunction "RES_P9_GND_9") (pintype "bidirectional"))
      (node (ref "U502") (pin "10") (pinfunction "GND_10") (pintype "bidirectional"))
      (node (ref "U502") (pin "11") (pinfunction "GND_11") (pintype "bidirectional"))
      (node (ref "U502") (pin "12") (pinfunction "GND_12") (pintype "bidirectional"))
      (node (ref "U502") (pin "13") (pinfunction "GND_13") (pintype "bidirectional"))
      (node (ref "U502") (pin "9") (pinfunction "GND_9") (pintype "bidirectional"))
      (node (ref "U504") (pin "10") (pinfunction "RSRV_10") (pintype "bidirectional"))
      (node (ref "U504") (pin "12") (pinfunction "GND_12") (pintype "bidirectional"))
      (node (ref "U504") (pin "13") (pinfunction "GND_13") (pintype "bidirectional"))
      (node (ref "U504") (pin "16") (pinfunction "GND_16") (pintype "bidirectional"))
      (node (ref "U504") (pin "5") (pinfunction "GND_5") (pintype "bidirectional"))
      (node (ref "U505") (pin "1") (pinfunction "CLKIN_1") (pintype "bidirectional"))
      (node (ref "U505") (pin "18") (pinfunction "GND_18") (pintype "bidirectional"))
      (node (ref "U506") (pin "2") (pinfunction "PS_2") (pintype "bidirectional"))
      (node (ref "U506") (pin "3") (pinfunction "GND_3") (pintype "bidirectional"))
      (node (ref "U601") (pin "2") (pinfunction "VSS_2") (pintype "bidirectional"))
      (node (ref "U601") (pin "6") (pinfunction "VBAT_6") (pintype "bidirectional"))
      (node (ref "U601") (pin "GND") (pinfunction "VSS_GND") (pintype "bidirectional"))
      (node (ref "U601") (pin "P$2") (pinfunction "VSS_P$2") (pintype "bidirectional"))
      (node (ref "U601") (pin "P$3") (pinfunction "VSS_P$3") (pintype "bidirectional"))
      (node (ref "U602") (pin "2") (pinfunction "VSS_2") (pintype "bidirectional"))
      (node (ref "U602") (pin "6") (pinfunction "VBAT_6") (pintype "bidirectional"))
      (node (ref "U602") (pin "GND") (pinfunction "VSS_GND") (pintype "bidirectional"))
      (node (ref "U602") (pin "P$2") (pinfunction "VSS_P$2") (pintype "bidirectional"))
      (node (ref "U602") (pin "P$3") (pinfunction "VSS_P$3") (pintype "bidirectional"))
      (node (ref "U603") (pin "2") (pinfunction "GND_2") (pintype "bidirectional"))
      (node (ref "U603") (pin "GND") (pinfunction "GND_GND") (pintype "bidirectional"))
      (node (ref "U701") (pin "5") (pinfunction "GND_5") (pintype "power_in"))
      (node (ref "U702") (pin "4") (pinfunction "GND_4") (pintype "power_in"))
      (node (ref "U801") (pin "23") (pinfunction "VSS_1_23") (pintype "power_in"))
      (node (ref "U801") (pin "35") (pinfunction "VSS_2_35") (pintype "power_in"))
      (node (ref "U801") (pin "47") (pinfunction "VSS_3_47") (pintype "power_in"))
      (node (ref "U801") (pin "8") (pinfunction "VSSA_8") (pintype "power_in"))
      (node (ref "U901") (pin "11") (pinfunction "GND_11") (pintype "power_in"))
      (node (ref "U902") (pin "11") (pinfunction "GND_11") (pintype "power_in"))
      (node (ref "U903") (pin "1") (pinfunction "~{1OE}_1") (pintype "input"))
      (node (ref "U903") (pin "4") (pinfunction "GND_4") (pintype "power_in"))
      (node (ref "X101") (pin "2") (pinfunction "NC_2_2") (pintype "power_in"))
      (node (ref "X101") (pin "4") (pinfunction "NC_4_4") (pintype "power_in"))
      (node (ref "X503") (pin "2") (pinfunction "S_2") (pintype "passive"))
      (node (ref "X801") (pin "2") (pinfunction "NC_2_2") (pintype "power_in"))
      (node (ref "X801") (pin "4") (pinfunction "NC_4_4") (pintype "power_in"))
    )
    (net (code "47") (name "GPIO_EXT_1") (class "Default")
      (node (ref "J403") (pin "6") (pinfunction "6_6") (pintype "passive"))
      (node (ref "U101") (pin "8") (pinfunction "PC14_8") (pintype "bidirectional"))
    )
    (net (code "48") (name "GYRO_DRDY") (class "Default")
      (node (ref "U101") (pin "35") (pinfunction "PB0_35") (pintype "bidirectional"))
      (node (ref "U501") (pin "6") (pinfunction "DRDY/INT2_6") (pintype "output"))
      (node (ref "U502") (pin "6") (pinfunction "DRDY/INT2_6") (pintype "bidirectional"))
      (node (ref "X503") (pin "5") (pinfunction "S_5") (pintype "passive"))
    )
    (net (code "49") (name "IO-BOOT0") (class "Default")
      (node (ref "IO-BOOT1101") (pin "P$1") (pinfunction "P$1_P$1") (pintype "passive"))
      (node (ref "R801") (pin "P$1") (pinfunction "1_P$1") (pintype "passive"))
      (node (ref "U801") (pin "44") (pinfunction "BOOT0_44") (pintype "input"))
    )
    (net (code "50") (name "IO-CH1") (class "Default")
      (node (ref "U801") (pin "10") (pinfunction "PA0_10") (pintype "bidirectional"))
      (node (ref "U902") (pin "9") (pinfunction "A8_9") (pintype "bidirectional"))
    )
    (net (code "51") (name "IO-CH2") (class "Default")
      (node (ref "U801") (pin "11") (pinfunction "PA1_11") (pintype "bidirectional"))
      (node (ref "U902") (pin "8") (pinfunction "A7_8") (pintype "bidirectional"))
    )
    (net (code "52") (name "IO-CH3") (class "Default")
      (node (ref "U801") (pin "45") (pinfunction "PB8_45") (pintype "bidirectional"))
      (node (ref "U902") (pin "7") (pinfunction "A6_7") (pintype "bidirectional"))
    )
    (net (code "53") (name "IO-CH4") (class "Default")
      (node (ref "U801") (pin "46") (pinfunction "PB9_46") (pintype "bidirectional"))
      (node (ref "U902") (pin "6") (pinfunction "A5_6") (pintype "bidirectional"))
    )
    (net (code "54") (name "IO-CH5") (class "Default")
      (node (ref "U801") (pin "16") (pinfunction "PA6_16") (pintype "bidirectional"))
      (node (ref "U902") (pin "5") (pinfunction "A4_5") (pintype "bidirectional"))
    )
    (net (code "55") (name "IO-CH6") (class "Default")
      (node (ref "U801") (pin "17") (pinfunction "PA7_17") (pintype "bidirectional"))
      (node (ref "U902") (pin "4") (pinfunction "A3_4") (pintype "bidirectional"))
    )
    (net (code "56") (name "IO-CH7") (class "Default")
      (node (ref "U801") (pin "18") (pinfunction "PB0_18") (pintype "bidirectional"))
      (node (ref "U902") (pin "3") (pinfunction "A2_3") (pintype "bidirectional"))
    )
    (net (code "57") (name "IO-CH8") (class "Default")
      (node (ref "U801") (pin "19") (pinfunction "PB1_19") (pintype "bidirectional"))
      (node (ref "U902") (pin "1") (pinfunction "A1_1") (pintype "bidirectional"))
    )
    (net (code "58") (name "IO-SWCLK") (class "Default")
      (node (ref "JX802") (pin "4") (pinfunction "S_4") (pintype "passive"))
      (node (ref "U801") (pin "37") (pinfunction "PA14_37") (pintype "bidirectional"))
    )
    (net (code "59") (name "IO-SWDIO") (class "Default")
      (node (ref "JX802") (pin "2") (pinfunction "S_2") (pintype "passive"))
      (node (ref "U801") (pin "34") (pinfunction "PA13_34") (pintype "bidirectional"))
    )
    (net (code "60") (name "IO-SWO") (class "Default")
      (node (ref "JX802") (pin "6") (pinfunction "S_6") (pintype "passive"))
      (node (ref "U801") (pin "39") (pinfunction "PB3_39") (pintype "bidirectional"))
    )
    (net (code "61") (name "IO-USART1_RX") (class "Default")
      (node (ref "J801") (pin "P$3") (pinfunction "P$3_P$3") (pintype "bidirectional"))
      (node (ref "JX801") (pin "2") (pinfunction "+5V_2") (pintype "bidirectional"))
      (node (ref "U801") (pin "31") (pinfunction "PA10_31") (pintype "bidirectional"))
    )
    (net (code "62") (name "IO-USART1_TX") (class "Default")
      (node (ref "JX801") (pin "1") (pinfunction "PPM_1") (pintype "bidirectional"))
      (node (ref "R101") (pin "P$2") (pinfunction "2_P$2") (pintype "passive"))
      (node (ref "U801") (pin "30") (pinfunction "PA9_30") (pintype "bidirectional"))
    )
    (net (code "63") (name "IO-VDD_3V3") (class "Default")
      (node (ref "C1003") (pin "P$1") (pinfunction "1_P$1") (pintype "passive"))
      (node (ref "C1004") (pin "P$1") (pinfunction "1_P$1") (pintype "passive"))
      (node (ref "C802") (pin "P$1") (pinfunction "1_P$1") (pintype "passive"))
      (node (ref "C803") (pin "P$1") (pinfunction "1_P$1") (pintype "passive"))
      (node (ref "C804") (pin "P$1") (pinfunction "1_P$1") (pintype "passive"))
      (node (ref "C901") (pin "P$1") (pinfunction "1_P$1") (pintype "passive"))
      (node (ref "C903") (pin "P$1") (pinfunction "1_P$1") (pintype "passive"))
      (node (ref "D701") (pin "C") (pinfunction "C_C") (pintype "passive"))
      (node (ref "J702") (pin "1") (pinfunction "1_1") (pintype "passive"))
      (node (ref "JX802") (pin "1") (pinfunction "S_1") (pintype "passive"))
      (node (ref "U1002") (pin "7") (pinfunction "VOUT2_7") (pintype "bidirectional"))
      (node (ref "U801") (pin "24") (pinfunction "VDD_1_24") (pintype "power_in"))
      (node (ref "U801") (pin "36") (pinfunction "VDD_2_36") (pintype "power_in"))
      (node (ref "U801") (pin "48") (pinfunction "VDD_3_48") (pintype "power_in"))
      (node (ref "U801") (pin "9") (pinfunction "VDDA_9") (pintype "power_in"))
      (node (ref "U902") (pin "10") (pinfunction "OE_10") (pintype "input"))
      (node (ref "U902") (pin "19") (pinfunction "VCCB_19") (pintype "input"))
      (node (ref "U902") (pin "2") (pinfunction "VCCA_2") (pintype "input"))
      (node (ref "U903") (pin "8") (pinfunction "VCC_8") (pintype "power_in"))
    )
    (net (code "64") (name "IO-VDD_5V5") (class "Default")
      (node (ref "C1001") (pin "P$1") (pinfunction "1_P$1") (pintype "passive"))
      (node (ref "C1005") (pin "P$1") (pinfunction "1_P$1") (pintype "passive"))
      (node (ref "D1001") (pin "3") (pinfunction "CC_3") (pintype "passive"))
      (node (ref "J901") (pin "2") (pinfunction "S_2") (pintype "passive"))
      (node (ref "LED702") (pin "A") (pinfunction "A_A") (pintype "passive"))
      (node (ref "LED703") (pin "A") (pinfunction "A_A") (pintype "passive"))
      (node (ref "LED705") (pin "A") (pinfunction "A_A") (pintype "passive"))
      (node (ref "U1002") (pin "1") (pinfunction "VIN_1") (pintype "bidirectional"))
      (node (ref "U1002") (pin "4") (pinfunction "EN2_4") (pintype "bidirectional"))
    )
    (net (code "65") (name "IO-~{RESET}") (class "Default")
      (node (ref "C801") (pin "P$2") (pinfunction "2_P$2") (pintype "passive"))
      (node (ref "S801") (pin "A1") (pinfunction "1_A1") (pintype "passive"))
      (node (ref "U1002") (pin "3") (pinfunction "POR2_3") (pintype "bidirectional"))
      (node (ref "U801") (pin "7") (pinfunction "NRST_7") (pintype "input"))
    )
    (net (code "66") (name "IO-~{VDD_SERVO_IN_FAULT}") (class "Default")
      (node (ref "U1001") (pin "4") (pinfunction "~{FAULT}_4") (pintype "bidirectional"))
      (node (ref "U801") (pin "38") (pinfunction "PA15_38") (pintype "bidirectional"))
    )
    (net (code "67") (name "MAG_DRDY") (class "Default")
      (node (ref "U101") (pin "36") (pinfunction "PB1_36") (pintype "bidirectional"))
      (node (ref "U504") (pin "9") (pinfunction "INT2_9") (pintype "bidirectional"))
      (node (ref "X503") (pin "4") (pinfunction "S_4") (pintype "passive"))
    )
    (net (code "68") (name "MPU_DRDY") (class "Default")
      (node (ref "U101") (pin "62") (pinfunction "PD15_62") (pintype "bidirectional"))
      (node (ref "U505") (pin "12") (pinfunction "INT_12") (pintype "bidirectional"))
    )
    (net (code "69") (name "Net-(C102-1)") (class "Default")
      (node (ref "C102") (pin "P$1") (pinfunction "1_P$1") (pintype "passive"))
      (node (ref "U101") (pin "12") (pinfunction "OSC_IN_12") (pintype "input"))
      (node (ref "X101") (pin "3") (pinfunction "3_3") (pintype "bidirectional"))
    )
    (net (code "70") (name "Net-(C103-2)") (class "Default")
      (node (ref "C103") (pin "P$2") (pinfunction "2_P$2") (pintype "passive"))
      (node (ref "U101") (pin "13") (pinfunction "OSC_OUT_13") (pintype "output"))
      (node (ref "X101") (pin "1") (pinfunction "1_1") (pintype "bidirectional"))
    )
    (net (code "71") (name "Net-(C504-1)") (class "Default")
      (node (ref "C504") (pin "P$1") (pinfunction "1_P$1") (pintype "passive"))
      (node (ref "U501") (pin "14") (pinfunction "PLLFILT_14") (pintype "bidirectional"))
    )
    (net (code "72") (name "Net-(C505-1)") (class "Default")
      (node (ref "C505") (pin "P$1") (pinfunction "1_P$1") (pintype "passive"))
      (node (ref "U502") (pin "14") (pinfunction "CAP_14") (pintype "bidirectional"))
    )
    (net (code "73") (name "Net-(C509-1)") (class "Default")
      (node (ref "C509") (pin "P$1") (pinfunction "1_P$1") (pintype "passive"))
      (node (ref "U504") (pin "15") (pinfunction "C1_15") (pintype "bidirectional"))
    )
    (net (code "74") (name "Net-(C510-1)") (class "Default")
      (node (ref "C510") (pin "P$1") (pinfunction "1_P$1") (pintype "passive"))
      (node (ref "U504") (pin "2") (pinfunction "SETC_2") (pintype "bidirectional"))
    )
    (net (code "75") (name "Net-(C510-2)") (class "Default")
      (node (ref "C510") (pin "P$2") (pinfunction "2_P$2") (pintype "passive"))
      (node (ref "U504") (pin "3") (pinfunction "SETP_3") (pintype "bidirectional"))
    )
    (net (code "76") (name "Net-(C512-1)") (class "Default")
      (node (ref "C512") (pin "P$1") (pinfunction "1_P$1") (pintype "passive"))
      (node (ref "U505") (pin "10") (pinfunction "REGOUT_10") (pintype "bidirectional"))
    )
    (net (code "77") (name "Net-(C515-1)") (class "Default")
      (node (ref "C515") (pin "P$1") (pinfunction "1_P$1") (pintype "passive"))
      (node (ref "U505") (pin "20") (pinfunction "CPOUT_20") (pintype "bidirectional"))
    )
    (net (code "78") (name "Net-(C601-1)") (class "Default")
      (node (ref "C601") (pin "P$1") (pinfunction "1_P$1") (pintype "passive"))
      (node (ref "C615") (pin "P$1") (pinfunction "1_P$1") (pintype "passive"))
      (node (ref "L603") (pin "P$2") (pinfunction "P$2_P$2") (pintype "bidirectional"))
      (node (ref "R603") (pin "P$1") (pinfunction "1_P$1") (pintype "passive"))
      (node (ref "U603") (pin "1") (pinfunction "VIN_1") (pintype "bidirectional"))
      (node (ref "U603") (pin "4") (pinfunction "EN2_4") (pintype "bidirectional"))
    )
    (net (code "79") (name "Net-(C602-2)") (class "Default")
      (node (ref "C602") (pin "P$2") (pinfunction "2_P$2") (pintype "passive"))
      (node (ref "U603") (pin "6") (pinfunction "CSET_6") (pintype "bidirectional"))
    )
    (net (code "80") (name "Net-(C611-1)") (class "Default")
      (node (ref "C611") (pin "P$1") (pinfunction "1_P$1") (pintype "passive"))
      (node (ref "U101") (pin "49") (pinfunction "VCAP_1_49") (pintype "power_in"))
    )
    (net (code "81") (name "Net-(C613-1)") (class "Default")
      (node (ref "C613") (pin "P$1") (pinfunction "1_P$1") (pintype "passive"))
      (node (ref "U101") (pin "73") (pinfunction "VCAP_2_73") (pintype "power_in"))
    )
    (net (code "82") (name "Net-(C703-1)") (class "Default")
      (node (ref "C703") (pin "P$1") (pinfunction "1_P$1") (pintype "passive"))
      (node (ref "J701") (pin "1") (pinfunction "1_1") (pintype "passive"))
      (node (ref "R703") (pin "P$1") (pinfunction "1_P$1") (pintype "passive"))
      (node (ref "U702") (pin "1") (pinfunction "OUT_1") (pintype "output"))
    )
    (net (code "83") (name "Net-(C704-1)") (class "Default")
      (node (ref "C704") (pin "P$1") (pinfunction "1_P$1") (pintype "passive"))
      (node (ref "R705") (pin "P$1") (pinfunction "1_P$1") (pintype "passive"))
      (node (ref "U702") (pin "6") (pinfunction "VCC_6") (pintype "bidirectional"))
    )
    (net (code "84") (name "Net-(C805-1)") (class "Default")
      (node (ref "C805") (pin "P$1") (pinfunction "1_P$1") (pintype "passive"))
      (node (ref "U801") (pin "5") (pinfunction "PD0/OSC<=_5") (pintype "bidirectional"))
      (node (ref "X801") (pin "3") (pinfunction "3_3") (pintype "bidirectional"))
    )
    (net (code "85") (name "Net-(C806-2)") (class "Default")
      (node (ref "C806") (pin "P$2") (pinfunction "2_P$2") (pintype "passive"))
      (node (ref "U801") (pin "6") (pinfunction "PD1/OSC=>_6") (pintype "bidirectional"))
      (node (ref "X801") (pin "1") (pinfunction "1_1") (pintype "bidirectional"))
    )
    (net (code "86") (name "Net-(C1002-1)") (class "Default")
      (node (ref "C1002") (pin "P$1") (pinfunction "1_P$1") (pintype "passive"))
      (node (ref "U1002") (pin "6") (pinfunction "CSET_6") (pintype "bidirectional"))
    )
    (net (code "87") (name "Net-(C1105-1)") (class "Default")
      (node (ref "C1105") (pin "P$1") (pinfunction "1_P$1") (pintype "passive"))
      (node (ref "U1101") (pin "P$18") (pinfunction "VS1_P$18") (pintype "bidirectional"))
      (node (ref "U1102") (pin "P$1") (pinfunction "S_P$1") (pintype "passive"))
      (node (ref "U1102") (pin "P$3") (pinfunction "S_P$3") (pintype "passive"))
    )
    (net (code "88") (name "Net-(C1106-1)") (class "Default")
      (node (ref "C1106") (pin "P$1") (pinfunction "1_P$1") (pintype "passive"))
      (node (ref "U1101") (pin "P$16") (pinfunction "VS2_P$16") (pintype "bidirectional"))
      (node (ref "U1103") (pin "P$1") (pinfunction "S_P$1") (pintype "passive"))
      (node (ref "U1103") (pin "P$3") (pinfunction "S_P$3") (pintype "passive"))
    )
    (net (code "89") (name "Net-(C1107-1)") (class "Default")
      (node (ref "C1107") (pin "P$1") (pinfunction "1_P$1") (pintype "passive"))
      (node (ref "U1101") (pin "P$14") (pinfunction "VS3_P$14") (pintype "bidirectional"))
      (node (ref "U1104") (pin "P$1") (pinfunction "S_P$1") (pintype "passive"))
      (node (ref "U1104") (pin "P$3") (pinfunction "S_P$3") (pintype "passive"))
    )
    (net (code "90") (name "Net-(C1108-1)") (class "Default")
      (node (ref "C1108") (pin "P$1") (pinfunction "1_P$1") (pintype "passive"))
      (node (ref "R1105") (pin "P$2") (pinfunction "2_P$2") (pintype "passive"))
      (node (ref "R1106") (pin "P$1") (pinfunction "1_P$1") (pintype "passive"))
      (node (ref "U1101") (pin "P$1") (pinfunction "UV1_P$1") (pintype "bidirectional"))
    )
    (net (code "91") (name "Net-(C1109-1)") (class "Default")
      (node (ref "C1109") (pin "P$1") (pinfunction "1_P$1") (pintype "passive"))
      (node (ref "R1109") (pin "P$2") (pinfunction "2_P$2") (pintype "passive"))
      (node (ref "R1110") (pin "P$1") (pinfunction "1_P$1") (pintype "passive"))
      (node (ref "U1101") (pin "P$3") (pinfunction "UV2_P$3") (pintype "bidirectional"))
    )
    (net (code "92") (name "Net-(C1110-1)") (class "Default")
      (node (ref "C1110") (pin "P$1") (pinfunction "1_P$1") (pintype "passive"))
      (node (ref "R1112") (pin "P$2") (pinfunction "2_P$2") (pintype "passive"))
      (node (ref "R1113") (pin "P$1") (pinfunction "1_P$1") (pintype "passive"))
      (node (ref "U1101") (pin "P$5") (pinfunction "UV3_P$5") (pintype "bidirectional"))
    )
    (net (code "93") (name "Net-(D201-PadC)") (class "Default")
      (node (ref "D201") (pin "C") (pinfunction "C_C") (pintype "passive"))
      (node (ref "J201") (pin "1") (pinfunction "1_1") (pintype "passive"))
      (node (ref "L201") (pin "P$2") (pinfunction "P$2_P$2") (pintype "bidirectional"))
    )
    (net (code "94") (name "Net-(D202-PadC)") (class "Default")
      (node (ref "D202") (pin "C") (pinfunction "C_C") (pintype "passive"))
      (node (ref "J202") (pin "1") (pinfunction "1_1") (pintype "passive"))
      (node (ref "L202") (pin "P$2") (pinfunction "P$2_P$2") (pintype "bidirectional"))
    )
    (net (code "95") (name "Net-(D203-PadC)") (class "Default")
      (node (ref "D203") (pin "C") (pinfunction "C_C") (pintype "passive"))
      (node (ref "J203") (pin "1") (pinfunction "1_1") (pintype "passive"))
      (node (ref "J204") (pin "1") (pinfunction "1_1") (pintype "passive"))
      (node (ref "L203") (pin "P$2") (pinfunction "P$2_P$2") (pintype "bidirectional"))
    )
    (net (code "96") (name "Net-(D401-PadC)") (class "Default")
      (node (ref "D401") (pin "C") (pinfunction "C_C") (pintype "passive"))
      (node (ref "J401") (pin "1") (pinfunction "1_1") (pintype "passive"))
      (node (ref "J402") (pin "1") (pinfunction "1_1") (pintype "passive"))
      (node (ref "L401") (pin "P$2") (pinfunction "P$2_P$2") (pintype "bidirectional"))
    )
    (net (code "97") (name "Net-(D402-PadC)") (class "Default")
      (node (ref "D402") (pin "C") (pinfunction "C_C") (pintype "passive"))
      (node (ref "J403") (pin "1") (pinfunction "1_1") (pintype "passive"))
      (node (ref "L402") (pin "P$2") (pinfunction "P$2_P$2") (pintype "bidirectional"))
    )
    (net (code "98") (name "Net-(D403-PadC)") (class "Default")
      (node (ref "D403") (pin "C") (pinfunction "C_C") (pintype "passive"))
      (node (ref "J404") (pin "1") (pinfunction "1_1") (pintype "passive"))
      (node (ref "L404") (pin "P$2") (pinfunction "P$2_P$2") (pintype "bidirectional"))
    )
    (net (code "99") (name "Net-(D404-PadC)") (class "Default")
      (node (ref "D404") (pin "C") (pinfunction "C_C") (pintype "passive"))
      (node (ref "J405") (pin "1") (pinfunction "1_1") (pintype "passive"))
      (node (ref "L403") (pin "P$2") (pinfunction "P$2_P$2") (pintype "bidirectional"))
    )
    (net (code "100") (name "Net-(D904-C)") (class "Default")
      (node (ref "D903") (pin "C") (pinfunction "C_C") (pintype "passive"))
      (node (ref "D904") (pin "CATHODE") (pinfunction "C_CATHODE") (pintype "passive"))
      (node (ref "L901") (pin "P$1") (pinfunction "P$1_P$1") (pintype "bidirectional"))
    )
    (net (code "101") (name "Net-(D1001-A1)") (class "Default")
      (node (ref "D1001") (pin "1") (pinfunction "A1_1") (pintype "passive"))
      (node (ref "F1001") (pin "2") (pinfunction "2_2") (pintype "bidirectional"))
    )
    (net (code "102") (name "Net-(D1001-A2)") (class "Default")
      (node (ref "D1001") (pin "2") (pinfunction "A2_2") (pintype "passive"))
      (node (ref "U1001") (pin "8") (pinfunction "OUT_8") (pintype "bidirectional"))
    )
    (net (code "103") (name "Net-(J301-2)") (class "Default")
      (node (ref "J301") (pin "D-") (pinfunction "2_D-") (pintype "bidirectional"))
      (node (ref "J302") (pin "3") (pinfunction "3_3") (pintype "passive"))
      (node (ref "U302") (pin "1") (pinfunction "D1I_1") (pintype "bidirectional"))
    )
    (net (code "104") (name "Net-(J301-3)") (class "Default")
      (node (ref "J301") (pin "D+") (pinfunction "3_D+") (pintype "bidirectional"))
      (node (ref "J302") (pin "2") (pinfunction "2_2") (pintype "passive"))
      (node (ref "U302") (pin "3") (pinfunction "D2I_3") (pintype "bidirectional"))
    )
    (net (code "105") (name "Net-(J901A-S)") (class "Default")
      (node (ref "J901") (pin "1") (pinfunction "S_1") (pintype "passive"))
      (node (ref "R909") (pin "P$2") (pinfunction "2_P$2") (pintype "passive"))
    )
    (net (code "106") (name "Net-(J901B-S)") (class "Default")
      (node (ref "J901") (pin "10") (pinfunction "S_10") (pintype "passive"))
      (node (ref "R914") (pin "P$2") (pinfunction "2_P$2") (pintype "passive"))
    )
    (net (code "107") (name "Net-(J901C-S)") (class "Default")
      (node (ref "J901") (pin "13") (pinfunction "S_13") (pintype "passive"))
      (node (ref "R906") (pin "P$2") (pinfunction "2_P$2") (pintype "passive"))
    )
    (net (code "108") (name "Net-(J901D-S)") (class "Default")
      (node (ref "J901") (pin "16") (pinfunction "S_16") (pintype "passive"))
      (node (ref "R915") (pin "P$2") (pinfunction "2_P$2") (pintype "passive"))
    )
    (net (code "109") (name "Net-(J901E-S)") (class "Default")
      (node (ref "J901") (pin "19") (pinfunction "S_19") (pintype "passive"))
      (node (ref "R907") (pin "P$2") (pinfunction "2_P$2") (pintype "passive"))
    )
    (net (code "110") (name "Net-(J901G-S)") (class "Default")
      (node (ref "J901") (pin "22") (pinfunction "S_22") (pintype "passive"))
      (node (ref "R916") (pin "P$2") (pinfunction "2_P$2") (pintype "passive"))
    )
    (net (code "111") (name "Net-(J901H-S)") (class "Default")
      (node (ref "J901") (pin "25") (pinfunction "S_25") (pintype "passive"))
      (node (ref "R908") (pin "P$2") (pinfunction "2_P$2") (pintype "passive"))
    )
    (net (code "112") (name "Net-(J901I-S)") (class "Default")
      (node (ref "J901") (pin "28") (pinfunction "S_28") (pintype "passive"))
      (node (ref "R917") (pin "P$2") (pinfunction "2_P$2") (pintype "passive"))
    )
    (net (code "113") (name "Net-(J901J-S)") (class "Default")
      (node (ref "J901") (pin "31") (pinfunction "S_31") (pintype "passive"))
      (node (ref "R902") (pin "P$2") (pinfunction "2_P$2") (pintype "passive"))
    )
    (net (code "114") (name "Net-(J901K-S)") (class "Default")
      (node (ref "J901") (pin "34") (pinfunction "S_34") (pintype "passive"))
      (node (ref "R911") (pin "P$2") (pinfunction "2_P$2") (pintype "passive"))
    )
    (net (code "115") (name "Net-(J901L-S)") (class "Default")
      (node (ref "J901") (pin "37") (pinfunction "S_37") (pintype "passive"))
      (node (ref "R903") (pin "P$2") (pinfunction "2_P$2") (pintype "passive"))
    )
    (net (code "116") (name "Net-(J901M-S)") (class "Default")
      (node (ref "J901") (pin "4") (pinfunction "S_4") (pintype "passive"))
      (node (ref "R910") (pin "P$2") (pinfunction "2_P$2") (pintype "passive"))
    )
    (net (code "117") (name "Net-(J901N-S)") (class "Default")
      (node (ref "J901") (pin "40") (pinfunction "S_40") (pintype "passive"))
      (node (ref "R912") (pin "P$2") (pinfunction "2_P$2") (pintype "passive"))
    )
    (net (code "118") (name "Net-(J901O-S)") (class "Default")
      (node (ref "J901") (pin "43") (pinfunction "S_43") (pintype "passive"))
      (node (ref "R904") (pin "P$2") (pinfunction "2_P$2") (pintype "passive"))
    )
    (net (code "119") (name "Net-(J901P-S)") (class "Default")
      (node (ref "J901") (pin "46") (pinfunction "S_46") (pintype "passive"))
      (node (ref "R913") (pin "P$2") (pinfunction "2_P$2") (pintype "passive"))
    )
    (net (code "120") (name "Net-(J901Q-S)") (class "Default")
      (node (ref "J901") (pin "7") (pinfunction "S_7") (pintype "passive"))
      (node (ref "R905") (pin "P$2") (pinfunction "2_P$2") (pintype "passive"))
    )
    (net (code "121") (name "Net-(L701-2)") (class "Default")
      (node (ref "L701") (pin "P$2") (pinfunction "2_P$2") (pintype "passive"))
      (node (ref "U702") (pin "5") (pinfunction "SW_5") (pintype "passive"))
    )
    (net (code "122") (name "Net-(Q601-PadC)") (class "Default")
      (node (ref "Q601") (pin "C") (pinfunction "C_C") (pintype "passive"))
      (node (ref "R621") (pin "2") (pinfunction "2_2") (pintype "passive"))
    )
    (net (code "123") (name "Net-(R101-1)") (class "Default")
      (node (ref "R101") (pin "P$1") (pinfunction "1_P$1") (pintype "passive"))
      (node (ref "U101") (pin "69") (pinfunction "PA10_69") (pintype "bidirectional"))
    )
    (net (code "124") (name "Net-(R102-1)") (class "Default")
      (node (ref "R102") (pin "P$1") (pinfunction "1_P$1") (pintype "passive"))
      (node (ref "U101") (pin "37") (pinfunction "PB2_37") (pintype "bidirectional"))
    )
    (net (code "125") (name "Net-(R201-1)") (class "Default")
      (node (ref "R201") (pin "P$1") (pinfunction "1_P$1") (pintype "passive"))
      (node (ref "U201") (pin "20") (pinfunction "B1_20") (pintype "bidirectional"))
    )
    (net (code "126") (name "Net-(R202-1)") (class "Default")
      (node (ref "R202") (pin "P$1") (pinfunction "1_P$1") (pintype "passive"))
      (node (ref "U201") (pin "17") (pinfunction "B3_17") (pintype "bidirectional"))
    )
    (net (code "127") (name "Net-(R203-1)") (class "Default")
      (node (ref "R203") (pin "P$1") (pinfunction "1_P$1") (pintype "passive"))
      (node (ref "U201") (pin "15") (pinfunction "B5_15") (pintype "bidirectional"))
    )
    (net (code "128") (name "Net-(R204-1)") (class "Default")
      (node (ref "R204") (pin "P$1") (pinfunction "1_P$1") (pintype "passive"))
      (node (ref "U201") (pin "13") (pinfunction "B7_13") (pintype "bidirectional"))
    )
    (net (code "129") (name "Net-(R205-1)") (class "Default")
      (node (ref "R205") (pin "P$1") (pinfunction "1_P$1") (pintype "passive"))
      (node (ref "U202") (pin "17") (pinfunction "B3_17") (pintype "bidirectional"))
    )
    (net (code "130") (name "Net-(R206-1)") (class "Default")
      (node (ref "R206") (pin "P$1") (pinfunction "1_P$1") (pintype "passive"))
      (node (ref "U202") (pin "15") (pinfunction "B5_15") (pintype "bidirectional"))
    )
    (net (code "131") (name "Net-(R207-1)") (class "Default")
      (node (ref "R207") (pin "P$1") (pinfunction "1_P$1") (pintype "passive"))
      (node (ref "U202") (pin "13") (pinfunction "B7_13") (pintype "bidirectional"))
    )
    (net (code "132") (name "Net-(R208-1)") (class "Default")
      (node (ref "R208") (pin "P$1") (pinfunction "1_P$1") (pintype "passive"))
      (node (ref "U201") (pin "18") (pinfunction "B2_18") (pintype "bidirectional"))
    )
    (net (code "133") (name "Net-(R209-1)") (class "Default")
      (node (ref "R209") (pin "P$1") (pinfunction "1_P$1") (pintype "passive"))
      (node (ref "U201") (pin "16") (pinfunction "B4_16") (pintype "bidirectional"))
    )
    (net (code "134") (name "Net-(R210-1)") (class "Default")
      (node (ref "R210") (pin "P$1") (pinfunction "1_P$1") (pintype "passive"))
      (node (ref "U201") (pin "14") (pinfunction "B6_14") (pintype "bidirectional"))
    )
    (net (code "135") (name "Net-(R211-1)") (class "Default")
      (node (ref "R211") (pin "P$1") (pinfunction "1_P$1") (pintype "passive"))
      (node (ref "U201") (pin "12") (pinfunction "B8_12") (pintype "bidirectional"))
    )
    (net (code "136") (name "Net-(R212-1)") (class "Default")
      (node (ref "R212") (pin "P$1") (pinfunction "1_P$1") (pintype "passive"))
      (node (ref "U202") (pin "16") (pinfunction "B4_16") (pintype "bidirectional"))
    )
    (net (code "137") (name "Net-(R213-1)") (class "Default")
      (node (ref "R213") (pin "P$1") (pinfunction "1_P$1") (pintype "passive"))
      (node (ref "U202") (pin "14") (pinfunction "B6_14") (pintype "bidirectional"))
    )
    (net (code "138") (name "Net-(R214-1)") (class "Default")
      (node (ref "R214") (pin "P$1") (pinfunction "1_P$1") (pintype "passive"))
      (node (ref "U202") (pin "12") (pinfunction "B8_12") (pintype "bidirectional"))
    )
    (net (code "139") (name "Net-(R215-2)") (class "Default")
      (node (ref "J203") (pin "4") (pinfunction "4_4") (pintype "passive"))
      (node (ref "R215") (pin "P$2") (pinfunction "2_P$2") (pintype "passive"))
    )
    (net (code "140") (name "Net-(R216-2)") (class "Default")
      (node (ref "J203") (pin "5") (pinfunction "5_5") (pintype "passive"))
      (node (ref "R216") (pin "P$2") (pinfunction "2_P$2") (pintype "passive"))
    )
    (net (code "141") (name "Net-(R404-2)") (class "Default")
      (node (ref "J401") (pin "2") (pinfunction "2_2") (pintype "passive"))
      (node (ref "R404") (pin "P$2") (pinfunction "2_P$2") (pintype "passive"))
    )
    (net (code "142") (name "Net-(R405-2)") (class "Default")
      (node (ref "J401") (pin "3") (pinfunction "3_3") (pintype "passive"))
      (node (ref "R405") (pin "P$2") (pinfunction "2_P$2") (pintype "passive"))
    )
    (net (code "143") (name "Net-(R407-2)") (class "Default")
      (node (ref "J404") (pin "2") (pinfunction "2_2") (pintype "passive"))
      (node (ref "R407") (pin "P$2") (pinfunction "2_P$2") (pintype "passive"))
    )
    (net (code "144") (name "Net-(R408-2)") (class "Default")
      (node (ref "J404") (pin "4") (pinfunction "4_4") (pintype "passive"))
      (node (ref "R408") (pin "P$2") (pinfunction "2_P$2") (pintype "passive"))
    )
    (net (code "145") (name "Net-(R608-2)") (class "Default")
      (node (ref "D602") (pin "C") (pinfunction "C_C") (pintype "passive"))
      (node (ref "R608") (pin "P$2") (pinfunction "2_P$2") (pintype "passive"))
    )
    (net (code "146") (name "Net-(R616-1)") (class "Default")
      (node (ref "R616") (pin "P$1") (pinfunction "1_P$1") (pintype "passive"))
      (node (ref "U602") (pin "7") (pinfunction "ILIM_7") (pintype "bidirectional"))
    )
    (net (code "147") (name "Net-(R617-1)") (class "Default")
      (node (ref "R617") (pin "P$1") (pinfunction "1_P$1") (pintype "passive"))
      (node (ref "U601") (pin "7") (pinfunction "ILIM_7") (pintype "bidirectional"))
    )
    (net (code "148") (name "Net-(R620-1)") (class "Default")
      (node (ref "Q601") (pin "B") (pinfunction "B_B") (pintype "passive"))
      (node (ref "R620") (pin "P$1") (pinfunction "1_P$1") (pintype "passive"))
    )
    (net (code "149") (name "Net-(R701-1)") (class "Default")
      (node (ref "R701") (pin "P$1") (pinfunction "1_P$1") (pintype "passive"))
      (node (ref "U702") (pin "7") (pinfunction "+IN_7") (pintype "input"))
    )
    (net (code "150") (name "Net-(R702-1)") (class "Default")
      (node (ref "R702") (pin "P$1") (pinfunction "1_P$1") (pintype "passive"))
      (node (ref "R703") (pin "P$2") (pinfunction "2_P$2") (pintype "passive"))
      (node (ref "U702") (pin "8") (pinfunction "-IN_8") (pintype "input"))
    )
    (net (code "151") (name "Net-(R704-2)") (class "Default")
      (node (ref "R704") (pin "P$2") (pinfunction "2_P$2") (pintype "passive"))
      (node (ref "U701") (pin "6") (pinfunction "REXT_6") (pintype "bidirectional"))
    )
    (net (code "152") (name "Net-(R705-2)") (class "Default")
      (node (ref "R705") (pin "P$2") (pinfunction "2_P$2") (pintype "passive"))
      (node (ref "R706") (pin "P$1") (pinfunction "1_P$1") (pintype "passive"))
      (node (ref "U702") (pin "2") (pinfunction "FB_2") (pintype "bidirectional"))
    )
    (net (code "153") (name "Net-(R707-2)") (class "Default")
      (node (ref "R707") (pin "P$2") (pinfunction "2_P$2") (pintype "passive"))
      (node (ref "R735") (pin "P$1") (pinfunction "1_P$1") (pintype "passive"))
    )
    (net (code "154") (name "Net-(R708-2)") (class "Default")
      (node (ref "LED702") (pin "C") (pinfunction "C_C") (pintype "passive"))
      (node (ref "R708") (pin "P$2") (pinfunction "2_P$2") (pintype "passive"))
    )
    (net (code "155") (name "Net-(R709-2)") (class "Default")
      (node (ref "R709") (pin "P$2") (pinfunction "2_P$2") (pintype "passive"))
      (node (ref "R736") (pin "P$1") (pinfunction "1_P$1") (pintype "passive"))
    )
    (net (code "156") (name "Net-(R710-1)") (class "Default")
      (node (ref "J702") (pin "2") (pinfunction "2_2") (pintype "passive"))
      (node (ref "R710") (pin "P$1") (pinfunction "1_P$1") (pintype "passive"))
    )
    (net (code "157") (name "Net-(R711-2)") (class "Default")
      (node (ref "LED704") (pin "C") (pinfunction "C_C") (pintype "passive"))
      (node (ref "R711") (pin "P$2") (pinfunction "2_P$2") (pintype "passive"))
    )
    (net (code "158") (name "Net-(R712-2)") (class "Default")
      (node (ref "LED705") (pin "C") (pinfunction "C_C") (pintype "passive"))
      (node (ref "R712") (pin "P$2") (pinfunction "2_P$2") (pintype "passive"))
    )
    (net (code "159") (name "Net-(R735-2)") (class "Default")
      (node (ref "LED701") (pin "C") (pinfunction "C_C") (pintype "passive"))
      (node (ref "R735") (pin "P$2") (pinfunction "2_P$2") (pintype "passive"))
    )
    (net (code "160") (name "Net-(R736-2)") (class "Default")
      (node (ref "LED703") (pin "C") (pinfunction "C_C") (pintype "passive"))
      (node (ref "R736") (pin "P$2") (pinfunction "2_P$2") (pintype "passive"))
    )
    (net (code "161") (name "Net-(R802-1)") (class "Default")
      (node (ref "R802") (pin "P$1") (pinfunction "1_P$1") (pintype "passive"))
      (node (ref "U801") (pin "20") (pinfunction "PB2_20") (pintype "bidirectional"))
    )
    (net (code "162") (name "Net-(R803-1)") (class "Default")
      (node (ref "R803") (pin "P$1") (pinfunction "1_P$1") (pintype "passive"))
      (node (ref "U801") (pin "12") (pinfunction "PA2_12") (pintype "bidirectional"))
    )
    (net (code "163") (name "Net-(R804-1)") (class "Default")
      (node (ref "R804") (pin "P$1") (pinfunction "1_P$1") (pintype "passive"))
      (node (ref "U801") (pin "13") (pinfunction "PA3_13") (pintype "bidirectional"))
    )
    (net (code "164") (name "Net-(R901-2)") (class "Default")
      (node (ref "D902") (pin "C") (pinfunction "C_C") (pintype "passive"))
      (node (ref "R901") (pin "P$2") (pinfunction "2_P$2") (pintype "passive"))
      (node (ref "R910") (pin "P$1") (pinfunction "1_P$1") (pintype "passive"))
      (node (ref "U903") (pin "3") (pinfunction "2Y_3") (pintype "bidirectional"))
    )
    (net (code "165") (name "Net-(R902-1)") (class "Default")
      (node (ref "R902") (pin "P$1") (pinfunction "1_P$1") (pintype "passive"))
      (node (ref "U901") (pin "20") (pinfunction "B1_20") (pintype "bidirectional"))
    )
    (net (code "166") (name "Net-(R903-1)") (class "Default")
      (node (ref "R903") (pin "P$1") (pinfunction "1_P$1") (pintype "passive"))
      (node (ref "U901") (pin "17") (pinfunction "B3_17") (pintype "bidirectional"))
    )
    (net (code "167") (name "Net-(R904-1)") (class "Default")
      (node (ref "R904") (pin "P$1") (pinfunction "1_P$1") (pintype "passive"))
      (node (ref "U901") (pin "15") (pinfunction "B5_15") (pintype "bidirectional"))
    )
    (net (code "168") (name "Net-(R905-1)") (class "Default")
      (node (ref "R905") (pin "P$1") (pinfunction "1_P$1") (pintype "passive"))
      (node (ref "U902") (pin "20") (pinfunction "B1_20") (pintype "bidirectional"))
    )
    (net (code "169") (name "Net-(R906-1)") (class "Default")
      (node (ref "R906") (pin "P$1") (pinfunction "1_P$1") (pintype "passive"))
      (node (ref "U902") (pin "17") (pinfunction "B3_17") (pintype "bidirectional"))
    )
    (net (code "170") (name "Net-(R907-1)") (class "Default")
      (node (ref "R907") (pin "P$1") (pinfunction "1_P$1") (pintype "passive"))
      (node (ref "U902") (pin "15") (pinfunction "B5_15") (pintype "bidirectional"))
    )
    (net (code "171") (name "Net-(R908-1)") (class "Default")
      (node (ref "R908") (pin "P$1") (pinfunction "1_P$1") (pintype "passive"))
      (node (ref "U902") (pin "13") (pinfunction "B7_13") (pintype "bidirectional"))
    )
    (net (code "172") (name "Net-(R911-1)") (class "Default")
      (node (ref "R911") (pin "P$1") (pinfunction "1_P$1") (pintype "passive"))
      (node (ref "U901") (pin "18") (pinfunction "B2_18") (pintype "bidirectional"))
    )
    (net (code "173") (name "Net-(R912-1)") (class "Default")
      (node (ref "R912") (pin "P$1") (pinfunction "1_P$1") (pintype "passive"))
      (node (ref "U901") (pin "16") (pinfunction "B4_16") (pintype "bidirectional"))
    )
    (net (code "174") (name "Net-(R913-1)") (class "Default")
      (node (ref "R913") (pin "P$1") (pinfunction "1_P$1") (pintype "passive"))
      (node (ref "U901") (pin "14") (pinfunction "B6_14") (pintype "bidirectional"))
    )
    (net (code "175") (name "Net-(R914-1)") (class "Default")
      (node (ref "R914") (pin "P$1") (pinfunction "1_P$1") (pintype "passive"))
      (node (ref "U902") (pin "18") (pinfunction "B2_18") (pintype "bidirectional"))
    )
    (net (code "176") (name "Net-(R915-1)") (class "Default")
      (node (ref "R915") (pin "P$1") (pinfunction "1_P$1") (pintype "passive"))
      (node (ref "U902") (pin "16") (pinfunction "B4_16") (pintype "bidirectional"))
    )
    (net (code "177") (name "Net-(R916-1)") (class "Default")
      (node (ref "R916") (pin "P$1") (pinfunction "1_P$1") (pintype "passive"))
      (node (ref "U902") (pin "14") (pinfunction "B6_14") (pintype "bidirectional"))
    )
    (net (code "178") (name "Net-(R917-1)") (class "Default")
      (node (ref "R917") (pin "P$1") (pinfunction "1_P$1") (pintype "passive"))
      (node (ref "U902") (pin "12") (pinfunction "B8_12") (pintype "bidirectional"))
    )
    (net (code "179") (name "Net-(R918-2)") (class "Default")
      (node (ref "R918") (pin "P$2") (pinfunction "2_P$2") (pintype "passive"))
      (node (ref "R922") (pin "P$1") (pinfunction "1_P$1") (pintype "passive"))
    )
    (net (code "180") (name "Net-(R1001-2)") (class "Default")
      (node (ref "R1001") (pin "P$2") (pinfunction "2_P$2") (pintype "passive"))
      (node (ref "U1001") (pin "7") (pinfunction "ILIM_7") (pintype "bidirectional"))
    )
    (net (code "181") (name "Net-(R1101-2)") (class "Default")
      (node (ref "L1101") (pin "P$2") (pinfunction "P$2_P$2") (pintype "bidirectional"))
      (node (ref "R1101") (pin "P$2") (pinfunction "2_P$2") (pintype "passive"))
    )
    (net (code "182") (name "Net-(R1102-2)") (class "Default")
      (node (ref "L1102") (pin "P$2") (pinfunction "P$2_P$2") (pintype "bidirectional"))
      (node (ref "R1102") (pin "P$2") (pinfunction "2_P$2") (pintype "passive"))
    )
    (net (code "183") (name "Net-(R1103-1)") (class "Default")
      (node (ref "J601") (pin "4") (pinfunction "4_4") (pintype "passive"))
      (node (ref "L1102") (pin "P$1") (pinfunction "P$1_P$1") (pintype "bidirectional"))
      (node (ref "R1103") (pin "P$1") (pinfunction "1_P$1") (pintype "passive"))
    )
    (net (code "184") (name "Net-(R1104-1)") (class "Default")
      (node (ref "J601") (pin "3") (pinfunction "3_3") (pintype "passive"))
      (node (ref "L1101") (pin "P$1") (pinfunction "P$1_P$1") (pintype "bidirectional"))
      (node (ref "R1104") (pin "P$1") (pinfunction "1_P$1") (pintype "passive"))
    )
    (net (code "185") (name "Net-(R1106-2)") (class "Default")
      (node (ref "R1106") (pin "P$2") (pinfunction "2_P$2") (pintype "passive"))
      (node (ref "R1107") (pin "P$1") (pinfunction "1_P$1") (pintype "passive"))
      (node (ref "U1101") (pin "P$2") (pinfunction "OV1_P$2") (pintype "bidirectional"))
    )
    (net (code "186") (name "Net-(R1110-2)") (class "Default")
      (node (ref "R1110") (pin "P$2") (pinfunction "2_P$2") (pintype "passive"))
      (node (ref "R1111") (pin "P$1") (pinfunction "1_P$1") (pintype "passive"))
      (node (ref "U1101") (pin "P$4") (pinfunction "OV2_P$4") (pintype "bidirectional"))
    )
    (net (code "187") (name "Net-(R1113-2)") (class "Default")
      (node (ref "R1113") (pin "P$2") (pinfunction "2_P$2") (pintype "passive"))
      (node (ref "R1114") (pin "P$1") (pinfunction "1_P$1") (pintype "passive"))
      (node (ref "U1101") (pin "P$6") (pinfunction "OV3_P$6") (pintype "bidirectional"))
    )
    (net (code "188") (name "Net-(R1115-2)") (class "Default")
      (node (ref "R1115") (pin "P$2") (pinfunction "2_P$2") (pintype "passive"))
      (node (ref "U1101") (pin "P$24") (pinfunction "HYS_P$24") (pintype "bidirectional"))
    )
    (net (code "189") (name "Net-(U701-OUT0)") (class "Default")
      (node (ref "U701") (pin "9") (pinfunction "OUT0_9") (pintype "open_collector"))
      (node (ref "U703") (pin "C1") (pinfunction "C_C1") (pintype "passive"))
    )
    (net (code "190") (name "Net-(U701-OUT1)") (class "Default")
      (node (ref "U701") (pin "8") (pinfunction "OUT1_8") (pintype "open_collector"))
      (node (ref "U703") (pin "C2") (pinfunction "C_C2") (pintype "passive"))
    )
    (net (code "191") (name "Net-(U701-OUT2)") (class "Default")
      (node (ref "U701") (pin "7") (pinfunction "OUT2_7") (pintype "open_collector"))
      (node (ref "U703") (pin "C3") (pinfunction "C_C3") (pintype "passive"))
    )
    (net (code "192") (name "Net-(U1101-G1)") (class "Default")
      (node (ref "U1101") (pin "P$17") (pinfunction "G1_P$17") (pintype "bidirectional"))
      (node (ref "U1102") (pin "P$2") (pinfunction "G_P$2") (pintype "passive"))
      (node (ref "U1102") (pin "P$4") (pinfunction "G_P$4") (pintype "passive"))
    )
    (net (code "193") (name "Net-(U1101-G2)") (class "Default")
      (node (ref "U1101") (pin "P$15") (pinfunction "G2_P$15") (pintype "bidirectional"))
      (node (ref "U1103") (pin "P$2") (pinfunction "G_P$2") (pintype "passive"))
      (node (ref "U1103") (pin "P$4") (pinfunction "G_P$4") (pintype "passive"))
    )
    (net (code "194") (name "Net-(U1101-G3)") (class "Default")
      (node (ref "U1101") (pin "P$13") (pinfunction "G3_P$13") (pintype "bidirectional"))
      (node (ref "U1104") (pin "P$2") (pinfunction "G_P$2") (pintype "passive"))
      (node (ref "U1104") (pin "P$4") (pinfunction "G_P$4") (pintype "passive"))
    )
    (net (code "195") (name "OTG_FS_DM") (class "Default")
      (node (ref "U101") (pin "70") (pinfunction "PA11_70") (pintype "bidirectional"))
      (node (ref "U302") (pin "6") (pinfunction "D1O_6") (pintype "bidirectional"))
    )
    (net (code "196") (name "OTG_FS_DP") (class "Default")
      (node (ref "U101") (pin "71") (pinfunction "PA12_71") (pintype "bidirectional"))
      (node (ref "U302") (pin "4") (pinfunction "D2O_4") (pintype "bidirectional"))
    )
    (net (code "197") (name "PPM_INPUT") (class "Default")
      (node (ref "D901") (pin "C") (pinfunction "C_C") (pintype "passive"))
      (node (ref "R909") (pin "P$1") (pinfunction "1_P$1") (pintype "passive"))
      (node (ref "U801") (pin "29") (pinfunction "PA8_29") (pintype "bidirectional"))
      (node (ref "U903") (pin "2") (pinfunction "1A_2") (pintype "bidirectional"))
    )
    (net (code "198") (name "PRESSURE_SENS") (class "Default")
      (node (ref "C401") (pin "P$1") (pinfunction "1_P$1") (pintype "passive"))
      (node (ref "R403") (pin "P$2") (pinfunction "2_P$2") (pintype "passive"))
      (node (ref "R406") (pin "P$1") (pinfunction "1_P$1") (pintype "passive"))
      (node (ref "U101") (pin "34") (pinfunction "PC5_34") (pintype "bidirectional"))
    )
    (net (code "199") (name "PRESSURE_SENS_IN") (class "Default")
      (node (ref "ADC_PR") (pin "P$1") (pinfunction "P$1_P$1") (pintype "passive"))
      (node (ref "J402") (pin "2") (pinfunction "2_2") (pintype "passive"))
      (node (ref "R406") (pin "P$2") (pinfunction "2_P$2") (pintype "passive"))
    )
    (net (code "200") (name "RSSI_IN") (class "Default")
      (node (ref "R901") (pin "P$1") (pinfunction "1_P$1") (pintype "passive"))
      (node (ref "U801") (pin "15") (pinfunction "PA5_15") (pintype "bidirectional"))
      (node (ref "U801") (pin "33") (pinfunction "PA12_33") (pintype "bidirectional"))
    )
    (net (code "201") (name "SAFETY") (class "Default")
      (node (ref "J702") (pin "3") (pinfunction "3_3") (pintype "passive"))
      (node (ref "R713") (pin "P$1") (pinfunction "1_P$1") (pintype "passive"))
      (node (ref "U801") (pin "41") (pinfunction "PB5_41") (pintype "bidirectional"))
    )
    (net (code "202") (name "SBUS_INPUT") (class "Default")
      (node (ref "U801") (pin "22") (pinfunction "PB11_22") (pintype "bidirectional"))
      (node (ref "U903") (pin "6") (pinfunction "1Y_6") (pintype "bidirectional"))
    )
    (net (code "203") (name "SBUS_OUTPUT") (class "Default")
      (node (ref "U801") (pin "21") (pinfunction "PB10_21") (pintype "bidirectional"))
      (node (ref "U903") (pin "5") (pinfunction "2A_5") (pintype "bidirectional"))
    )
    (net (code "204") (name "SDIO_CK") (class "Default")
      (node (ref "U101") (pin "80") (pinfunction "PC12_80") (pintype "bidirectional"))
      (node (ref "U301") (pin "5") (pinfunction "CLK_5") (pintype "bidirectional"))
    )
    (net (code "205") (name "SDIO_CMD") (class "Default")
      (node (ref "R303") (pin "P$1") (pinfunction "1_P$1") (pintype "passive"))
      (node (ref "U101") (pin "83") (pinfunction "PD2_83") (pintype "bidirectional"))
      (node (ref "U301") (pin "3") (pinfunction "CMD_3") (pintype "bidirectional"))
    )
    (net (code "206") (name "SDIO_D0") (class "Default")
      (node (ref "R304") (pin "P$1") (pinfunction "1_P$1") (pintype "passive"))
      (node (ref "U101") (pin "65") (pinfunction "PC8_65") (pintype "bidirectional"))
      (node (ref "U301") (pin "7") (pinfunction "D0_7") (pintype "bidirectional"))
    )
    (net (code "207") (name "SDIO_D1") (class "Default")
      (node (ref "R305") (pin "P$1") (pinfunction "1_P$1") (pintype "passive"))
      (node (ref "U101") (pin "66") (pinfunction "PC9_66") (pintype "bidirectional"))
      (node (ref "U301") (pin "8") (pinfunction "D1_8") (pintype "bidirectional"))
    )
    (net (code "208") (name "SDIO_D2") (class "Default")
      (node (ref "R301") (pin "P$1") (pinfunction "1_P$1") (pintype "passive"))
      (node (ref "U101") (pin "78") (pinfunction "PC10_78") (pintype "bidirectional"))
      (node (ref "U301") (pin "1") (pinfunction "D2_1") (pintype "bidirectional"))
    )
    (net (code "209") (name "SDIO_D3") (class "Default")
      (node (ref "R302") (pin "P$1") (pinfunction "1_P$1") (pintype "passive"))
      (node (ref "U101") (pin "79") (pinfunction "PC11_79") (pintype "bidirectional"))
      (node (ref "U301") (pin "2") (pinfunction "D3_2") (pintype "bidirectional"))
    )
    (net (code "210") (name "SERIAL1_CTS") (class "Default")
      (node (ref "J201") (pin "4") (pinfunction "4_4") (pintype "passive"))
      (node (ref "R211") (pin "P$2") (pinfunction "2_P$2") (pintype "passive"))
    )
    (net (code "211") (name "SERIAL1_RTS") (class "Default")
      (node (ref "J201") (pin "5") (pinfunction "5_5") (pintype "passive"))
      (node (ref "R204") (pin "P$2") (pinfunction "2_P$2") (pintype "passive"))
    )
    (net (code "212") (name "SERIAL1_RX") (class "Default")
      (node (ref "J201") (pin "3") (pinfunction "3_3") (pintype "passive"))
      (node (ref "R203") (pin "P$2") (pinfunction "2_P$2") (pintype "passive"))
      (node (ref "S1RX") (pin "P$1") (pinfunction "P$1_P$1") (pintype "passive"))
    )
    (net (code "213") (name "SERIAL1_TX") (class "Default")
      (node (ref "J201") (pin "2") (pinfunction "2_2") (pintype "passive"))
      (node (ref "R210") (pin "P$2") (pinfunction "2_P$2") (pintype "passive"))
      (node (ref "S1TX") (pin "P$1") (pinfunction "P$1_P$1") (pintype "passive"))
    )
    (net (code "214") (name "SERIAL2_CTS") (class "Default")
      (node (ref "J202") (pin "4") (pinfunction "4_4") (pintype "passive"))
      (node (ref "R208") (pin "P$2") (pinfunction "2_P$2") (pintype "passive"))
    )
    (net (code "215") (name "SERIAL2_RTS") (class "Default")
      (node (ref "J202") (pin "5") (pinfunction "5_5") (pintype "passive"))
      (node (ref "R201") (pin "P$2") (pinfunction "2_P$2") (pintype "passive"))
    )
    (net (code "216") (name "SERIAL2_RX") (class "Default")
      (node (ref "J202") (pin "3") (pinfunction "3_3") (pintype "passive"))
      (node (ref "R202") (pin "P$2") (pinfunction "2_P$2") (pintype "passive"))
      (node (ref "S2RX") (pin "P$1") (pinfunction "P$1_P$1") (pintype "passive"))
    )
    (net (code "217") (name "SERIAL2_TX") (class "Default")
      (node (ref "J202") (pin "2") (pinfunction "2_2") (pintype "passive"))
      (node (ref "R209") (pin "P$2") (pinfunction "2_P$2") (pintype "passive"))
      (node (ref "S2TX") (pin "P$1") (pinfunction "P$1_P$1") (pintype "passive"))
    )
    (net (code "218") (name "SERIAL3_RX") (class "Default")
      (node (ref "J203") (pin "3") (pinfunction "3_3") (pintype "passive"))
      (node (ref "R207") (pin "P$2") (pinfunction "2_P$2") (pintype "passive"))
      (node (ref "S3RX") (pin "P$1") (pinfunction "P$1_P$1") (pintype "passive"))
    )
    (net (code "219") (name "SERIAL3_TX") (class "Default")
      (node (ref "J203") (pin "2") (pinfunction "2_2") (pintype "passive"))
      (node (ref "R214") (pin "P$2") (pinfunction "2_P$2") (pintype "passive"))
      (node (ref "S3TX") (pin "P$1") (pinfunction "P$1_P$1") (pintype "passive"))
    )
    (net (code "220") (name "SERIAL4_RX") (class "Default")
      (node (ref "J204") (pin "3") (pinfunction "3_3") (pintype "passive"))
      (node (ref "R206") (pin "P$2") (pinfunction "2_P$2") (pintype "passive"))
      (node (ref "S4RX") (pin "P$1") (pinfunction "P$1_P$1") (pintype "passive"))
    )
    (net (code "221") (name "SERIAL4_TX") (class "Default")
      (node (ref "J204") (pin "2") (pinfunction "2_2") (pintype "passive"))
      (node (ref "R213") (pin "P$2") (pinfunction "2_P$2") (pintype "passive"))
      (node (ref "S4TX") (pin "P$1") (pinfunction "P$1_P$1") (pintype "passive"))
    )
    (net (code "222") (name "SERIAL5_RX") (class "Default")
      (node (ref "J204") (pin "5") (pinfunction "5_5") (pintype "passive"))
      (node (ref "R205") (pin "P$2") (pinfunction "2_P$2") (pintype "passive"))
      (node (ref "S5_RX") (pin "P$1") (pinfunction "P$1_P$1") (pintype "passive"))
    )
    (net (code "223") (name "SERIAL5_TX") (class "Default")
      (node (ref "J204") (pin "4") (pinfunction "4_4") (pintype "passive"))
      (node (ref "R212") (pin "P$2") (pinfunction "2_P$2") (pintype "passive"))
      (node (ref "S5_TX") (pin "P$1") (pinfunction "P$1_P$1") (pintype "passive"))
    )
    (net (code "224") (name "SERIAL_FMU_TO_IO") (class "Default")
      (node (ref "R804") (pin "P$2") (pinfunction "2_P$2") (pintype "passive"))
      (node (ref "U101") (pin "63") (pinfunction "PC6_63") (pintype "bidirectional"))
    )
    (net (code "225") (name "SERIAL_IO_TO_FMU") (class "Default")
      (node (ref "R803") (pin "P$2") (pinfunction "2_P$2") (pintype "passive"))
      (node (ref "U101") (pin "64") (pinfunction "PC7_64") (pintype "bidirectional"))
    )
    (net (code "226") (name "SPI_EXT_MISO") (class "Default")
      (node (ref "J403") (pin "3") (pinfunction "3_3") (pintype "passive"))
      (node (ref "U101") (pin "4") (pinfunction "PE5_4") (pintype "bidirectional"))
    )
    (net (code "227") (name "SPI_EXT_MOSI") (class "Default")
      (node (ref "J403") (pin "4") (pinfunction "4_4") (pintype "passive"))
      (node (ref "U101") (pin "5") (pinfunction "PE6_5") (pintype "bidirectional"))
    )
    (net (code "228") (name "SPI_EXT_SCK") (class "Default")
      (node (ref "J403") (pin "2") (pinfunction "2_2") (pintype "passive"))
      (node (ref "U101") (pin "1") (pinfunction "PE2_1") (pintype "bidirectional"))
    )
    (net (code "229") (name "SPI_INT_MISO") (class "Default")
      (node (ref "U101") (pin "31") (pinfunction "PA6_31") (pintype "bidirectional"))
      (node (ref "U501") (pin "4") (pinfunction "SDO/SA0_4") (pintype "bidirectional"))
      (node (ref "U502") (pin "4") (pinfunction "SDO/SA0_4") (pintype "bidirectional"))
      (node (ref "U504") (pin "7") (pinfunction "SDO/SA0_7") (pintype "bidirectional"))
      (node (ref "U505") (pin "9") (pinfunction "AD0/SDO_9") (pintype "bidirectional"))
      (node (ref "U506") (pin "6") (pinfunction "SDO_6") (pintype "bidirectional"))
      (node (ref "X503") (pin "9") (pinfunction "S_9") (pintype "passive"))
    )
    (net (code "230") (name "SPI_INT_MOSI") (class "Default")
      (node (ref "U101") (pin "32") (pinfunction "PA7_32") (pintype "bidirectional"))
      (node (ref "U501") (pin "3") (pinfunction "SDA/SDI/SDO_3") (pintype "bidirectional"))
      (node (ref "U502") (pin "3") (pinfunction "SDA/SDI/SDO_3") (pintype "bidirectional"))
      (node (ref "U504") (pin "6") (pinfunction "SDA/SDI/SDO_6") (pintype "bidirectional"))
      (node (ref "U505") (pin "24") (pinfunction "SDA/SDI_24") (pintype "bidirectional"))
      (node (ref "U506") (pin "7") (pinfunction "SDI/SDA_7") (pintype "bidirectional"))
      (node (ref "X503") (pin "8") (pinfunction "S_8") (pintype "passive"))
    )
    (net (code "231") (name "SPI_INT_SCK") (class "Default")
      (node (ref "U101") (pin "30") (pinfunction "PA5_30") (pintype "bidirectional"))
      (node (ref "U501") (pin "2") (pinfunction "SCL/SPC_2") (pintype "input"))
      (node (ref "U502") (pin "2") (pinfunction "SCL/SPC_2") (pintype "bidirectional"))
      (node (ref "U504") (pin "4") (pinfunction "SCL/SPC_4") (pintype "bidirectional"))
      (node (ref "U505") (pin "23") (pinfunction "SCL/SCLK_23") (pintype "bidirectional"))
      (node (ref "U506") (pin "8") (pinfunction "SCLK_8") (pintype "bidirectional"))
      (node (ref "X503") (pin "10") (pinfunction "S_10") (pintype "passive"))
    )
    (net (code "232") (name "VBAT") (class "Default")
      (node (ref "B601") (pin "1") (pinfunction "POS_1") (pintype "bidirectional"))
      (node (ref "R608") (pin "P$1") (pinfunction "1_P$1") (pintype "passive"))
      (node (ref "U101") (pin "6") (pinfunction "VBAT_6") (pintype "power_in"))
      (node (ref "U801") (pin "1") (pinfunction "VBAT_1") (pintype "power_in"))
    )
    (net (code "233") (name "VBUS") (class "Default")
      (node (ref "C1103") (pin "P$1") (pinfunction "1_P$1") (pintype "passive"))
      (node (ref "J301") (pin "VBUS") (pinfunction "1_VBUS") (pintype "power_in"))
      (node (ref "J302") (pin "1") (pinfunction "1_1") (pintype "passive"))
      (node (ref "R1112") (pin "P$1") (pinfunction "1_P$1") (pintype "passive"))
      (node (ref "U101") (pin "68") (pinfunction "PA9_68") (pintype "bidirectional"))
      (node (ref "U1101") (pin "P$19") (pinfunction "V3_P$19") (pintype "bidirectional"))
      (node (ref "U1104") (pin "P$7") (pinfunction "D_P$7") (pintype "passive"))
      (node (ref "U1104") (pin "P$8") (pinfunction "D_P$8") (pintype "passive"))
      (node (ref "U302") (pin "5") (pinfunction "VBUS_5") (pintype "bidirectional"))
      (node (ref "VBUS") (pin "P$1") (pinfunction "P$1_P$1") (pintype "passive"))
    )
    (net (code "234") (name "VDD_3V3_SENSORS") (class "Default")
      (node (ref "C501") (pin "P$1") (pinfunction "1_P$1") (pintype "passive"))
      (node (ref "C502") (pin "P$1") (pinfunction "1_P$1") (pintype "passive"))
      (node (ref "C503") (pin "P$1") (pinfunction "1_P$1") (pintype "passive"))
      (node (ref "C506") (pin "P$1") (pinfunction "1_P$1") (pintype "passive"))
      (node (ref "C507") (pin "P$1") (pinfunction "1_P$1") (pintype "passive"))
      (node (ref "C508") (pin "P$1") (pinfunction "1_P$1") (pintype "passive"))
      (node (ref "C511") (pin "P$1") (pinfunction "1_P$1") (pintype "passive"))
      (node (ref "C513") (pin "P$1") (pinfunction "1_P$1") (pintype "passive"))
      (node (ref "C514") (pin "P$1") (pinfunction "1_P$1") (pintype "passive"))
      (node (ref "C605") (pin "P$1") (pinfunction "1_P$1") (pintype "passive"))
      (node (ref "C617") (pin "P$1") (pinfunction "1_P$1") (pintype "passive"))
      (node (ref "Q601") (pin "E") (pinfunction "E_E") (pintype "passive"))
      (node (ref "U501") (pin "1") (pinfunction "VDD_IO_1") (pintype "bidirectional"))
      (node (ref "U501") (pin "15") (pinfunction "RES_P15_VDD_15") (pintype "bidirectional"))
      (node (ref "U501") (pin "16") (pinfunction "VDD_16") (pintype "bidirectional"))
      (node (ref "U502") (pin "1") (pinfunction "VDD_IO_1") (pintype "bidirectional"))
      (node (ref "U502") (pin "15") (pinfunction "VDD_15") (pintype "bidirectional"))
      (node (ref "U502") (pin "16") (pinfunction "VDD_16") (pintype "bidirectional"))
      (node (ref "U504") (pin "1") (pinfunction "VDD_IO_1") (pintype "bidirectional"))
      (node (ref "U504") (pin "14") (pinfunction "VDD_14") (pintype "bidirectional"))
      (node (ref "U505") (pin "13") (pinfunction "VDD_13") (pintype "bidirectional"))
      (node (ref "U506") (pin "1") (pinfunction "VDD_1") (pintype "bidirectional"))
      (node (ref "U603") (pin "8") (pinfunction "VOUT1_8") (pintype "bidirectional"))
      (node (ref "VDDA_3V1101") (pin "P$1") (pinfunction "P$1_P$1") (pintype "passive"))
      (node (ref "X503") (pin "1") (pinfunction "S_1") (pintype "passive"))
    )
    (net (code "235") (name "VDD_3V3_SENSORS_EN") (class "Default")
      (node (ref "R603") (pin "P$2") (pinfunction "2_P$2") (pintype "passive"))
      (node (ref "R620") (pin "P$2") (pinfunction "2_P$2") (pintype "passive"))
      (node (ref "R635") (pin "P$2") (pinfunction "2_P$2") (pintype "passive"))
      (node (ref "U101") (pin "2") (pinfunction "PE3_2") (pintype "bidirectional"))
      (node (ref "U603") (pin "5") (pinfunction "EN1_5") (pintype "bidirectional"))
    )
    (net (code "236") (name "VDD_3V3_SPEKTRUM") (class "Default")
      (node (ref "C1008") (pin "P$1") (pinfunction "1_P$1") (pintype "passive"))
      (node (ref "D801") (pin "C") (pinfunction "C_C") (pintype "passive"))
      (node (ref "J801") (pin "P$1") (pinfunction "P$1_P$1") (pintype "bidirectional"))
      (node (ref "U1002") (pin "8") (pinfunction "VOUT1_8") (pintype "bidirectional"))
    )
    (net (code "237") (name "VDD_3V3_SPEKTRUM_EN") (class "Default")
      (node (ref "R1002") (pin "P$2") (pinfunction "2_P$2") (pintype "passive"))
      (node (ref "U1002") (pin "5") (pinfunction "EN1_5") (pintype "bidirectional"))
      (node (ref "U801") (pin "2") (pinfunction "PC13_2") (pintype "bidirectional"))
    )
    (net (code "238") (name "VDD_5V_BRICK") (class "Default")
      (node (ref "C1101") (pin "P$1") (pinfunction "1_P$1") (pintype "passive"))
      (node (ref "J601") (pin "1") (pinfunction "1_1") (pintype "passive"))
      (node (ref "J601") (pin "2") (pinfunction "2_2") (pintype "passive"))
      (node (ref "R1105") (pin "P$1") (pinfunction "1_P$1") (pintype "passive"))
      (node (ref "U1101") (pin "P$21") (pinfunction "V1_P$21") (pintype "bidirectional"))
      (node (ref "U1102") (pin "P$7") (pinfunction "D_P$7") (pintype "passive"))
      (node (ref "U1102") (pin "P$8") (pinfunction "D_P$8") (pintype "passive"))
      (node (ref "VDD_5V_BRICK") (pin "P$1") (pinfunction "P$1_P$1") (pintype "passive"))
    )
    (net (code "239") (name "VDD_5V_HIPOWER") (class "Default")
      (node (ref "C614") (pin "P$1") (pinfunction "1_P$1") (pintype "passive"))
      (node (ref "L201") (pin "P$1") (pinfunction "P$1_P$1") (pintype "bidirectional"))
      (node (ref "U601") (pin "8") (pinfunction "OUT_8") (pintype "bidirectional"))
    )
    (net (code "240") (name "VDD_5V_IN") (class "Default")
      (node (ref "C1104") (pin "P$1") (pinfunction "1_P$1") (pintype "passive"))
      (node (ref "C702") (pin "P$1") (pinfunction "1_P$1") (pintype "passive"))
      (node (ref "F1001") (pin "1") (pinfunction "1_1") (pintype "bidirectional"))
      (node (ref "L603") (pin "P$1") (pinfunction "P$1_P$1") (pintype "bidirectional"))
      (node (ref "L701") (pin "P$1") (pinfunction "1_P$1") (pintype "passive"))
      (node (ref "LED701") (pin "A") (pinfunction "A_A") (pintype "passive"))
      (node (ref "LED704") (pin "A") (pinfunction "A_A") (pintype "passive"))
      (node (ref "R609") (pin "P$2") (pinfunction "2_P$2") (pintype "passive"))
      (node (ref "RN1101") (pin "5") (pinfunction "2_5") (pintype "passive"))
      (node (ref "RN1101") (pin "6") (pinfunction "2_6") (pintype "passive"))
      (node (ref "RN1101") (pin "7") (pinfunction "2_7") (pintype "passive"))
      (node (ref "U1101") (pin "P$12") (pinfunction "VOUT_P$12") (pintype "bidirectional"))
      (node (ref "U1102") (pin "P$5") (pinfunction "D_P$5") (pintype "passive"))
      (node (ref "U1102") (pin "P$6") (pinfunction "D_P$6") (pintype "passive"))
      (node (ref "U1103") (pin "P$5") (pinfunction "D_P$5") (pintype "passive"))
      (node (ref "U1103") (pin "P$6") (pinfunction "D_P$6") (pintype "passive"))
      (node (ref "U1104") (pin "P$5") (pinfunction "D_P$5") (pintype "passive"))
      (node (ref "U1104") (pin "P$6") (pinfunction "D_P$6") (pintype "passive"))
      (node (ref "U601") (pin "1") (pinfunction "IN_1") (pintype "bidirectional"))
      (node (ref "U602") (pin "1") (pinfunction "IN_1") (pintype "bidirectional"))
      (node (ref "U702") (pin "3") (pinfunction "VIN_3") (pintype "power_in"))
      (node (ref "U703") (pin "A1") (pinfunction "A_A1") (pintype "passive"))
      (node (ref "U703") (pin "A2") (pinfunction "A_A2") (pintype "passive"))
      (node (ref "U703") (pin "A3") (pinfunction "A_A3") (pintype "passive"))
      (node (ref "VDD_5V_IN") (pin "P$1") (pinfunction "P$1_P$1") (pintype "passive"))
    )
    (net (code "241") (name "VDD_5V_PERIPH") (class "Default")
      (node (ref "C618") (pin "P$1") (pinfunction "1_P$1") (pintype "passive"))
      (node (ref "L202") (pin "P$1") (pinfunction "P$1_P$1") (pintype "bidirectional"))
      (node (ref "L203") (pin "P$1") (pinfunction "P$1_P$1") (pintype "bidirectional"))
      (node (ref "L401") (pin "P$1") (pinfunction "P$1_P$1") (pintype "bidirectional"))
      (node (ref "L402") (pin "P$1") (pinfunction "P$1_P$1") (pintype "bidirectional"))
      (node (ref "L403") (pin "P$1") (pinfunction "P$1_P$1") (pintype "bidirectional"))
      (node (ref "L404") (pin "P$1") (pinfunction "P$1_P$1") (pintype "bidirectional"))
      (node (ref "U602") (pin "8") (pinfunction "OUT_8") (pintype "bidirectional"))
    )
    (net (code "242") (name "VDD_5V_SENS") (class "Default")
      (node (ref "R609") (pin "P$1") (pinfunction "1_P$1") (pintype "passive"))
      (node (ref "R610") (pin "P$1") (pinfunction "1_P$1") (pintype "passive"))
      (node (ref "U101") (pin "29") (pinfunction "PA4_29") (pintype "bidirectional"))
    )
    (net (code "243") (name "VDD_SERVO") (class "Default")
      (node (ref "C1102") (pin "P$1") (pinfunction "1_P$1") (pintype "passive"))
      (node (ref "D904") (pin "ANODE") (pinfunction "A_ANODE") (pintype "passive"))
      (node (ref "J901") (pin "11") (pinfunction "S_11") (pintype "passive"))
      (node (ref "J901") (pin "14") (pinfunction "S_14") (pintype "passive"))
      (node (ref "J901") (pin "17") (pinfunction "S_17") (pintype "passive"))
      (node (ref "J901") (pin "20") (pinfunction "S_20") (pintype "passive"))
      (node (ref "J901") (pin "23") (pinfunction "S_23") (pintype "passive"))
      (node (ref "J901") (pin "26") (pinfunction "S_26") (pintype "passive"))
      (node (ref "J901") (pin "29") (pinfunction "S_29") (pintype "passive"))
      (node (ref "J901") (pin "32") (pinfunction "S_32") (pintype "passive"))
      (node (ref "J901") (pin "35") (pinfunction "S_35") (pintype "passive"))
      (node (ref "J901") (pin "38") (pinfunction "S_38") (pintype "passive"))
      (node (ref "J901") (pin "41") (pinfunction "S_41") (pintype "passive"))
      (node (ref "J901") (pin "44") (pinfunction "S_44") (pintype "passive"))
      (node (ref "J901") (pin "47") (pinfunction "S_47") (pintype "passive"))
      (node (ref "J901") (pin "5") (pinfunction "S_5") (pintype "passive"))
      (node (ref "J901") (pin "8") (pinfunction "S_8") (pintype "passive"))
      (node (ref "R1109") (pin "P$1") (pinfunction "1_P$1") (pintype "passive"))
      (node (ref "R922") (pin "P$2") (pinfunction "2_P$2") (pintype "passive"))
      (node (ref "U1101") (pin "P$20") (pinfunction "V2_P$20") (pintype "bidirectional"))
      (node (ref "U1103") (pin "P$7") (pinfunction "D_P$7") (pintype "passive"))
      (node (ref "U1103") (pin "P$8") (pinfunction "D_P$8") (pintype "passive"))
      (node (ref "VDD_SERVO") (pin "P$1") (pinfunction "P$1_P$1") (pintype "passive"))
    )
    (net (code "244") (name "VDD_SERVO_IN") (class "Default")
      (node (ref "L901") (pin "P$2") (pinfunction "P$2_P$2") (pintype "bidirectional"))
      (node (ref "U1001") (pin "1") (pinfunction "IN_1") (pintype "bidirectional"))
    )
    (net (code "245") (name "VDD_SERVO_SENS") (class "Default")
      (node (ref "R918") (pin "P$1") (pinfunction "1_P$1") (pintype "passive"))
      (node (ref "R919") (pin "P$2") (pinfunction "2_P$2") (pintype "passive"))
      (node (ref "U801") (pin "14") (pinfunction "PA4_14") (pintype "bidirectional"))
    )
    (net (code "246") (name "unconnected-(J301-4-PadID)") (class "Default")
      (node (ref "J301") (pin "ID") (pinfunction "4_ID") (pintype "passive"))
    )
    (net (code "247") (name "unconnected-(JX301A-S-Pad10)") (class "Default")
      (node (ref "JX301") (pin "10") (pinfunction "S_10") (pintype "passive"))
    )
    (net (code "248") (name "unconnected-(JX301F-S-Pad8)") (class "Default")
      (node (ref "JX301") (pin "8") (pinfunction "S_8") (pintype "passive"))
    )
    (net (code "249") (name "unconnected-(JX802A-S-Pad10)") (class "Default")
      (node (ref "JX802") (pin "10") (pinfunction "S_10") (pintype "passive"))
    )
    (net (code "250") (name "unconnected-(JX802F-S-Pad8)") (class "Default")
      (node (ref "JX802") (pin "8") (pinfunction "S_8") (pintype "passive"))
    )
    (net (code "251") (name "unconnected-(U101I-PC1-Pad16)") (class "Default")
      (node (ref "U101") (pin "16") (pinfunction "PC1_16") (pintype "bidirectional"))
    )
    (net (code "252") (name "unconnected-(U202-A1-Pad1)") (class "Default")
      (node (ref "U202") (pin "1") (pinfunction "A1_1") (pintype "bidirectional"))
    )
    (net (code "253") (name "unconnected-(U202-A2-Pad3)") (class "Default")
      (node (ref "U202") (pin "3") (pinfunction "A2_3") (pintype "bidirectional"))
    )
    (net (code "254") (name "unconnected-(U202-B1-Pad20)") (class "Default")
      (node (ref "U202") (pin "20") (pinfunction "B1_20") (pintype "bidirectional"))
    )
    (net (code "255") (name "unconnected-(U202-B2-Pad18)") (class "Default")
      (node (ref "U202") (pin "18") (pinfunction "B2_18") (pintype "bidirectional"))
    )
    (net (code "256") (name "unconnected-(U501-INT1-Pad7)") (class "Default")
      (node (ref "U501") (pin "7") (pinfunction "INT1_7") (pintype "output"))
    )
    (net (code "257") (name "unconnected-(U502-DEN-Pad8)") (class "Default")
      (node (ref "U502") (pin "8") (pinfunction "DEN_8") (pintype "bidirectional"))
    )
    (net (code "258") (name "unconnected-(U502-INT1-Pad7)") (class "Default")
      (node (ref "U502") (pin "7") (pinfunction "INT1_7") (pintype "bidirectional"))
    )
    (net (code "259") (name "unconnected-(U505-AUX_CL-Pad7)") (class "Default")
      (node (ref "U505") (pin "7") (pinfunction "AUX_CL_7") (pintype "bidirectional"))
    )
    (net (code "260") (name "unconnected-(U505-AUX_DA-Pad6)") (class "Default")
      (node (ref "U505") (pin "6") (pinfunction "AUX_DA_6") (pintype "bidirectional"))
    )
    (net (code "261") (name "unconnected-(U505-CLKOUT-Pad22)") (class "Default")
      (node (ref "U505") (pin "22") (pinfunction "CLKOUT_22") (pintype "bidirectional"))
    )
    (net (code "262") (name "unconnected-(U505-FSYNC-Pad11)") (class "Default")
      (node (ref "U505") (pin "11") (pinfunction "FSYNC_11") (pintype "bidirectional"))
    )
    (net (code "263") (name "unconnected-(U505-NC1-Pad2)") (class "Default")
      (node (ref "U505") (pin "2") (pinfunction "NC1_2") (pintype "bidirectional"))
    )
    (net (code "264") (name "unconnected-(U505-NC2-Pad3)") (class "Default")
      (node (ref "U505") (pin "3") (pinfunction "NC2_3") (pintype "bidirectional"))
    )
    (net (code "265") (name "unconnected-(U505-NC3-Pad4)") (class "Default")
      (node (ref "U505") (pin "4") (pinfunction "NC3_4") (pintype "bidirectional"))
    )
    (net (code "266") (name "unconnected-(U505-NC4-Pad5)") (class "Default")
      (node (ref "U505") (pin "5") (pinfunction "NC4_5") (pintype "bidirectional"))
    )
    (net (code "267") (name "unconnected-(U505-NC5-Pad14)") (class "Default")
      (node (ref "U505") (pin "14") (pinfunction "NC5_14") (pintype "bidirectional"))
    )
    (net (code "268") (name "unconnected-(U505-NC6-Pad15)") (class "Default")
      (node (ref "U505") (pin "15") (pinfunction "NC6_15") (pintype "bidirectional"))
    )
    (net (code "269") (name "unconnected-(U505-NC7-Pad16)") (class "Default")
      (node (ref "U505") (pin "16") (pinfunction "NC7_16") (pintype "bidirectional"))
    )
    (net (code "270") (name "unconnected-(U505-NC8-Pad17)") (class "Default")
      (node (ref "U505") (pin "17") (pinfunction "NC8_17") (pintype "bidirectional"))
    )
    (net (code "271") (name "unconnected-(U505-RESV1-Pad19)") (class "Default")
      (node (ref "U505") (pin "19") (pinfunction "RESV1_19") (pintype "bidirectional"))
    )
    (net (code "272") (name "unconnected-(U505-RESV2-Pad21)") (class "Default")
      (node (ref "U505") (pin "21") (pinfunction "RESV2_21") (pintype "bidirectional"))
    )
    (net (code "273") (name "unconnected-(U506-CSB1-Pad4)") (class "Default")
      (node (ref "U506") (pin "4") (pinfunction "CSB1_4") (pintype "bidirectional"))
    )
    (net (code "274") (name "unconnected-(U801B-PA11-Pad32)") (class "Default")
      (node (ref "U801") (pin "32") (pinfunction "PA11_32") (pintype "bidirectional"))
    )
    (net (code "275") (name "unconnected-(U801D-PB12-Pad25)") (class "Default")
      (node (ref "U801") (pin "25") (pinfunction "PB12_25") (pintype "bidirectional"))
    )
    (net (code "276") (name "unconnected-(U801E-PB6-Pad42)") (class "Default")
      (node (ref "U801") (pin "42") (pinfunction "PB6_42") (pintype "bidirectional"))
    )
    (net (code "277") (name "unconnected-(U801E-PB7-Pad43)") (class "Default")
      (node (ref "U801") (pin "43") (pinfunction "PB7_43") (pintype "bidirectional"))
    )
    (net (code "278") (name "unconnected-(U801F-PC14-Pad3)") (class "Default")
      (node (ref "U801") (pin "3") (pinfunction "PC14_3") (pintype "bidirectional"))
    )
    (net (code "279") (name "unconnected-(U801F-PC15-Pad4)") (class "Default")
      (node (ref "U801") (pin "4") (pinfunction "PC15_4") (pintype "bidirectional"))
    )
    (net (code "280") (name "unconnected-(U901-A7-Pad8)") (class "Default")
      (node (ref "U901") (pin "8") (pinfunction "A7_8") (pintype "bidirectional"))
    )
    (net (code "281") (name "unconnected-(U901-A8-Pad9)") (class "Default")
      (node (ref "U901") (pin "9") (pinfunction "A8_9") (pintype "bidirectional"))
    )
    (net (code "282") (name "unconnected-(U901-B7-Pad13)") (class "Default")
      (node (ref "U901") (pin "13") (pinfunction "B7_13") (pintype "bidirectional"))
    )
    (net (code "283") (name "unconnected-(U901-B8-Pad12)") (class "Default")
      (node (ref "U901") (pin "12") (pinfunction "B8_12") (pintype "bidirectional"))
    )
    (net (code "284") (name "unconnected-(U1101-CAS-PadP$11)") (class "Default")
      (node (ref "U1101") (pin "P$11") (pinfunction "CAS_P$11") (pintype "bidirectional"))
    )
    (net (code "285") (name "unconnected-(U1101-EN-PadP$22)") (class "Default")
      (node (ref "U1101") (pin "P$22") (pinfunction "EN_P$22") (pintype "bidirectional"))
    )
    (net (code "286") (name "unconnected-(U1101-~{SHDN}-PadP$23)") (class "Default")
      (node (ref "U1101") (pin "P$23") (pinfunction "~{SHDN}_P$23") (pintype "bidirectional"))
    )
    (net (code "287") (name "~{ACCEL_MAG_CS}") (class "Default")
      (node (ref "U101") (pin "9") (pinfunction "PC15_9") (pintype "bidirectional"))
      (node (ref "U504") (pin "8") (pinfunction "CS_8") (pintype "bidirectional"))
      (node (ref "X503") (pin "6") (pinfunction "S_6") (pintype "passive"))
    )
    (net (code "288") (name "~{BARO_CS}") (class "Default")
      (node (ref "U101") (pin "88") (pinfunction "PD7_88") (pintype "bidirectional"))
      (node (ref "U506") (pin "5") (pinfunction "CSB2_5") (pintype "bidirectional"))
    )
    (net (code "289") (name "~{FMU-LED_AMBER}") (class "Default")
      (node (ref "R707") (pin "P$1") (pinfunction "1_P$1") (pintype "passive"))
      (node (ref "U101") (pin "43") (pinfunction "PE12_43") (pintype "bidirectional"))
    )
    (net (code "290") (name "~{FRAM_CS}") (class "Default")
      (node (ref "U101") (pin "57") (pinfunction "PD10_57") (pintype "bidirectional"))
      (node (ref "U102") (pin "1") (pinfunction "~{S}_1") (pintype "bidirectional"))
    )
    (net (code "291") (name "~{GYRO_CS}") (class "Default")
      (node (ref "U101") (pin "7") (pinfunction "PC13_7") (pintype "bidirectional"))
      (node (ref "U501") (pin "5") (pinfunction "CS_5") (pintype "input"))
      (node (ref "U502") (pin "5") (pinfunction "CS_5") (pintype "bidirectional"))
      (node (ref "X503") (pin "7") (pinfunction "S_7") (pintype "passive"))
    )
    (net (code "292") (name "~{IO-LED_AMBER}") (class "Default")
      (node (ref "R709") (pin "P$1") (pinfunction "1_P$1") (pintype "passive"))
      (node (ref "U801") (pin "28") (pinfunction "PB15_28") (pintype "bidirectional"))
    )
    (net (code "293") (name "~{IO-LED_BLUE}") (class "Default")
      (node (ref "R712") (pin "P$1") (pinfunction "1_P$1") (pintype "passive"))
      (node (ref "U801") (pin "27") (pinfunction "PB14_27") (pintype "bidirectional"))
    )
    (net (code "294") (name "~{IO-LED_SAFETY}") (class "Default")
      (node (ref "R710") (pin "P$2") (pinfunction "2_P$2") (pintype "passive"))
      (node (ref "U801") (pin "26") (pinfunction "PB13_26") (pintype "bidirectional"))
    )
    (net (code "295") (name "~{MPU_CS}") (class "Default")
      (node (ref "U101") (pin "17") (pinfunction "PC2_17") (pintype "bidirectional"))
      (node (ref "U505") (pin "8") (pinfunction "/CS_8") (pintype "bidirectional"))
    )
    (net (code "296") (name "~{SBUS_OUTPUT_EN}") (class "Default")
      (node (ref "U801") (pin "40") (pinfunction "PB4_40") (pintype "bidirectional"))
      (node (ref "U903") (pin "7") (pinfunction "~{2OE}_7") (pintype "input"))
    )
    (net (code "297") (name "~{SPI_EXT_NSS}") (class "Default")
      (node (ref "J403") (pin "5") (pinfunction "5_5") (pintype "passive"))
      (node (ref "U101") (pin "3") (pinfunction "PE4_3") (pintype "bidirectional"))
    )
    (net (code "298") (name "~{VBUS_VALID}") (class "Default")
      (node (ref "!VBUS_VALID") (pin "P$1") (pinfunction "P$1_P$1") (pintype "passive"))
      (node (ref "RN1101") (pin "2") (pinfunction "1_2") (pintype "passive"))
      (node (ref "U101") (pin "15") (pinfunction "PC0_15") (pintype "bidirectional"))
      (node (ref "U1101") (pin "P$9") (pinfunction "~{VALID3}_P$9") (pintype "bidirectional"))
    )
    (net (code "299") (name "~{VDD_5V_HIPOWER_OC}") (class "Default")
      (node (ref "R602") (pin "P$1") (pinfunction "1_P$1") (pintype "passive"))
      (node (ref "U101") (pin "41") (pinfunction "PE10_41") (pintype "bidirectional"))
      (node (ref "U601") (pin "4") (pinfunction "~{FAULT}_4") (pintype "bidirectional"))
    )
    (net (code "300") (name "~{VDD_5V_PERIPH_EN}") (class "Default")
      (node (ref "R615") (pin "P$1") (pinfunction "1_P$1") (pintype "passive"))
      (node (ref "U101") (pin "67") (pinfunction "PA8_67") (pintype "bidirectional"))
      (node (ref "U601") (pin "5") (pinfunction "~{CE}_5") (pintype "bidirectional"))
      (node (ref "U602") (pin "5") (pinfunction "~{CE}_5") (pintype "bidirectional"))
    )
    (net (code "301") (name "~{VDD_5V_PERIPH_OC}") (class "Default")
      (node (ref "R604") (pin "P$1") (pinfunction "1_P$1") (pintype "passive"))
      (node (ref "U101") (pin "46") (pinfunction "PE15_46") (pintype "bidirectional"))
      (node (ref "U602") (pin "4") (pinfunction "~{FAULT}_4") (pintype "bidirectional"))
    )
    (net (code "302") (name "~{VDD_BRICK_VALID}") (class "Default")
      (node (ref "!VDD_BRICK_VALID") (pin "P$1") (pinfunction "P$1_P$1") (pintype "passive"))
      (node (ref "RN1101") (pin "4") (pinfunction "1_4") (pintype "passive"))
      (node (ref "U101") (pin "91") (pinfunction "PB5_91") (pintype "bidirectional"))
      (node (ref "U1101") (pin "P$7") (pinfunction "~{VALID1}_P$7") (pintype "bidirectional"))
    )
    (net (code "303") (name "~{VDD_SERVO_VALID}") (class "Default")
      (node (ref "!VDD_SERVO_VALID") (pin "P$1") (pinfunction "P$1_P$1") (pintype "passive"))
      (node (ref "RN1101") (pin "3") (pinfunction "1_3") (pintype "passive"))
      (node (ref "U101") (pin "93") (pinfunction "PB7_93") (pintype "bidirectional"))
      (node (ref "U1101") (pin "P$8") (pinfunction "~{VALID2}_P$8") (pintype "bidirectional"))
    )
  )
)
